# FeatherLargePrototype.net
KiCad netlist of a schematic drawn in EAGLE
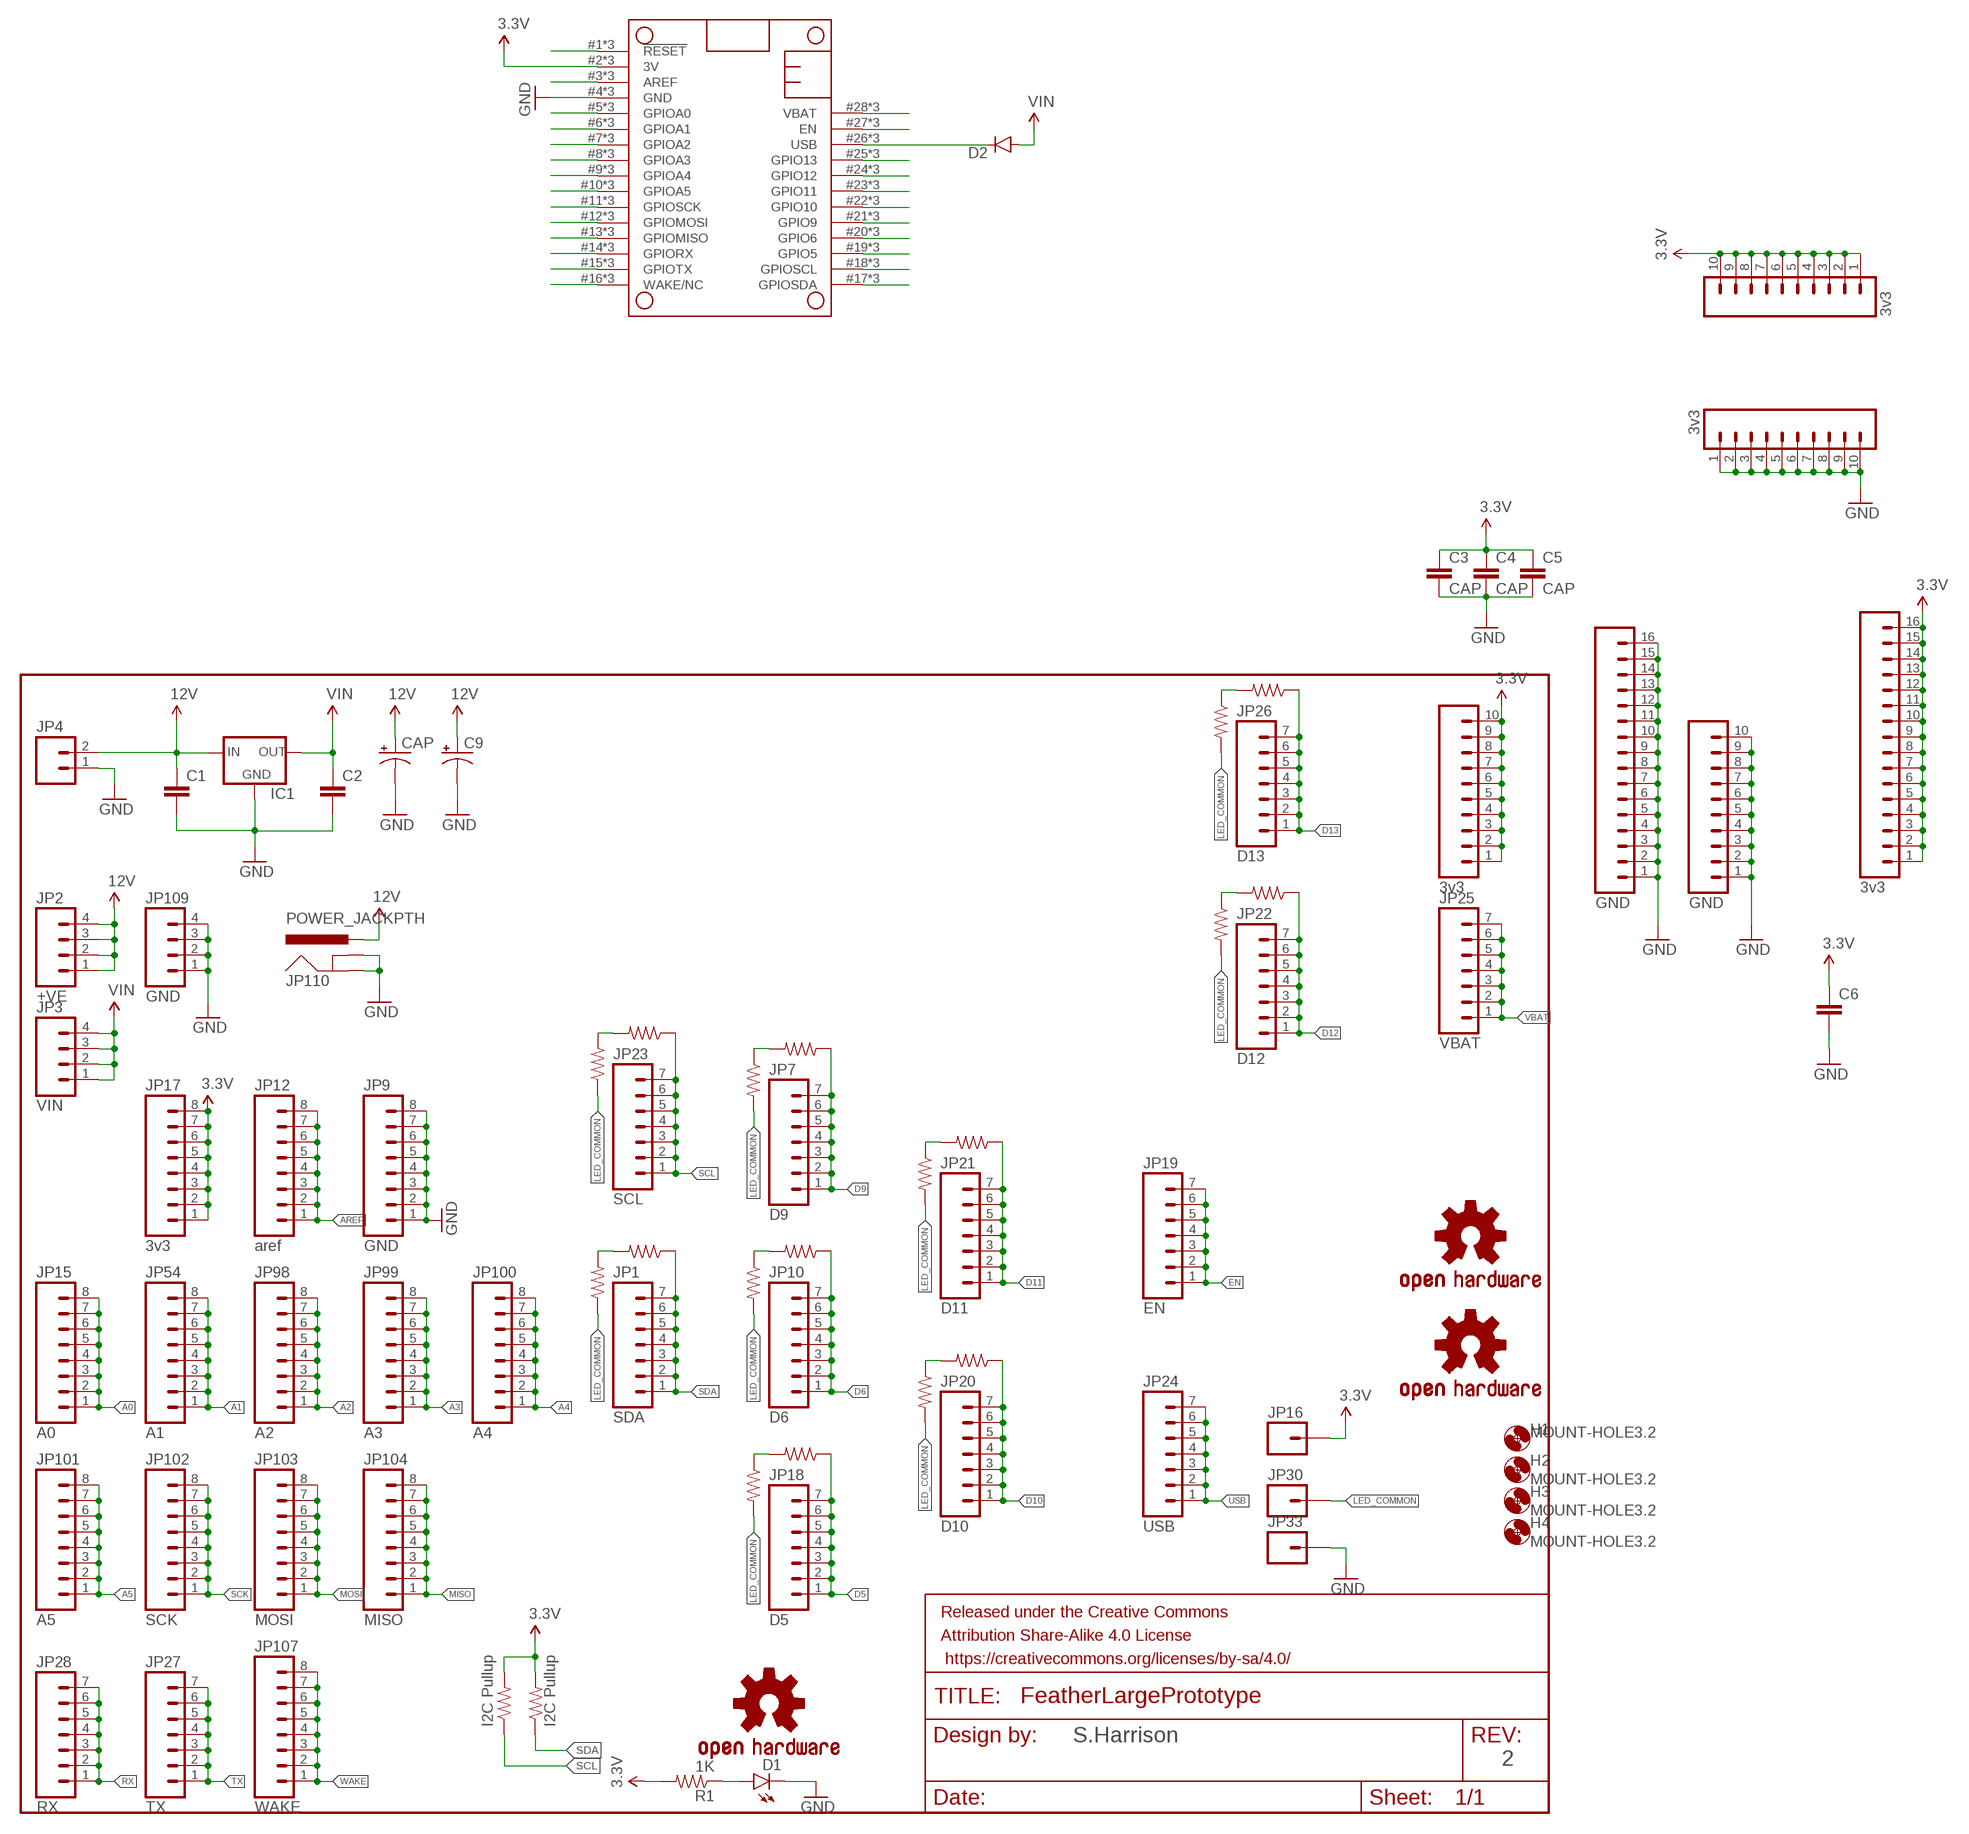
[diagram p0: schematic, sheet 1, part 1 of 2]
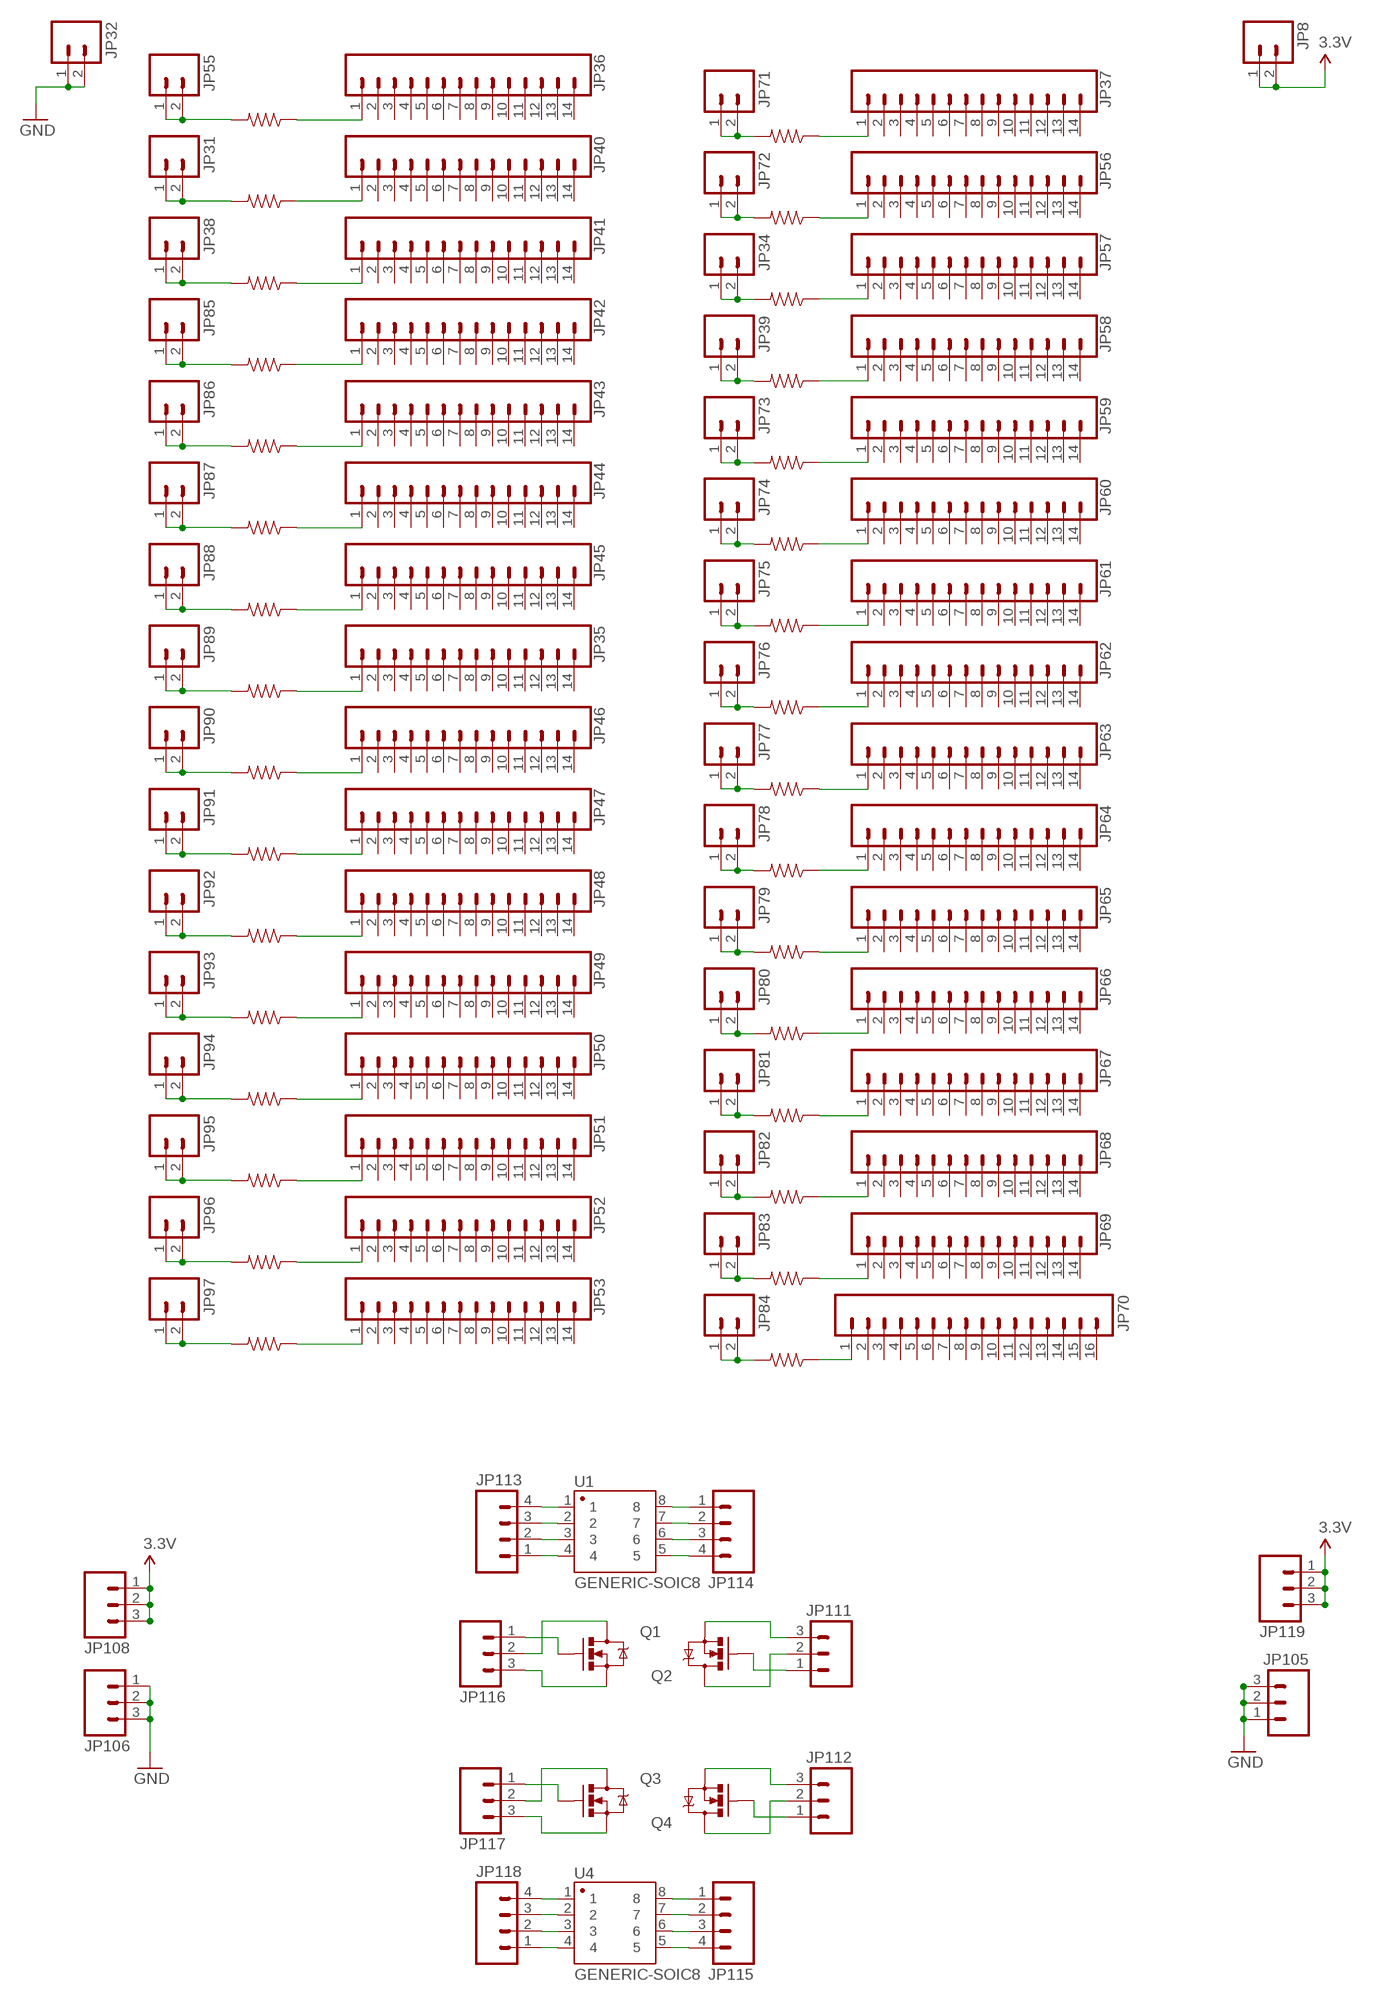
[diagram p1: schematic, sheet 1, part 2 of 2]

(export (version "E")
  (design (tool "Eeschema 10.0.6"))
  (components
    (comp (ref "C1")
      (value "CAP1206")
      (footprint "eagle-import:1206")
      (libsource (lib "eagle-import") (part "CAP1206"))
    )
    (comp (ref "C2")
      (value "CAP1206")
      (footprint "eagle-import:1206")
      (libsource (lib "eagle-import") (part "CAP1206"))
    )
    (comp (ref "C3")
      (value "CAP")
      (footprint "eagle-import:1206")
      (libsource (lib "eagle-import") (part "CAP1206"))
    )
    (comp (ref "C4")
      (value "CAP")
      (footprint "eagle-import:1206")
      (libsource (lib "eagle-import") (part "CAP1206"))
    )
    (comp (ref "C5")
      (value "CAP")
      (footprint "eagle-import:1206")
      (libsource (lib "eagle-import") (part "CAP1206"))
    )
    (comp (ref "C6")
      (value "CAP1206")
      (footprint "eagle-import:1206")
      (libsource (lib "eagle-import") (part "CAP1206"))
    )
    (comp (ref "C9")
      (value "CAP_POL7343")
      (footprint "eagle-import:EIA7343")
      (libsource (lib "eagle-import") (part "CAP_POL7343"))
    )
    (comp (ref "CAP")
      (value "CAP_POLPTH1")
      (footprint "eagle-import:CPOL-RADIAL-100UF-25V")
      (libsource (lib "eagle-import") (part "CAP_POLPTH1"))
    )
    (comp (ref "D1")
      (value "LED1206-BOTTOM")
      (footprint "eagle-import:LED-1206-BOTTOM")
      (libsource (lib "eagle-import") (part "LED1206-BOTTOM"))
    )
    (comp (ref "D2")
      (value "DIODESMA-ALT")
      (footprint "eagle-import:SMA-DIODE_ALT")
      (libsource (lib "eagle-import") (part "DIODESMA-ALT"))
    )
    (comp (ref "FRAME1")
      (value "FRAME-LETTER")
      (footprint "eagle-import:CREATIVE_COMMONS")
      (libsource (lib "eagle-import") (part "FRAME-LETTER"))
    )
    (comp (ref "H1")
      (value "MOUNT-HOLE3.2")
      (footprint "eagle-import:3,2")
      (libsource (lib "eagle-import") (part "MOUNT-HOLE3.2"))
    )
    (comp (ref "H2")
      (value "MOUNT-HOLE3.2")
      (footprint "eagle-import:3,2")
      (libsource (lib "eagle-import") (part "MOUNT-HOLE3.2"))
    )
    (comp (ref "H3")
      (value "MOUNT-HOLE3.2")
      (footprint "eagle-import:3,2")
      (libsource (lib "eagle-import") (part "MOUNT-HOLE3.2"))
    )
    (comp (ref "H4")
      (value "MOUNT-HOLE3.2")
      (footprint "eagle-import:3,2")
      (libsource (lib "eagle-import") (part "MOUNT-HOLE3.2"))
    )
    (comp (ref "IC1")
      (value "78XXS")
      (footprint "eagle-import:78XXS")
      (libsource (lib "eagle-import") (part "78XXS"))
    )
    (comp (ref "JP1")
      (value "SDA")
      (footprint "eagle-import:1X07")
      (libsource (lib "eagle-import") (part "M07"))
    )
    (comp (ref "JP2")
      (value "+VE")
      (footprint "eagle-import:1X04")
      (libsource (lib "eagle-import") (part "M04PTH"))
    )
    (comp (ref "JP3")
      (value "VIN")
      (footprint "eagle-import:1X04")
      (libsource (lib "eagle-import") (part "M04PTH"))
    )
    (comp (ref "JP4")
      (value "M025MM")
      (footprint "eagle-import:SCREWTERMINAL-5MM-2")
      (libsource (lib "eagle-import") (part "M025MM"))
    )
    (comp (ref "JP5")
      (value "3v3")
      (footprint "eagle-import:1X10")
      (libsource (lib "eagle-import") (part "M10SILK_FEMALE_PTH"))
    )
    (comp (ref "JP6")
      (value "3v3")
      (footprint "eagle-import:1X10")
      (libsource (lib "eagle-import") (part "M10SILK_FEMALE_PTH"))
    )
    (comp (ref "JP7")
      (value "D9")
      (footprint "eagle-import:1X07")
      (libsource (lib "eagle-import") (part "M07"))
    )
    (comp (ref "JP8")
      (value "M02PTH")
      (footprint "eagle-import:1X02")
      (libsource (lib "eagle-import") (part "M02PTH"))
    )
    (comp (ref "JP9")
      (value "GND")
      (footprint "eagle-import:1X08_ROUND")
      (libsource (lib "eagle-import") (part "M08"))
    )
    (comp (ref "JP10")
      (value "D6")
      (footprint "eagle-import:1X07")
      (libsource (lib "eagle-import") (part "M07"))
    )
    (comp (ref "JP11")
      (value "GND")
      (footprint "eagle-import:1X10")
      (libsource (lib "eagle-import") (part "M10SILK_FEMALE_PTH"))
    )
    (comp (ref "JP12")
      (value "aref")
      (footprint "eagle-import:1X08_ROUND")
      (libsource (lib "eagle-import") (part "M08"))
    )
    (comp (ref "JP13")
      (value "3v3")
      (footprint "eagle-import:1X16")
      (libsource (lib "eagle-import") (part "M16PTH"))
    )
    (comp (ref "JP14")
      (value "GND")
      (footprint "eagle-import:1X16")
      (libsource (lib "eagle-import") (part "M16PTH"))
    )
    (comp (ref "JP15")
      (value "A0")
      (footprint "eagle-import:1X08_ROUND")
      (libsource (lib "eagle-import") (part "M08"))
    )
    (comp (ref "JP16")
      (value "M01PTH")
      (footprint "eagle-import:1X01")
      (libsource (lib "eagle-import") (part "M01PTH"))
    )
    (comp (ref "JP17")
      (value "3v3")
      (footprint "eagle-import:1X08_ROUND")
      (libsource (lib "eagle-import") (part "M08"))
    )
    (comp (ref "JP18")
      (value "D5")
      (footprint "eagle-import:1X07")
      (libsource (lib "eagle-import") (part "M07"))
    )
    (comp (ref "JP19")
      (value "EN")
      (footprint "eagle-import:1X07")
      (libsource (lib "eagle-import") (part "M07"))
    )
    (comp (ref "JP20")
      (value "D10")
      (footprint "eagle-import:1X07")
      (libsource (lib "eagle-import") (part "M07"))
    )
    (comp (ref "JP21")
      (value "D11")
      (footprint "eagle-import:1X07")
      (libsource (lib "eagle-import") (part "M07"))
    )
    (comp (ref "JP22")
      (value "D12")
      (footprint "eagle-import:1X07")
      (libsource (lib "eagle-import") (part "M07"))
    )
    (comp (ref "JP23")
      (value "SCL")
      (footprint "eagle-import:1X07")
      (libsource (lib "eagle-import") (part "M07"))
    )
    (comp (ref "JP24")
      (value "USB")
      (footprint "eagle-import:1X07")
      (libsource (lib "eagle-import") (part "M07"))
    )
    (comp (ref "JP25")
      (value "VBAT")
      (footprint "eagle-import:1X07")
      (libsource (lib "eagle-import") (part "M07"))
    )
    (comp (ref "JP26")
      (value "D13")
      (footprint "eagle-import:1X07")
      (libsource (lib "eagle-import") (part "M07"))
    )
    (comp (ref "JP27")
      (value "TX")
      (footprint "eagle-import:1X07")
      (libsource (lib "eagle-import") (part "M07"))
    )
    (comp (ref "JP28")
      (value "RX")
      (footprint "eagle-import:1X07")
      (libsource (lib "eagle-import") (part "M07"))
    )
    (comp (ref "JP29")
      (value "3v3")
      (footprint "eagle-import:1X10")
      (libsource (lib "eagle-import") (part "M10SILK_FEMALE_PTH"))
    )
    (comp (ref "JP30")
      (value "M01PTH")
      (footprint "eagle-import:1X01")
      (libsource (lib "eagle-import") (part "M01PTH"))
    )
    (comp (ref "JP31")
      (value "M02PTH")
      (footprint "eagle-import:1X02")
      (libsource (lib "eagle-import") (part "M02PTH"))
    )
    (comp (ref "JP32")
      (value "M02PTH")
      (footprint "eagle-import:1X02")
      (libsource (lib "eagle-import") (part "M02PTH"))
    )
    (comp (ref "JP33")
      (value "M01PTH")
      (footprint "eagle-import:1X01")
      (libsource (lib "eagle-import") (part "M01PTH"))
    )
    (comp (ref "JP34")
      (value "M02PTH")
      (footprint "eagle-import:1X02")
      (libsource (lib "eagle-import") (part "M02PTH"))
    )
    (comp (ref "JP35")
      (value "CONN_14CONNECTED")
      (footprint "eagle-import:1X14_CONNECTED")
      (libsource (lib "eagle-import") (part "CONN_14CONNECTED"))
    )
    (comp (ref "JP36")
      (value "CONN_14CONNECTED")
      (footprint "eagle-import:1X14_CONNECTED")
      (libsource (lib "eagle-import") (part "CONN_14CONNECTED"))
    )
    (comp (ref "JP37")
      (value "CONN_14CONNECTED")
      (footprint "eagle-import:1X14_CONNECTED")
      (libsource (lib "eagle-import") (part "CONN_14CONNECTED"))
    )
    (comp (ref "JP38")
      (value "M02PTH")
      (footprint "eagle-import:1X02")
      (libsource (lib "eagle-import") (part "M02PTH"))
    )
    (comp (ref "JP39")
      (value "M02PTH")
      (footprint "eagle-import:1X02")
      (libsource (lib "eagle-import") (part "M02PTH"))
    )
    (comp (ref "JP40")
      (value "CONN_14CONNECTED")
      (footprint "eagle-import:1X14_CONNECTED")
      (libsource (lib "eagle-import") (part "CONN_14CONNECTED"))
    )
    (comp (ref "JP41")
      (value "CONN_14CONNECTED")
      (footprint "eagle-import:1X14_CONNECTED")
      (libsource (lib "eagle-import") (part "CONN_14CONNECTED"))
    )
    (comp (ref "JP42")
      (value "CONN_14CONNECTED")
      (footprint "eagle-import:1X14_CONNECTED")
      (libsource (lib "eagle-import") (part "CONN_14CONNECTED"))
    )
    (comp (ref "JP43")
      (value "CONN_14CONNECTED")
      (footprint "eagle-import:1X14_CONNECTED")
      (libsource (lib "eagle-import") (part "CONN_14CONNECTED"))
    )
    (comp (ref "JP44")
      (value "CONN_14CONNECTED")
      (footprint "eagle-import:1X14_CONNECTED")
      (libsource (lib "eagle-import") (part "CONN_14CONNECTED"))
    )
    (comp (ref "JP45")
      (value "CONN_14CONNECTED")
      (footprint "eagle-import:1X14_CONNECTED")
      (libsource (lib "eagle-import") (part "CONN_14CONNECTED"))
    )
    (comp (ref "JP46")
      (value "CONN_14CONNECTED")
      (footprint "eagle-import:1X14_CONNECTED")
      (libsource (lib "eagle-import") (part "CONN_14CONNECTED"))
    )
    (comp (ref "JP47")
      (value "CONN_14CONNECTED")
      (footprint "eagle-import:1X14_CONNECTED")
      (libsource (lib "eagle-import") (part "CONN_14CONNECTED"))
    )
    (comp (ref "JP48")
      (value "CONN_14CONNECTED")
      (footprint "eagle-import:1X14_CONNECTED")
      (libsource (lib "eagle-import") (part "CONN_14CONNECTED"))
    )
    (comp (ref "JP49")
      (value "CONN_14CONNECTED")
      (footprint "eagle-import:1X14_CONNECTED")
      (libsource (lib "eagle-import") (part "CONN_14CONNECTED"))
    )
    (comp (ref "JP50")
      (value "CONN_14CONNECTED")
      (footprint "eagle-import:1X14_CONNECTED")
      (libsource (lib "eagle-import") (part "CONN_14CONNECTED"))
    )
    (comp (ref "JP51")
      (value "CONN_14CONNECTED")
      (footprint "eagle-import:1X14_CONNECTED")
      (libsource (lib "eagle-import") (part "CONN_14CONNECTED"))
    )
    (comp (ref "JP52")
      (value "CONN_14CONNECTED")
      (footprint "eagle-import:1X14_CONNECTED")
      (libsource (lib "eagle-import") (part "CONN_14CONNECTED"))
    )
    (comp (ref "JP53")
      (value "CONN_14NO_SILK")
      (footprint "eagle-import:1X14_NO_SILK")
      (libsource (lib "eagle-import") (part "CONN_14NO_SILK"))
    )
    (comp (ref "JP54")
      (value "A1")
      (footprint "eagle-import:1X08_ROUND")
      (libsource (lib "eagle-import") (part "M08"))
    )
    (comp (ref "JP55")
      (value "M02PTH")
      (footprint "eagle-import:1X02")
      (libsource (lib "eagle-import") (part "M02PTH"))
    )
    (comp (ref "JP56")
      (value "CONN_14CONNECTED")
      (footprint "eagle-import:1X14_CONNECTED")
      (libsource (lib "eagle-import") (part "CONN_14CONNECTED"))
    )
    (comp (ref "JP57")
      (value "CONN_14CONNECTED")
      (footprint "eagle-import:1X14_CONNECTED")
      (libsource (lib "eagle-import") (part "CONN_14CONNECTED"))
    )
    (comp (ref "JP58")
      (value "CONN_14CONNECTED")
      (footprint "eagle-import:1X14_CONNECTED")
      (libsource (lib "eagle-import") (part "CONN_14CONNECTED"))
    )
    (comp (ref "JP59")
      (value "CONN_14CONNECTED")
      (footprint "eagle-import:1X14_CONNECTED")
      (libsource (lib "eagle-import") (part "CONN_14CONNECTED"))
    )
    (comp (ref "JP60")
      (value "CONN_14CONNECTED")
      (footprint "eagle-import:1X14_CONNECTED")
      (libsource (lib "eagle-import") (part "CONN_14CONNECTED"))
    )
    (comp (ref "JP61")
      (value "CONN_14CONNECTED")
      (footprint "eagle-import:1X14_CONNECTED")
      (libsource (lib "eagle-import") (part "CONN_14CONNECTED"))
    )
    (comp (ref "JP62")
      (value "CONN_14CONNECTED")
      (footprint "eagle-import:1X14_CONNECTED")
      (libsource (lib "eagle-import") (part "CONN_14CONNECTED"))
    )
    (comp (ref "JP63")
      (value "CONN_14CONNECTED")
      (footprint "eagle-import:1X14_CONNECTED")
      (libsource (lib "eagle-import") (part "CONN_14CONNECTED"))
    )
    (comp (ref "JP64")
      (value "CONN_14CONNECTED")
      (footprint "eagle-import:1X14_CONNECTED")
      (libsource (lib "eagle-import") (part "CONN_14CONNECTED"))
    )
    (comp (ref "JP65")
      (value "CONN_14CONNECTED")
      (footprint "eagle-import:1X14_CONNECTED")
      (libsource (lib "eagle-import") (part "CONN_14CONNECTED"))
    )
    (comp (ref "JP66")
      (value "CONN_14CONNECTED")
      (footprint "eagle-import:1X14_CONNECTED")
      (libsource (lib "eagle-import") (part "CONN_14CONNECTED"))
    )
    (comp (ref "JP67")
      (value "CONN_14CONNECTED")
      (footprint "eagle-import:1X14_CONNECTED")
      (libsource (lib "eagle-import") (part "CONN_14CONNECTED"))
    )
    (comp (ref "JP68")
      (value "CONN_14CONNECTED")
      (footprint "eagle-import:1X14_CONNECTED")
      (libsource (lib "eagle-import") (part "CONN_14CONNECTED"))
    )
    (comp (ref "JP69")
      (value "CONN_14CONNECTED")
      (footprint "eagle-import:1X14_CONNECTED")
      (libsource (lib "eagle-import") (part "CONN_14CONNECTED"))
    )
    (comp (ref "JP70")
      (value "M161X16_NO_SILK")
      (footprint "eagle-import:1X16_NO_SILK")
      (libsource (lib "eagle-import") (part "M161X16_NO_SILK"))
    )
    (comp (ref "JP71")
      (value "M02PTH")
      (footprint "eagle-import:1X02")
      (libsource (lib "eagle-import") (part "M02PTH"))
    )
    (comp (ref "JP72")
      (value "M02PTH")
      (footprint "eagle-import:1X02")
      (libsource (lib "eagle-import") (part "M02PTH"))
    )
    (comp (ref "JP73")
      (value "M02PTH")
      (footprint "eagle-import:1X02")
      (libsource (lib "eagle-import") (part "M02PTH"))
    )
    (comp (ref "JP74")
      (value "M02PTH")
      (footprint "eagle-import:1X02")
      (libsource (lib "eagle-import") (part "M02PTH"))
    )
    (comp (ref "JP75")
      (value "M02PTH")
      (footprint "eagle-import:1X02")
      (libsource (lib "eagle-import") (part "M02PTH"))
    )
    (comp (ref "JP76")
      (value "M02PTH")
      (footprint "eagle-import:1X02")
      (libsource (lib "eagle-import") (part "M02PTH"))
    )
    (comp (ref "JP77")
      (value "M02PTH")
      (footprint "eagle-import:1X02")
      (libsource (lib "eagle-import") (part "M02PTH"))
    )
    (comp (ref "JP78")
      (value "M02PTH")
      (footprint "eagle-import:1X02")
      (libsource (lib "eagle-import") (part "M02PTH"))
    )
    (comp (ref "JP79")
      (value "M02PTH")
      (footprint "eagle-import:1X02")
      (libsource (lib "eagle-import") (part "M02PTH"))
    )
    (comp (ref "JP80")
      (value "M02PTH")
      (footprint "eagle-import:1X02")
      (libsource (lib "eagle-import") (part "M02PTH"))
    )
    (comp (ref "JP81")
      (value "M02PTH")
      (footprint "eagle-import:1X02")
      (libsource (lib "eagle-import") (part "M02PTH"))
    )
    (comp (ref "JP82")
      (value "M02PTH")
      (footprint "eagle-import:1X02")
      (libsource (lib "eagle-import") (part "M02PTH"))
    )
    (comp (ref "JP83")
      (value "M02PTH")
      (footprint "eagle-import:1X02")
      (libsource (lib "eagle-import") (part "M02PTH"))
    )
    (comp (ref "JP84")
      (value "M02PTH")
      (footprint "eagle-import:1X02")
      (libsource (lib "eagle-import") (part "M02PTH"))
    )
    (comp (ref "JP85")
      (value "M02PTH")
      (footprint "eagle-import:1X02")
      (libsource (lib "eagle-import") (part "M02PTH"))
    )
    (comp (ref "JP86")
      (value "M02PTH")
      (footprint "eagle-import:1X02")
      (libsource (lib "eagle-import") (part "M02PTH"))
    )
    (comp (ref "JP87")
      (value "M02PTH")
      (footprint "eagle-import:1X02")
      (libsource (lib "eagle-import") (part "M02PTH"))
    )
    (comp (ref "JP88")
      (value "M02PTH")
      (footprint "eagle-import:1X02")
      (libsource (lib "eagle-import") (part "M02PTH"))
    )
    (comp (ref "JP89")
      (value "M02PTH")
      (footprint "eagle-import:1X02")
      (libsource (lib "eagle-import") (part "M02PTH"))
    )
    (comp (ref "JP90")
      (value "M02PTH")
      (footprint "eagle-import:1X02")
      (libsource (lib "eagle-import") (part "M02PTH"))
    )
    (comp (ref "JP91")
      (value "M02PTH")
      (footprint "eagle-import:1X02")
      (libsource (lib "eagle-import") (part "M02PTH"))
    )
    (comp (ref "JP92")
      (value "M02PTH")
      (footprint "eagle-import:1X02")
      (libsource (lib "eagle-import") (part "M02PTH"))
    )
    (comp (ref "JP93")
      (value "M02PTH")
      (footprint "eagle-import:1X02")
      (libsource (lib "eagle-import") (part "M02PTH"))
    )
    (comp (ref "JP94")
      (value "M02PTH")
      (footprint "eagle-import:1X02")
      (libsource (lib "eagle-import") (part "M02PTH"))
    )
    (comp (ref "JP95")
      (value "M02PTH")
      (footprint "eagle-import:1X02")
      (libsource (lib "eagle-import") (part "M02PTH"))
    )
    (comp (ref "JP96")
      (value "M02PTH")
      (footprint "eagle-import:1X02")
      (libsource (lib "eagle-import") (part "M02PTH"))
    )
    (comp (ref "JP97")
      (value "M02PTH")
      (footprint "eagle-import:1X02")
      (libsource (lib "eagle-import") (part "M02PTH"))
    )
    (comp (ref "JP98")
      (value "A2")
      (footprint "eagle-import:1X08_ROUND")
      (libsource (lib "eagle-import") (part "M08"))
    )
    (comp (ref "JP99")
      (value "A3")
      (footprint "eagle-import:1X08_ROUND")
      (libsource (lib "eagle-import") (part "M08"))
    )
    (comp (ref "JP100")
      (value "A4")
      (footprint "eagle-import:1X08_ROUND")
      (libsource (lib "eagle-import") (part "M08"))
    )
    (comp (ref "JP101")
      (value "A5")
      (footprint "eagle-import:1X08_ROUND")
      (libsource (lib "eagle-import") (part "M08"))
    )
    (comp (ref "JP102")
      (value "SCK")
      (footprint "eagle-import:1X08_ROUND")
      (libsource (lib "eagle-import") (part "M08"))
    )
    (comp (ref "JP103")
      (value "MOSI")
      (footprint "eagle-import:1X08_ROUND")
      (libsource (lib "eagle-import") (part "M08"))
    )
    (comp (ref "JP104")
      (value "MISO")
      (footprint "eagle-import:1X08_ROUND")
      (libsource (lib "eagle-import") (part "M08"))
    )
    (comp (ref "JP105")
      (value "M03PTH")
      (footprint "eagle-import:1X03")
      (libsource (lib "eagle-import") (part "M03PTH"))
    )
    (comp (ref "JP106")
      (value "M03PTH")
      (footprint "eagle-import:1X03")
      (libsource (lib "eagle-import") (part "M03PTH"))
    )
    (comp (ref "JP107")
      (value "WAKE")
      (footprint "eagle-import:1X08_ROUND")
      (libsource (lib "eagle-import") (part "M08"))
    )
    (comp (ref "JP108")
      (value "M03PTH")
      (footprint "eagle-import:1X03")
      (libsource (lib "eagle-import") (part "M03PTH"))
    )
    (comp (ref "JP109")
      (value "GND")
      (footprint "eagle-import:1X04")
      (libsource (lib "eagle-import") (part "M04PTH"))
    )
    (comp (ref "JP110")
      (value "POWER_JACKPTH")
      (footprint "eagle-import:POWER_JACK_PTH")
      (libsource (lib "eagle-import") (part "POWER_JACKPTH"))
    )
    (comp (ref "JP111")
      (value "M03PTH")
      (footprint "eagle-import:1X03")
      (libsource (lib "eagle-import") (part "M03PTH"))
    )
    (comp (ref "JP112")
      (value "M03PTH")
      (footprint "eagle-import:1X03")
      (libsource (lib "eagle-import") (part "M03PTH"))
    )
    (comp (ref "JP113")
      (value "M04NO_SILK_ALL_ROUND")
      (footprint "eagle-import:1X04_NO_SILK_ALL_ROUND")
      (libsource (lib "eagle-import") (part "M04NO_SILK_ALL_ROUND"))
    )
    (comp (ref "JP114")
      (value "M04NO_SILK_ALL_ROUND")
      (footprint "eagle-import:1X04_NO_SILK_ALL_ROUND")
      (libsource (lib "eagle-import") (part "M04NO_SILK_ALL_ROUND"))
    )
    (comp (ref "JP115")
      (value "M04NO_SILK_ALL_ROUND")
      (footprint "eagle-import:1X04_NO_SILK_ALL_ROUND")
      (libsource (lib "eagle-import") (part "M04NO_SILK_ALL_ROUND"))
    )
    (comp (ref "JP116")
      (value "M03PTH")
      (footprint "eagle-import:1X03")
      (libsource (lib "eagle-import") (part "M03PTH"))
    )
    (comp (ref "JP117")
      (value "M03PTH")
      (footprint "eagle-import:1X03")
      (libsource (lib "eagle-import") (part "M03PTH"))
    )
    (comp (ref "JP118")
      (value "M04NO_SILK_ALL_ROUND")
      (footprint "eagle-import:1X04_NO_SILK_ALL_ROUND")
      (libsource (lib "eagle-import") (part "M04NO_SILK_ALL_ROUND"))
    )
    (comp (ref "JP119")
      (value "M03PTH")
      (footprint "eagle-import:1X03")
      (libsource (lib "eagle-import") (part "M03PTH"))
    )
    (comp (ref "LOGO1")
      (value "OSHW-LOGOL")
      (footprint "eagle-import:OSHW-LOGO-L")
      (libsource (lib "eagle-import") (part "OSHW-LOGOL"))
    )
    (comp (ref "LOGO2")
      (value "OSHW-LOGOL")
      (footprint "eagle-import:OSHW-LOGO-L")
      (libsource (lib "eagle-import") (part "OSHW-LOGOL"))
    )
    (comp (ref "LOGO3")
      (value "OSHW-LOGOM")
      (footprint "eagle-import:OSHW-LOGO-M")
      (libsource (lib "eagle-import") (part "OSHW-LOGOM"))
    )
    (comp (ref "MS2")
      (value "FEATHERWINGFEATHEWING_BREAKOUT")
      (footprint "eagle-import:FEATHERWING_BREAKOUT")
      (libsource (lib "eagle-import") (part "FEATHERWINGFEATHEWING_BREAKOUT"))
    )
    (comp (ref "Q1")
      (value "MOSFET-NCHANNELBSS123LT1G")
      (footprint "eagle-import:SOT23-3")
      (libsource (lib "eagle-import") (part "MOSFET-NCHANNELBSS123LT1G"))
    )
    (comp (ref "Q2")
      (value "MOSFET-NCHANNELBSS123LT1G")
      (footprint "eagle-import:SOT23-3")
      (libsource (lib "eagle-import") (part "MOSFET-NCHANNELBSS123LT1G"))
    )
    (comp (ref "Q3")
      (value "MOSFET-NCHANNELBSS123LT1G")
      (footprint "eagle-import:SOT23-3")
      (libsource (lib "eagle-import") (part "MOSFET-NCHANNELBSS123LT1G"))
    )
    (comp (ref "Q4")
      (value "MOSFET-NCHANNELBSS123LT1G")
      (footprint "eagle-import:SOT23-3")
      (libsource (lib "eagle-import") (part "MOSFET-NCHANNELBSS123LT1G"))
    )
    (comp (ref "R1")
      (value "1K")
      (footprint "eagle-import:1206")
      (libsource (lib "eagle-import") (part "RESISTOR1206"))
    )
    (comp (ref "R10")
      (value "RESISTOR1206")
      (footprint "eagle-import:1206")
      (libsource (lib "eagle-import") (part "RESISTOR1206"))
    )
    (comp (ref "R11")
      (value "RESISTOR1206")
      (footprint "eagle-import:1206")
      (libsource (lib "eagle-import") (part "RESISTOR1206"))
    )
    (comp (ref "R12")
      (value "RESISTOR1206")
      (footprint "eagle-import:1206")
      (libsource (lib "eagle-import") (part "RESISTOR1206"))
    )
    (comp (ref "R13")
      (value "RESISTOR1206")
      (footprint "eagle-import:1206")
      (libsource (lib "eagle-import") (part "RESISTOR1206"))
    )
    (comp (ref "R14")
      (value "RESISTOR1206")
      (footprint "eagle-import:1206")
      (libsource (lib "eagle-import") (part "RESISTOR1206"))
    )
    (comp (ref "R15")
      (value "RESISTOR1206")
      (footprint "eagle-import:1206")
      (libsource (lib "eagle-import") (part "RESISTOR1206"))
    )
    (comp (ref "R16")
      (value "RESISTOR1206")
      (footprint "eagle-import:1206")
      (libsource (lib "eagle-import") (part "RESISTOR1206"))
    )
    (comp (ref "R17")
      (value "RESISTOR1206")
      (footprint "eagle-import:1206")
      (libsource (lib "eagle-import") (part "RESISTOR1206"))
    )
    (comp (ref "R18")
      (value "RESISTOR1206")
      (footprint "eagle-import:1206")
      (libsource (lib "eagle-import") (part "RESISTOR1206"))
    )
    (comp (ref "R19")
      (value "RESISTOR1206")
      (footprint "eagle-import:1206")
      (libsource (lib "eagle-import") (part "RESISTOR1206"))
    )
    (comp (ref "R20")
      (value "RESISTOR1206")
      (footprint "eagle-import:1206")
      (libsource (lib "eagle-import") (part "RESISTOR1206"))
    )
    (comp (ref "R21")
      (value "RESISTOR1206")
      (footprint "eagle-import:1206")
      (libsource (lib "eagle-import") (part "RESISTOR1206"))
    )
    (comp (ref "R22")
      (value "RESISTOR1206")
      (footprint "eagle-import:1206")
      (libsource (lib "eagle-import") (part "RESISTOR1206"))
    )
    (comp (ref "R23")
      (value "RESISTOR1206")
      (footprint "eagle-import:1206")
      (libsource (lib "eagle-import") (part "RESISTOR1206"))
    )
    (comp (ref "R24")
      (value "RESISTOR1206")
      (footprint "eagle-import:1206")
      (libsource (lib "eagle-import") (part "RESISTOR1206"))
    )
    (comp (ref "R25")
      (value "RESISTOR1206")
      (footprint "eagle-import:1206")
      (libsource (lib "eagle-import") (part "RESISTOR1206"))
    )
    (comp (ref "R26")
      (value "RESISTOR1206")
      (footprint "eagle-import:1206")
      (libsource (lib "eagle-import") (part "RESISTOR1206"))
    )
    (comp (ref "R27")
      (value "RESISTOR1206")
      (footprint "eagle-import:1206")
      (libsource (lib "eagle-import") (part "RESISTOR1206"))
    )
    (comp (ref "R30")
      (value "RESISTOR1206")
      (footprint "eagle-import:1206")
      (libsource (lib "eagle-import") (part "RESISTOR1206"))
    )
    (comp (ref "R31")
      (value "RESISTOR1206")
      (footprint "eagle-import:1206")
      (libsource (lib "eagle-import") (part "RESISTOR1206"))
    )
    (comp (ref "R32")
      (value "RESISTOR1206")
      (footprint "eagle-import:1206")
      (libsource (lib "eagle-import") (part "RESISTOR1206"))
    )
    (comp (ref "R33")
      (value "RESISTOR1206")
      (footprint "eagle-import:1206")
      (libsource (lib "eagle-import") (part "RESISTOR1206"))
    )
    (comp (ref "R34")
      (value "RESISTOR1206")
      (footprint "eagle-import:1206")
      (libsource (lib "eagle-import") (part "RESISTOR1206"))
    )
    (comp (ref "R35")
      (value "RESISTOR1206")
      (footprint "eagle-import:1206")
      (libsource (lib "eagle-import") (part "RESISTOR1206"))
    )
    (comp (ref "R36")
      (value "RESISTOR1206")
      (footprint "eagle-import:1206")
      (libsource (lib "eagle-import") (part "RESISTOR1206"))
    )
    (comp (ref "R37")
      (value "RESISTOR1206")
      (footprint "eagle-import:1206")
      (libsource (lib "eagle-import") (part "RESISTOR1206"))
    )
    (comp (ref "R38")
      (value "RESISTOR1206")
      (footprint "eagle-import:1206")
      (libsource (lib "eagle-import") (part "RESISTOR1206"))
    )
    (comp (ref "R39")
      (value "RESISTOR1206")
      (footprint "eagle-import:1206")
      (libsource (lib "eagle-import") (part "RESISTOR1206"))
    )
    (comp (ref "R40")
      (value "RESISTOR1206")
      (footprint "eagle-import:1206")
      (libsource (lib "eagle-import") (part "RESISTOR1206"))
    )
    (comp (ref "R41")
      (value "RESISTOR1206")
      (footprint "eagle-import:1206")
      (libsource (lib "eagle-import") (part "RESISTOR1206"))
    )
    (comp (ref "R42")
      (value "RESISTOR1206")
      (footprint "eagle-import:1206")
      (libsource (lib "eagle-import") (part "RESISTOR1206"))
    )
    (comp (ref "R43")
      (value "RESISTOR1206")
      (footprint "eagle-import:1206")
      (libsource (lib "eagle-import") (part "RESISTOR1206"))
    )
    (comp (ref "R44")
      (value "RESISTOR1206")
      (footprint "eagle-import:1206")
      (libsource (lib "eagle-import") (part "RESISTOR1206"))
    )
    (comp (ref "R45")
      (value "RESISTOR1206")
      (footprint "eagle-import:1206")
      (libsource (lib "eagle-import") (part "RESISTOR1206"))
    )
    (comp (ref "R46")
      (value "RESISTOR1206")
      (footprint "eagle-import:1206")
      (libsource (lib "eagle-import") (part "RESISTOR1206"))
    )
    (comp (ref "R47")
      (value "RESISTOR1206")
      (footprint "eagle-import:1206")
      (libsource (lib "eagle-import") (part "RESISTOR1206"))
    )
    (comp (ref "R48")
      (value "RESISTOR1206")
      (footprint "eagle-import:1206")
      (libsource (lib "eagle-import") (part "RESISTOR1206"))
    )
    (comp (ref "R49")
      (value "RESISTOR1206")
      (footprint "eagle-import:1206")
      (libsource (lib "eagle-import") (part "RESISTOR1206"))
    )
    (comp (ref "R50")
      (value "RESISTOR1206")
      (footprint "eagle-import:1206")
      (libsource (lib "eagle-import") (part "RESISTOR1206"))
    )
    (comp (ref "R51")
      (value "RESISTOR1206")
      (footprint "eagle-import:1206")
      (libsource (lib "eagle-import") (part "RESISTOR1206"))
    )
    (comp (ref "R52")
      (value "RESISTOR1206")
      (footprint "eagle-import:1206")
      (libsource (lib "eagle-import") (part "RESISTOR1206"))
    )
    (comp (ref "R53")
      (value "RESISTOR1206")
      (footprint "eagle-import:1206")
      (libsource (lib "eagle-import") (part "RESISTOR1206"))
    )
    (comp (ref "R54")
      (value "RESISTOR1206")
      (footprint "eagle-import:1206")
      (libsource (lib "eagle-import") (part "RESISTOR1206"))
    )
    (comp (ref "R55")
      (value "RESISTOR1206")
      (footprint "eagle-import:1206")
      (libsource (lib "eagle-import") (part "RESISTOR1206"))
    )
    (comp (ref "R56")
      (value "RESISTOR1206")
      (footprint "eagle-import:1206")
      (libsource (lib "eagle-import") (part "RESISTOR1206"))
    )
    (comp (ref "R57")
      (value "RESISTOR1206")
      (footprint "eagle-import:1206")
      (libsource (lib "eagle-import") (part "RESISTOR1206"))
    )
    (comp (ref "R58")
      (value "RESISTOR1206")
      (footprint "eagle-import:1206")
      (libsource (lib "eagle-import") (part "RESISTOR1206"))
    )
    (comp (ref "R59")
      (value "RESISTOR1206")
      (footprint "eagle-import:1206")
      (libsource (lib "eagle-import") (part "RESISTOR1206"))
    )
    (comp (ref "R60")
      (value "RESISTOR1206")
      (footprint "eagle-import:1206")
      (libsource (lib "eagle-import") (part "RESISTOR1206"))
    )
    (comp (ref "R61")
      (value "RESISTOR1206")
      (footprint "eagle-import:1206")
      (libsource (lib "eagle-import") (part "RESISTOR1206"))
    )
    (comp (ref "R62")
      (value "I2C Pullup")
      (footprint "eagle-import:1206")
      (libsource (lib "eagle-import") (part "RESISTOR1206"))
    )
    (comp (ref "R63")
      (value "I2C Pullup")
      (footprint "eagle-import:1206")
      (libsource (lib "eagle-import") (part "RESISTOR1206"))
    )
    (comp (ref "U1")
      (value "GENERIC-SOIC8")
      (footprint "eagle-import:SO08-UNIVERSAL")
      (libsource (lib "eagle-import") (part "GENERIC-SOIC8"))
    )
    (comp (ref "U4")
      (value "GENERIC-SOIC8")
      (footprint "eagle-import:SO08-UNIVERSAL")
      (libsource (lib "eagle-import") (part "GENERIC-SOIC8"))
    )
  )
  (nets
    (net (code "1") (name "3.3V") (class "Default")
      (node (ref "C3") (pin "1") (pinfunction "1_1") (pintype "passive"))
      (node (ref "C4") (pin "1") (pinfunction "1_1") (pintype "passive"))
      (node (ref "C5") (pin "1") (pinfunction "1_1") (pintype "passive"))
      (node (ref "C6") (pin "1") (pinfunction "1_1") (pintype "passive"))
      (node (ref "JP108") (pin "1") (pinfunction "1_1") (pintype "passive"))
      (node (ref "JP108") (pin "2") (pinfunction "2_2") (pintype "passive"))
      (node (ref "JP108") (pin "3") (pinfunction "3_3") (pintype "passive"))
      (node (ref "JP119") (pin "1") (pinfunction "1_1") (pintype "passive"))
      (node (ref "JP119") (pin "2") (pinfunction "2_2") (pintype "passive"))
      (node (ref "JP119") (pin "3") (pinfunction "3_3") (pintype "passive"))
      (node (ref "JP13") (pin "1") (pinfunction "1_1") (pintype "passive"))
      (node (ref "JP13") (pin "10") (pinfunction "10_10") (pintype "passive"))
      (node (ref "JP13") (pin "11") (pinfunction "11_11") (pintype "passive"))
      (node (ref "JP13") (pin "12") (pinfunction "12_12") (pintype "passive"))
      (node (ref "JP13") (pin "13") (pinfunction "13_13") (pintype "passive"))
      (node (ref "JP13") (pin "14") (pinfunction "14_14") (pintype "passive"))
      (node (ref "JP13") (pin "15") (pinfunction "15_15") (pintype "passive"))
      (node (ref "JP13") (pin "16") (pinfunction "16_16") (pintype "passive"))
      (node (ref "JP13") (pin "2") (pinfunction "2_2") (pintype "passive"))
      (node (ref "JP13") (pin "3") (pinfunction "3_3") (pintype "passive"))
      (node (ref "JP13") (pin "4") (pinfunction "4_4") (pintype "passive"))
      (node (ref "JP13") (pin "5") (pinfunction "5_5") (pintype "passive"))
      (node (ref "JP13") (pin "6") (pinfunction "6_6") (pintype "passive"))
      (node (ref "JP13") (pin "7") (pinfunction "7_7") (pintype "passive"))
      (node (ref "JP13") (pin "8") (pinfunction "8_8") (pintype "passive"))
      (node (ref "JP13") (pin "9") (pinfunction "9_9") (pintype "passive"))
      (node (ref "JP16") (pin "1") (pinfunction "1_1") (pintype "passive"))
      (node (ref "JP17") (pin "1") (pinfunction "1_1") (pintype "passive"))
      (node (ref "JP17") (pin "2") (pinfunction "2_2") (pintype "passive"))
      (node (ref "JP17") (pin "3") (pinfunction "3_3") (pintype "passive"))
      (node (ref "JP17") (pin "4") (pinfunction "4_4") (pintype "passive"))
      (node (ref "JP17") (pin "5") (pinfunction "5_5") (pintype "passive"))
      (node (ref "JP17") (pin "6") (pinfunction "6_6") (pintype "passive"))
      (node (ref "JP17") (pin "7") (pinfunction "7_7") (pintype "passive"))
      (node (ref "JP17") (pin "8") (pinfunction "8_8") (pintype "passive"))
      (node (ref "JP5") (pin "1") (pinfunction "1_1") (pintype "passive"))
      (node (ref "JP5") (pin "10") (pinfunction "10_10") (pintype "passive"))
      (node (ref "JP5") (pin "2") (pinfunction "2_2") (pintype "passive"))
      (node (ref "JP5") (pin "3") (pinfunction "3_3") (pintype "passive"))
      (node (ref "JP5") (pin "4") (pinfunction "4_4") (pintype "passive"))
      (node (ref "JP5") (pin "5") (pinfunction "5_5") (pintype "passive"))
      (node (ref "JP5") (pin "6") (pinfunction "6_6") (pintype "passive"))
      (node (ref "JP5") (pin "7") (pinfunction "7_7") (pintype "passive"))
      (node (ref "JP5") (pin "8") (pinfunction "8_8") (pintype "passive"))
      (node (ref "JP5") (pin "9") (pinfunction "9_9") (pintype "passive"))
      (node (ref "JP6") (pin "1") (pinfunction "1_1") (pintype "passive"))
      (node (ref "JP6") (pin "10") (pinfunction "10_10") (pintype "passive"))
      (node (ref "JP6") (pin "2") (pinfunction "2_2") (pintype "passive"))
      (node (ref "JP6") (pin "3") (pinfunction "3_3") (pintype "passive"))
      (node (ref "JP6") (pin "4") (pinfunction "4_4") (pintype "passive"))
      (node (ref "JP6") (pin "5") (pinfunction "5_5") (pintype "passive"))
      (node (ref "JP6") (pin "6") (pinfunction "6_6") (pintype "passive"))
      (node (ref "JP6") (pin "7") (pinfunction "7_7") (pintype "passive"))
      (node (ref "JP6") (pin "8") (pinfunction "8_8") (pintype "passive"))
      (node (ref "JP6") (pin "9") (pinfunction "9_9") (pintype "passive"))
      (node (ref "JP8") (pin "1") (pinfunction "1_1") (pintype "passive"))
      (node (ref "JP8") (pin "2") (pinfunction "2_2") (pintype "passive"))
      (node (ref "MS2") (pin "#2") (pinfunction "3V_#2") (pintype "power_in"))
      (node (ref "MS2") (pin "2") (pinfunction "3V_2") (pintype "power_in"))
      (node (ref "MS2") (pin "@2") (pinfunction "3V_@2") (pintype "power_in"))
      (node (ref "R1") (pin "2") (pinfunction "2_2") (pintype "passive"))
      (node (ref "R62") (pin "2") (pinfunction "2_2") (pintype "passive"))
      (node (ref "R63") (pin "2") (pinfunction "2_2") (pintype "passive"))
    )
    (net (code "2") (name "12V") (class "Default")
      (node (ref "C1") (pin "1") (pinfunction "1_1") (pintype "passive"))
      (node (ref "C9") (pin "A") (pinfunction "+_A") (pintype "passive"))
      (node (ref "CAP") (pin "1") (pinfunction "+_1") (pintype "passive"))
      (node (ref "IC1") (pin "IN") (pinfunction "IN_IN") (pintype "input"))
      (node (ref "JP110") (pin "PWR") (pinfunction "PWR_PWR") (pintype "bidirectional"))
      (node (ref "JP2") (pin "1") (pinfunction "1_1") (pintype "passive"))
      (node (ref "JP2") (pin "2") (pinfunction "2_2") (pintype "passive"))
      (node (ref "JP2") (pin "3") (pinfunction "3_3") (pintype "passive"))
      (node (ref "JP2") (pin "4") (pinfunction "4_4") (pintype "passive"))
      (node (ref "JP4") (pin "2") (pinfunction "2_2") (pintype "passive"))
    )
    (net (code "3") (name "A0") (class "Default")
      (node (ref "JP15") (pin "1") (pinfunction "1_1") (pintype "passive"))
      (node (ref "JP15") (pin "2") (pinfunction "2_2") (pintype "passive"))
      (node (ref "JP15") (pin "3") (pinfunction "3_3") (pintype "passive"))
      (node (ref "JP15") (pin "4") (pinfunction "4_4") (pintype "passive"))
      (node (ref "JP15") (pin "5") (pinfunction "5_5") (pintype "passive"))
      (node (ref "JP15") (pin "6") (pinfunction "6_6") (pintype "passive"))
      (node (ref "JP15") (pin "7") (pinfunction "7_7") (pintype "passive"))
      (node (ref "JP15") (pin "8") (pinfunction "8_8") (pintype "passive"))
      (node (ref "MS2") (pin "#5") (pinfunction "GPIOA0_#5") (pintype "bidirectional"))
      (node (ref "MS2") (pin "5") (pinfunction "GPIOA0_5") (pintype "bidirectional"))
      (node (ref "MS2") (pin "@5") (pinfunction "GPIOA0_@5") (pintype "bidirectional"))
    )
    (net (code "4") (name "A1") (class "Default")
      (node (ref "JP54") (pin "1") (pinfunction "1_1") (pintype "passive"))
      (node (ref "JP54") (pin "2") (pinfunction "2_2") (pintype "passive"))
      (node (ref "JP54") (pin "3") (pinfunction "3_3") (pintype "passive"))
      (node (ref "JP54") (pin "4") (pinfunction "4_4") (pintype "passive"))
      (node (ref "JP54") (pin "5") (pinfunction "5_5") (pintype "passive"))
      (node (ref "JP54") (pin "6") (pinfunction "6_6") (pintype "passive"))
      (node (ref "JP54") (pin "7") (pinfunction "7_7") (pintype "passive"))
      (node (ref "JP54") (pin "8") (pinfunction "8_8") (pintype "passive"))
      (node (ref "MS2") (pin "#6") (pinfunction "GPIOA1_#6") (pintype "bidirectional"))
      (node (ref "MS2") (pin "6") (pinfunction "GPIOA1_6") (pintype "bidirectional"))
      (node (ref "MS2") (pin "@6") (pinfunction "GPIOA1_@6") (pintype "bidirectional"))
    )
    (net (code "5") (name "A2") (class "Default")
      (node (ref "JP98") (pin "1") (pinfunction "1_1") (pintype "passive"))
      (node (ref "JP98") (pin "2") (pinfunction "2_2") (pintype "passive"))
      (node (ref "JP98") (pin "3") (pinfunction "3_3") (pintype "passive"))
      (node (ref "JP98") (pin "4") (pinfunction "4_4") (pintype "passive"))
      (node (ref "JP98") (pin "5") (pinfunction "5_5") (pintype "passive"))
      (node (ref "JP98") (pin "6") (pinfunction "6_6") (pintype "passive"))
      (node (ref "JP98") (pin "7") (pinfunction "7_7") (pintype "passive"))
      (node (ref "JP98") (pin "8") (pinfunction "8_8") (pintype "passive"))
      (node (ref "MS2") (pin "#7") (pinfunction "GPIOA2_#7") (pintype "bidirectional"))
      (node (ref "MS2") (pin "7") (pinfunction "GPIOA2_7") (pintype "bidirectional"))
      (node (ref "MS2") (pin "@7") (pinfunction "GPIOA2_@7") (pintype "bidirectional"))
    )
    (net (code "6") (name "A3") (class "Default")
      (node (ref "JP99") (pin "1") (pinfunction "1_1") (pintype "passive"))
      (node (ref "JP99") (pin "2") (pinfunction "2_2") (pintype "passive"))
      (node (ref "JP99") (pin "3") (pinfunction "3_3") (pintype "passive"))
      (node (ref "JP99") (pin "4") (pinfunction "4_4") (pintype "passive"))
      (node (ref "JP99") (pin "5") (pinfunction "5_5") (pintype "passive"))
      (node (ref "JP99") (pin "6") (pinfunction "6_6") (pintype "passive"))
      (node (ref "JP99") (pin "7") (pinfunction "7_7") (pintype "passive"))
      (node (ref "JP99") (pin "8") (pinfunction "8_8") (pintype "passive"))
      (node (ref "MS2") (pin "#8") (pinfunction "GPIOA3_#8") (pintype "bidirectional"))
      (node (ref "MS2") (pin "8") (pinfunction "GPIOA3_8") (pintype "bidirectional"))
      (node (ref "MS2") (pin "@8") (pinfunction "GPIOA3_@8") (pintype "bidirectional"))
    )
    (net (code "7") (name "A4") (class "Default")
      (node (ref "JP100") (pin "1") (pinfunction "1_1") (pintype "passive"))
      (node (ref "JP100") (pin "2") (pinfunction "2_2") (pintype "passive"))
      (node (ref "JP100") (pin "3") (pinfunction "3_3") (pintype "passive"))
      (node (ref "JP100") (pin "4") (pinfunction "4_4") (pintype "passive"))
      (node (ref "JP100") (pin "5") (pinfunction "5_5") (pintype "passive"))
      (node (ref "JP100") (pin "6") (pinfunction "6_6") (pintype "passive"))
      (node (ref "JP100") (pin "7") (pinfunction "7_7") (pintype "passive"))
      (node (ref "JP100") (pin "8") (pinfunction "8_8") (pintype "passive"))
      (node (ref "MS2") (pin "#9") (pinfunction "GPIOA4_#9") (pintype "bidirectional"))
      (node (ref "MS2") (pin "9") (pinfunction "GPIOA4_9") (pintype "bidirectional"))
      (node (ref "MS2") (pin "@9") (pinfunction "GPIOA4_@9") (pintype "bidirectional"))
    )
    (net (code "8") (name "A5") (class "Default")
      (node (ref "JP101") (pin "1") (pinfunction "1_1") (pintype "passive"))
      (node (ref "JP101") (pin "2") (pinfunction "2_2") (pintype "passive"))
      (node (ref "JP101") (pin "3") (pinfunction "3_3") (pintype "passive"))
      (node (ref "JP101") (pin "4") (pinfunction "4_4") (pintype "passive"))
      (node (ref "JP101") (pin "5") (pinfunction "5_5") (pintype "passive"))
      (node (ref "JP101") (pin "6") (pinfunction "6_6") (pintype "passive"))
      (node (ref "JP101") (pin "7") (pinfunction "7_7") (pintype "passive"))
      (node (ref "JP101") (pin "8") (pinfunction "8_8") (pintype "passive"))
      (node (ref "MS2") (pin "#10") (pinfunction "GPIOA5_#10") (pintype "bidirectional"))
      (node (ref "MS2") (pin "10") (pinfunction "GPIOA5_10") (pintype "bidirectional"))
      (node (ref "MS2") (pin "@10") (pinfunction "GPIOA5_@10") (pintype "bidirectional"))
    )
    (net (code "9") (name "AREF") (class "Default")
      (node (ref "JP12") (pin "1") (pinfunction "1_1") (pintype "passive"))
      (node (ref "JP12") (pin "2") (pinfunction "2_2") (pintype "passive"))
      (node (ref "JP12") (pin "3") (pinfunction "3_3") (pintype "passive"))
      (node (ref "JP12") (pin "4") (pinfunction "4_4") (pintype "passive"))
      (node (ref "JP12") (pin "5") (pinfunction "5_5") (pintype "passive"))
      (node (ref "JP12") (pin "6") (pinfunction "6_6") (pintype "passive"))
      (node (ref "JP12") (pin "7") (pinfunction "7_7") (pintype "passive"))
      (node (ref "JP12") (pin "8") (pinfunction "8_8") (pintype "passive"))
      (node (ref "MS2") (pin "#3") (pinfunction "AREF_#3") (pintype "passive"))
      (node (ref "MS2") (pin "3") (pinfunction "AREF_3") (pintype "passive"))
      (node (ref "MS2") (pin "@3") (pinfunction "AREF_@3") (pintype "passive"))
    )
    (net (code "10") (name "D5") (class "Default")
      (node (ref "JP18") (pin "1") (pinfunction "1_1") (pintype "passive"))
      (node (ref "JP18") (pin "2") (pinfunction "2_2") (pintype "passive"))
      (node (ref "JP18") (pin "3") (pinfunction "3_3") (pintype "passive"))
      (node (ref "JP18") (pin "4") (pinfunction "4_4") (pintype "passive"))
      (node (ref "JP18") (pin "5") (pinfunction "5_5") (pintype "passive"))
      (node (ref "JP18") (pin "6") (pinfunction "6_6") (pintype "passive"))
      (node (ref "JP18") (pin "7") (pinfunction "7_7") (pintype "passive"))
      (node (ref "MS2") (pin "#19") (pinfunction "GPIO5_#19") (pintype "bidirectional"))
      (node (ref "MS2") (pin "19") (pinfunction "GPIO5_19") (pintype "bidirectional"))
      (node (ref "MS2") (pin "@19") (pinfunction "GPIO5_@19") (pintype "bidirectional"))
      (node (ref "R22") (pin "1") (pinfunction "1_1") (pintype "passive"))
    )
    (net (code "11") (name "D6") (class "Default")
      (node (ref "JP10") (pin "1") (pinfunction "1_1") (pintype "passive"))
      (node (ref "JP10") (pin "2") (pinfunction "2_2") (pintype "passive"))
      (node (ref "JP10") (pin "3") (pinfunction "3_3") (pintype "passive"))
      (node (ref "JP10") (pin "4") (pinfunction "4_4") (pintype "passive"))
      (node (ref "JP10") (pin "5") (pinfunction "5_5") (pintype "passive"))
      (node (ref "JP10") (pin "6") (pinfunction "6_6") (pintype "passive"))
      (node (ref "JP10") (pin "7") (pinfunction "7_7") (pintype "passive"))
      (node (ref "MS2") (pin "#20") (pinfunction "GPIO6_#20") (pintype "bidirectional"))
      (node (ref "MS2") (pin "20") (pinfunction "GPIO6_20") (pintype "bidirectional"))
      (node (ref "MS2") (pin "@20") (pinfunction "GPIO6_@20") (pintype "bidirectional"))
      (node (ref "R20") (pin "1") (pinfunction "1_1") (pintype "passive"))
    )
    (net (code "12") (name "D9") (class "Default")
      (node (ref "JP7") (pin "1") (pinfunction "1_1") (pintype "passive"))
      (node (ref "JP7") (pin "2") (pinfunction "2_2") (pintype "passive"))
      (node (ref "JP7") (pin "3") (pinfunction "3_3") (pintype "passive"))
      (node (ref "JP7") (pin "4") (pinfunction "4_4") (pintype "passive"))
      (node (ref "JP7") (pin "5") (pinfunction "5_5") (pintype "passive"))
      (node (ref "JP7") (pin "6") (pinfunction "6_6") (pintype "passive"))
      (node (ref "JP7") (pin "7") (pinfunction "7_7") (pintype "passive"))
      (node (ref "MS2") (pin "#21") (pinfunction "GPIO9_#21") (pintype "bidirectional"))
      (node (ref "MS2") (pin "21") (pinfunction "GPIO9_21") (pintype "bidirectional"))
      (node (ref "MS2") (pin "@21") (pinfunction "GPIO9_@21") (pintype "bidirectional"))
      (node (ref "R18") (pin "1") (pinfunction "1_1") (pintype "passive"))
    )
    (net (code "13") (name "D10") (class "Default")
      (node (ref "JP20") (pin "1") (pinfunction "1_1") (pintype "passive"))
      (node (ref "JP20") (pin "2") (pinfunction "2_2") (pintype "passive"))
      (node (ref "JP20") (pin "3") (pinfunction "3_3") (pintype "passive"))
      (node (ref "JP20") (pin "4") (pinfunction "4_4") (pintype "passive"))
      (node (ref "JP20") (pin "5") (pinfunction "5_5") (pintype "passive"))
      (node (ref "JP20") (pin "6") (pinfunction "6_6") (pintype "passive"))
      (node (ref "JP20") (pin "7") (pinfunction "7_7") (pintype "passive"))
      (node (ref "MS2") (pin "#22") (pinfunction "GPIO10_#22") (pintype "bidirectional"))
      (node (ref "MS2") (pin "22") (pinfunction "GPIO10_22") (pintype "bidirectional"))
      (node (ref "MS2") (pin "@22") (pinfunction "GPIO10_@22") (pintype "bidirectional"))
      (node (ref "R16") (pin "1") (pinfunction "1_1") (pintype "passive"))
    )
    (net (code "14") (name "D11") (class "Default")
      (node (ref "JP21") (pin "1") (pinfunction "1_1") (pintype "passive"))
      (node (ref "JP21") (pin "2") (pinfunction "2_2") (pintype "passive"))
      (node (ref "JP21") (pin "3") (pinfunction "3_3") (pintype "passive"))
      (node (ref "JP21") (pin "4") (pinfunction "4_4") (pintype "passive"))
      (node (ref "JP21") (pin "5") (pinfunction "5_5") (pintype "passive"))
      (node (ref "JP21") (pin "6") (pinfunction "6_6") (pintype "passive"))
      (node (ref "JP21") (pin "7") (pinfunction "7_7") (pintype "passive"))
      (node (ref "MS2") (pin "#23") (pinfunction "GPIO11_#23") (pintype "bidirectional"))
      (node (ref "MS2") (pin "23") (pinfunction "GPIO11_23") (pintype "bidirectional"))
      (node (ref "MS2") (pin "@23") (pinfunction "GPIO11_@23") (pintype "bidirectional"))
      (node (ref "R14") (pin "1") (pinfunction "1_1") (pintype "passive"))
    )
    (net (code "15") (name "D12") (class "Default")
      (node (ref "JP22") (pin "1") (pinfunction "1_1") (pintype "passive"))
      (node (ref "JP22") (pin "2") (pinfunction "2_2") (pintype "passive"))
      (node (ref "JP22") (pin "3") (pinfunction "3_3") (pintype "passive"))
      (node (ref "JP22") (pin "4") (pinfunction "4_4") (pintype "passive"))
      (node (ref "JP22") (pin "5") (pinfunction "5_5") (pintype "passive"))
      (node (ref "JP22") (pin "6") (pinfunction "6_6") (pintype "passive"))
      (node (ref "JP22") (pin "7") (pinfunction "7_7") (pintype "passive"))
      (node (ref "MS2") (pin "#24") (pinfunction "GPIO12_#24") (pintype "bidirectional"))
      (node (ref "MS2") (pin "24") (pinfunction "GPIO12_24") (pintype "bidirectional"))
      (node (ref "MS2") (pin "@24") (pinfunction "GPIO12_@24") (pintype "bidirectional"))
      (node (ref "R12") (pin "1") (pinfunction "1_1") (pintype "passive"))
    )
    (net (code "16") (name "D13") (class "Default")
      (node (ref "JP26") (pin "1") (pinfunction "1_1") (pintype "passive"))
      (node (ref "JP26") (pin "2") (pinfunction "2_2") (pintype "passive"))
      (node (ref "JP26") (pin "3") (pinfunction "3_3") (pintype "passive"))
      (node (ref "JP26") (pin "4") (pinfunction "4_4") (pintype "passive"))
      (node (ref "JP26") (pin "5") (pinfunction "5_5") (pintype "passive"))
      (node (ref "JP26") (pin "6") (pinfunction "6_6") (pintype "passive"))
      (node (ref "JP26") (pin "7") (pinfunction "7_7") (pintype "passive"))
      (node (ref "MS2") (pin "#25") (pinfunction "GPIO13_#25") (pintype "bidirectional"))
      (node (ref "MS2") (pin "25") (pinfunction "GPIO13_25") (pintype "bidirectional"))
      (node (ref "MS2") (pin "@25") (pinfunction "GPIO13_@25") (pintype "bidirectional"))
      (node (ref "R10") (pin "1") (pinfunction "1_1") (pintype "passive"))
    )
    (net (code "17") (name "EN") (class "Default")
      (node (ref "JP19") (pin "1") (pinfunction "1_1") (pintype "passive"))
      (node (ref "JP19") (pin "2") (pinfunction "2_2") (pintype "passive"))
      (node (ref "JP19") (pin "3") (pinfunction "3_3") (pintype "passive"))
      (node (ref "JP19") (pin "4") (pinfunction "4_4") (pintype "passive"))
      (node (ref "JP19") (pin "5") (pinfunction "5_5") (pintype "passive"))
      (node (ref "JP19") (pin "6") (pinfunction "6_6") (pintype "passive"))
      (node (ref "JP19") (pin "7") (pinfunction "7_7") (pintype "passive"))
      (node (ref "MS2") (pin "#27") (pinfunction "EN_#27") (pintype "passive"))
      (node (ref "MS2") (pin "27") (pinfunction "EN_27") (pintype "passive"))
      (node (ref "MS2") (pin "@27") (pinfunction "EN_@27") (pintype "passive"))
    )
    (net (code "18") (name "GND") (class "Default")
      (node (ref "C1") (pin "2") (pinfunction "2_2") (pintype "passive"))
      (node (ref "C2") (pin "2") (pinfunction "2_2") (pintype "passive"))
      (node (ref "C3") (pin "2") (pinfunction "2_2") (pintype "passive"))
      (node (ref "C4") (pin "2") (pinfunction "2_2") (pintype "passive"))
      (node (ref "C5") (pin "2") (pinfunction "2_2") (pintype "passive"))
      (node (ref "C6") (pin "2") (pinfunction "2_2") (pintype "passive"))
      (node (ref "C9") (pin "C") (pinfunction "-_C") (pintype "passive"))
      (node (ref "CAP") (pin "2") (pinfunction "-_2") (pintype "passive"))
      (node (ref "D1") (pin "C") (pinfunction "C_C") (pintype "passive"))
      (node (ref "IC1") (pin "GND") (pinfunction "GND_GND") (pintype "input"))
      (node (ref "JP105") (pin "1") (pinfunction "1_1") (pintype "passive"))
      (node (ref "JP105") (pin "2") (pinfunction "2_2") (pintype "passive"))
      (node (ref "JP105") (pin "3") (pinfunction "3_3") (pintype "passive"))
      (node (ref "JP106") (pin "1") (pinfunction "1_1") (pintype "passive"))
      (node (ref "JP106") (pin "2") (pinfunction "2_2") (pintype "passive"))
      (node (ref "JP106") (pin "3") (pinfunction "3_3") (pintype "passive"))
      (node (ref "JP109") (pin "1") (pinfunction "1_1") (pintype "passive"))
      (node (ref "JP109") (pin "2") (pinfunction "2_2") (pintype "passive"))
      (node (ref "JP109") (pin "3") (pinfunction "3_3") (pintype "passive"))
      (node (ref "JP109") (pin "4") (pinfunction "4_4") (pintype "passive"))
      (node (ref "JP11") (pin "1") (pinfunction "1_1") (pintype "passive"))
      (node (ref "JP11") (pin "10") (pinfunction "10_10") (pintype "passive"))
      (node (ref "JP11") (pin "2") (pinfunction "2_2") (pintype "passive"))
      (node (ref "JP11") (pin "3") (pinfunction "3_3") (pintype "passive"))
      (node (ref "JP11") (pin "4") (pinfunction "4_4") (pintype "passive"))
      (node (ref "JP11") (pin "5") (pinfunction "5_5") (pintype "passive"))
      (node (ref "JP11") (pin "6") (pinfunction "6_6") (pintype "passive"))
      (node (ref "JP11") (pin "7") (pinfunction "7_7") (pintype "passive"))
      (node (ref "JP11") (pin "8") (pinfunction "8_8") (pintype "passive"))
      (node (ref "JP11") (pin "9") (pinfunction "9_9") (pintype "passive"))
      (node (ref "JP110") (pin "GND") (pinfunction "GND_GND") (pintype "bidirectional"))
      (node (ref "JP110") (pin "GNDBREAK") (pinfunction "GNDBREAK_GNDBREAK") (pintype "bidirectional"))
      (node (ref "JP14") (pin "1") (pinfunction "1_1") (pintype "passive"))
      (node (ref "JP14") (pin "10") (pinfunction "10_10") (pintype "passive"))
      (node (ref "JP14") (pin "11") (pinfunction "11_11") (pintype "passive"))
      (node (ref "JP14") (pin "12") (pinfunction "12_12") (pintype "passive"))
      (node (ref "JP14") (pin "13") (pinfunction "13_13") (pintype "passive"))
      (node (ref "JP14") (pin "14") (pinfunction "14_14") (pintype "passive"))
      (node (ref "JP14") (pin "15") (pinfunction "15_15") (pintype "passive"))
      (node (ref "JP14") (pin "16") (pinfunction "16_16") (pintype "passive"))
      (node (ref "JP14") (pin "2") (pinfunction "2_2") (pintype "passive"))
      (node (ref "JP14") (pin "3") (pinfunction "3_3") (pintype "passive"))
      (node (ref "JP14") (pin "4") (pinfunction "4_4") (pintype "passive"))
      (node (ref "JP14") (pin "5") (pinfunction "5_5") (pintype "passive"))
      (node (ref "JP14") (pin "6") (pinfunction "6_6") (pintype "passive"))
      (node (ref "JP14") (pin "7") (pinfunction "7_7") (pintype "passive"))
      (node (ref "JP14") (pin "8") (pinfunction "8_8") (pintype "passive"))
      (node (ref "JP14") (pin "9") (pinfunction "9_9") (pintype "passive"))
      (node (ref "JP29") (pin "1") (pinfunction "1_1") (pintype "passive"))
      (node (ref "JP29") (pin "10") (pinfunction "10_10") (pintype "passive"))
      (node (ref "JP29") (pin "2") (pinfunction "2_2") (pintype "passive"))
      (node (ref "JP29") (pin "3") (pinfunction "3_3") (pintype "passive"))
      (node (ref "JP29") (pin "4") (pinfunction "4_4") (pintype "passive"))
      (node (ref "JP29") (pin "5") (pinfunction "5_5") (pintype "passive"))
      (node (ref "JP29") (pin "6") (pinfunction "6_6") (pintype "passive"))
      (node (ref "JP29") (pin "7") (pinfunction "7_7") (pintype "passive"))
      (node (ref "JP29") (pin "8") (pinfunction "8_8") (pintype "passive"))
      (node (ref "JP29") (pin "9") (pinfunction "9_9") (pintype "passive"))
      (node (ref "JP32") (pin "1") (pinfunction "1_1") (pintype "passive"))
      (node (ref "JP32") (pin "2") (pinfunction "2_2") (pintype "passive"))
      (node (ref "JP33") (pin "1") (pinfunction "1_1") (pintype "passive"))
      (node (ref "JP4") (pin "1") (pinfunction "1_1") (pintype "passive"))
      (node (ref "JP9") (pin "1") (pinfunction "1_1") (pintype "passive"))
      (node (ref "JP9") (pin "2") (pinfunction "2_2") (pintype "passive"))
      (node (ref "JP9") (pin "3") (pinfunction "3_3") (pintype "passive"))
      (node (ref "JP9") (pin "4") (pinfunction "4_4") (pintype "passive"))
      (node (ref "JP9") (pin "5") (pinfunction "5_5") (pintype "passive"))
      (node (ref "JP9") (pin "6") (pinfunction "6_6") (pintype "passive"))
      (node (ref "JP9") (pin "7") (pinfunction "7_7") (pintype "passive"))
      (node (ref "JP9") (pin "8") (pinfunction "8_8") (pintype "passive"))
      (node (ref "MS2") (pin "#4") (pinfunction "GND_#4") (pintype "power_in"))
      (node (ref "MS2") (pin "4") (pinfunction "GND_4") (pintype "power_in"))
      (node (ref "MS2") (pin "@4") (pinfunction "GND_@4") (pintype "power_in"))
    )
    (net (code "19") (name "LED_COMMON") (class "Default")
      (node (ref "JP30") (pin "1") (pinfunction "1_1") (pintype "passive"))
      (node (ref "R11") (pin "2") (pinfunction "2_2") (pintype "passive"))
      (node (ref "R13") (pin "2") (pinfunction "2_2") (pintype "passive"))
      (node (ref "R15") (pin "2") (pinfunction "2_2") (pintype "passive"))
      (node (ref "R17") (pin "2") (pinfunction "2_2") (pintype "passive"))
      (node (ref "R19") (pin "2") (pinfunction "2_2") (pintype "passive"))
      (node (ref "R21") (pin "2") (pinfunction "2_2") (pintype "passive"))
      (node (ref "R23") (pin "2") (pinfunction "2_2") (pintype "passive"))
      (node (ref "R25") (pin "1") (pinfunction "1_1") (pintype "passive"))
      (node (ref "R27") (pin "1") (pinfunction "1_1") (pintype "passive"))
    )
    (net (code "20") (name "MISO") (class "Default")
      (node (ref "JP104") (pin "1") (pinfunction "1_1") (pintype "passive"))
      (node (ref "JP104") (pin "2") (pinfunction "2_2") (pintype "passive"))
      (node (ref "JP104") (pin "3") (pinfunction "3_3") (pintype "passive"))
      (node (ref "JP104") (pin "4") (pinfunction "4_4") (pintype "passive"))
      (node (ref "JP104") (pin "5") (pinfunction "5_5") (pintype "passive"))
      (node (ref "JP104") (pin "6") (pinfunction "6_6") (pintype "passive"))
      (node (ref "JP104") (pin "7") (pinfunction "7_7") (pintype "passive"))
      (node (ref "JP104") (pin "8") (pinfunction "8_8") (pintype "passive"))
      (node (ref "MS2") (pin "#13") (pinfunction "GPIOMISO_#13") (pintype "bidirectional"))
      (node (ref "MS2") (pin "13") (pinfunction "GPIOMISO_13") (pintype "bidirectional"))
      (node (ref "MS2") (pin "@13") (pinfunction "GPIOMISO_@13") (pintype "bidirectional"))
    )
    (net (code "21") (name "MOSI") (class "Default")
      (node (ref "JP103") (pin "1") (pinfunction "1_1") (pintype "passive"))
      (node (ref "JP103") (pin "2") (pinfunction "2_2") (pintype "passive"))
      (node (ref "JP103") (pin "3") (pinfunction "3_3") (pintype "passive"))
      (node (ref "JP103") (pin "4") (pinfunction "4_4") (pintype "passive"))
      (node (ref "JP103") (pin "5") (pinfunction "5_5") (pintype "passive"))
      (node (ref "JP103") (pin "6") (pinfunction "6_6") (pintype "passive"))
      (node (ref "JP103") (pin "7") (pinfunction "7_7") (pintype "passive"))
      (node (ref "JP103") (pin "8") (pinfunction "8_8") (pintype "passive"))
      (node (ref "MS2") (pin "#12") (pinfunction "GPIOMOSI_#12") (pintype "bidirectional"))
      (node (ref "MS2") (pin "12") (pinfunction "GPIOMOSI_12") (pintype "bidirectional"))
      (node (ref "MS2") (pin "@12") (pinfunction "GPIOMOSI_@12") (pintype "bidirectional"))
    )
    (net (code "22") (name "Net-(D1-PadA)") (class "Default")
      (node (ref "D1") (pin "A") (pinfunction "A_A") (pintype "passive"))
      (node (ref "R1") (pin "1") (pinfunction "1_1") (pintype "passive"))
    )
    (net (code "23") (name "Net-(JP31-Pad1)") (class "Default")
      (node (ref "JP31") (pin "1") (pinfunction "1_1") (pintype "passive"))
      (node (ref "JP31") (pin "2") (pinfunction "2_2") (pintype "passive"))
      (node (ref "R31") (pin "2") (pinfunction "2_2") (pintype "passive"))
    )
    (net (code "24") (name "Net-(JP34-Pad1)") (class "Default")
      (node (ref "JP34") (pin "1") (pinfunction "1_1") (pintype "passive"))
      (node (ref "JP34") (pin "2") (pinfunction "2_2") (pintype "passive"))
      (node (ref "R48") (pin "2") (pinfunction "2_2") (pintype "passive"))
    )
    (net (code "25") (name "Net-(JP35-Pad1)") (class "Default")
      (node (ref "JP35") (pin "1") (pinfunction "1_1") (pintype "passive"))
      (node (ref "R37") (pin "1") (pinfunction "1_1") (pintype "passive"))
    )
    (net (code "26") (name "Net-(JP36-Pad1)") (class "Default")
      (node (ref "JP36") (pin "1") (pinfunction "1_1") (pintype "passive"))
      (node (ref "R30") (pin "1") (pinfunction "1_1") (pintype "passive"))
    )
    (net (code "27") (name "Net-(JP37-Pad1)") (class "Default")
      (node (ref "JP37") (pin "1") (pinfunction "1_1") (pintype "passive"))
      (node (ref "R46") (pin "1") (pinfunction "1_1") (pintype "passive"))
    )
    (net (code "28") (name "Net-(JP38-Pad1)") (class "Default")
      (node (ref "JP38") (pin "1") (pinfunction "1_1") (pintype "passive"))
      (node (ref "JP38") (pin "2") (pinfunction "2_2") (pintype "passive"))
      (node (ref "R32") (pin "2") (pinfunction "2_2") (pintype "passive"))
    )
    (net (code "29") (name "Net-(JP39-Pad1)") (class "Default")
      (node (ref "JP39") (pin "1") (pinfunction "1_1") (pintype "passive"))
      (node (ref "JP39") (pin "2") (pinfunction "2_2") (pintype "passive"))
      (node (ref "R49") (pin "2") (pinfunction "2_2") (pintype "passive"))
    )
    (net (code "30") (name "Net-(JP40-Pad1)") (class "Default")
      (node (ref "JP40") (pin "1") (pinfunction "1_1") (pintype "passive"))
      (node (ref "R31") (pin "1") (pinfunction "1_1") (pintype "passive"))
    )
    (net (code "31") (name "Net-(JP41-Pad1)") (class "Default")
      (node (ref "JP41") (pin "1") (pinfunction "1_1") (pintype "passive"))
      (node (ref "R32") (pin "1") (pinfunction "1_1") (pintype "passive"))
    )
    (net (code "32") (name "Net-(JP42-Pad1)") (class "Default")
      (node (ref "JP42") (pin "1") (pinfunction "1_1") (pintype "passive"))
      (node (ref "R33") (pin "1") (pinfunction "1_1") (pintype "passive"))
    )
    (net (code "33") (name "Net-(JP43-Pad1)") (class "Default")
      (node (ref "JP43") (pin "1") (pinfunction "1_1") (pintype "passive"))
      (node (ref "R34") (pin "1") (pinfunction "1_1") (pintype "passive"))
    )
    (net (code "34") (name "Net-(JP44-Pad1)") (class "Default")
      (node (ref "JP44") (pin "1") (pinfunction "1_1") (pintype "passive"))
      (node (ref "R35") (pin "1") (pinfunction "1_1") (pintype "passive"))
    )
    (net (code "35") (name "Net-(JP45-Pad1)") (class "Default")
      (node (ref "JP45") (pin "1") (pinfunction "1_1") (pintype "passive"))
      (node (ref "R36") (pin "1") (pinfunction "1_1") (pintype "passive"))
    )
    (net (code "36") (name "Net-(JP46-Pad1)") (class "Default")
      (node (ref "JP46") (pin "1") (pinfunction "1_1") (pintype "passive"))
      (node (ref "R38") (pin "1") (pinfunction "1_1") (pintype "passive"))
    )
    (net (code "37") (name "Net-(JP47-Pad1)") (class "Default")
      (node (ref "JP47") (pin "1") (pinfunction "1_1") (pintype "passive"))
      (node (ref "R39") (pin "1") (pinfunction "1_1") (pintype "passive"))
    )
    (net (code "38") (name "Net-(JP48-Pad1)") (class "Default")
      (node (ref "JP48") (pin "1") (pinfunction "1_1") (pintype "passive"))
      (node (ref "R40") (pin "1") (pinfunction "1_1") (pintype "passive"))
    )
    (net (code "39") (name "Net-(JP49-Pad1)") (class "Default")
      (node (ref "JP49") (pin "1") (pinfunction "1_1") (pintype "passive"))
      (node (ref "R41") (pin "1") (pinfunction "1_1") (pintype "passive"))
    )
    (net (code "40") (name "Net-(JP50-Pad1)") (class "Default")
      (node (ref "JP50") (pin "1") (pinfunction "1_1") (pintype "passive"))
      (node (ref "R42") (pin "1") (pinfunction "1_1") (pintype "passive"))
    )
    (net (code "41") (name "Net-(JP51-Pad1)") (class "Default")
      (node (ref "JP51") (pin "1") (pinfunction "1_1") (pintype "passive"))
      (node (ref "R43") (pin "1") (pinfunction "1_1") (pintype "passive"))
    )
    (net (code "42") (name "Net-(JP52-Pad1)") (class "Default")
      (node (ref "JP52") (pin "1") (pinfunction "1_1") (pintype "passive"))
      (node (ref "R44") (pin "1") (pinfunction "1_1") (pintype "passive"))
    )
    (net (code "43") (name "Net-(JP53-Pad1)") (class "Default")
      (node (ref "JP53") (pin "1") (pinfunction "1_1") (pintype "passive"))
      (node (ref "R45") (pin "1") (pinfunction "1_1") (pintype "passive"))
    )
    (net (code "44") (name "Net-(JP55-Pad1)") (class "Default")
      (node (ref "JP55") (pin "1") (pinfunction "1_1") (pintype "passive"))
      (node (ref "JP55") (pin "2") (pinfunction "2_2") (pintype "passive"))
      (node (ref "R30") (pin "2") (pinfunction "2_2") (pintype "passive"))
    )
    (net (code "45") (name "Net-(JP56-Pad1)") (class "Default")
      (node (ref "JP56") (pin "1") (pinfunction "1_1") (pintype "passive"))
      (node (ref "R47") (pin "1") (pinfunction "1_1") (pintype "passive"))
    )
    (net (code "46") (name "Net-(JP57-Pad1)") (class "Default")
      (node (ref "JP57") (pin "1") (pinfunction "1_1") (pintype "passive"))
      (node (ref "R48") (pin "1") (pinfunction "1_1") (pintype "passive"))
    )
    (net (code "47") (name "Net-(JP58-Pad1)") (class "Default")
      (node (ref "JP58") (pin "1") (pinfunction "1_1") (pintype "passive"))
      (node (ref "R49") (pin "1") (pinfunction "1_1") (pintype "passive"))
    )
    (net (code "48") (name "Net-(JP59-Pad1)") (class "Default")
      (node (ref "JP59") (pin "1") (pinfunction "1_1") (pintype "passive"))
      (node (ref "R50") (pin "1") (pinfunction "1_1") (pintype "passive"))
    )
    (net (code "49") (name "Net-(JP60-Pad1)") (class "Default")
      (node (ref "JP60") (pin "1") (pinfunction "1_1") (pintype "passive"))
      (node (ref "R51") (pin "1") (pinfunction "1_1") (pintype "passive"))
    )
    (net (code "50") (name "Net-(JP61-Pad1)") (class "Default")
      (node (ref "JP61") (pin "1") (pinfunction "1_1") (pintype "passive"))
      (node (ref "R52") (pin "1") (pinfunction "1_1") (pintype "passive"))
    )
    (net (code "51") (name "Net-(JP62-Pad1)") (class "Default")
      (node (ref "JP62") (pin "1") (pinfunction "1_1") (pintype "passive"))
      (node (ref "R53") (pin "1") (pinfunction "1_1") (pintype "passive"))
    )
    (net (code "52") (name "Net-(JP63-Pad1)") (class "Default")
      (node (ref "JP63") (pin "1") (pinfunction "1_1") (pintype "passive"))
      (node (ref "R54") (pin "1") (pinfunction "1_1") (pintype "passive"))
    )
    (net (code "53") (name "Net-(JP64-Pad1)") (class "Default")
      (node (ref "JP64") (pin "1") (pinfunction "1_1") (pintype "passive"))
      (node (ref "R55") (pin "1") (pinfunction "1_1") (pintype "passive"))
    )
    (net (code "54") (name "Net-(JP65-Pad1)") (class "Default")
      (node (ref "JP65") (pin "1") (pinfunction "1_1") (pintype "passive"))
      (node (ref "R56") (pin "1") (pinfunction "1_1") (pintype "passive"))
    )
    (net (code "55") (name "Net-(JP66-Pad1)") (class "Default")
      (node (ref "JP66") (pin "1") (pinfunction "1_1") (pintype "passive"))
      (node (ref "R57") (pin "1") (pinfunction "1_1") (pintype "passive"))
    )
    (net (code "56") (name "Net-(JP67-Pad1)") (class "Default")
      (node (ref "JP67") (pin "1") (pinfunction "1_1") (pintype "passive"))
      (node (ref "R58") (pin "1") (pinfunction "1_1") (pintype "passive"))
    )
    (net (code "57") (name "Net-(JP68-Pad1)") (class "Default")
      (node (ref "JP68") (pin "1") (pinfunction "1_1") (pintype "passive"))
      (node (ref "R59") (pin "1") (pinfunction "1_1") (pintype "passive"))
    )
    (net (code "58") (name "Net-(JP69-Pad1)") (class "Default")
      (node (ref "JP69") (pin "1") (pinfunction "1_1") (pintype "passive"))
      (node (ref "R60") (pin "1") (pinfunction "1_1") (pintype "passive"))
    )
    (net (code "59") (name "Net-(JP70-Pad1)") (class "Default")
      (node (ref "JP70") (pin "1") (pinfunction "1_1") (pintype "passive"))
      (node (ref "R61") (pin "1") (pinfunction "1_1") (pintype "passive"))
    )
    (net (code "60") (name "Net-(JP71-Pad1)") (class "Default")
      (node (ref "JP71") (pin "1") (pinfunction "1_1") (pintype "passive"))
      (node (ref "JP71") (pin "2") (pinfunction "2_2") (pintype "passive"))
      (node (ref "R46") (pin "2") (pinfunction "2_2") (pintype "passive"))
    )
    (net (code "61") (name "Net-(JP72-Pad1)") (class "Default")
      (node (ref "JP72") (pin "1") (pinfunction "1_1") (pintype "passive"))
      (node (ref "JP72") (pin "2") (pinfunction "2_2") (pintype "passive"))
      (node (ref "R47") (pin "2") (pinfunction "2_2") (pintype "passive"))
    )
    (net (code "62") (name "Net-(JP73-Pad1)") (class "Default")
      (node (ref "JP73") (pin "1") (pinfunction "1_1") (pintype "passive"))
      (node (ref "JP73") (pin "2") (pinfunction "2_2") (pintype "passive"))
      (node (ref "R50") (pin "2") (pinfunction "2_2") (pintype "passive"))
    )
    (net (code "63") (name "Net-(JP74-Pad1)") (class "Default")
      (node (ref "JP74") (pin "1") (pinfunction "1_1") (pintype "passive"))
      (node (ref "JP74") (pin "2") (pinfunction "2_2") (pintype "passive"))
      (node (ref "R51") (pin "2") (pinfunction "2_2") (pintype "passive"))
    )
    (net (code "64") (name "Net-(JP75-Pad1)") (class "Default")
      (node (ref "JP75") (pin "1") (pinfunction "1_1") (pintype "passive"))
      (node (ref "JP75") (pin "2") (pinfunction "2_2") (pintype "passive"))
      (node (ref "R52") (pin "2") (pinfunction "2_2") (pintype "passive"))
    )
    (net (code "65") (name "Net-(JP76-Pad1)") (class "Default")
      (node (ref "JP76") (pin "1") (pinfunction "1_1") (pintype "passive"))
      (node (ref "JP76") (pin "2") (pinfunction "2_2") (pintype "passive"))
      (node (ref "R53") (pin "2") (pinfunction "2_2") (pintype "passive"))
    )
    (net (code "66") (name "Net-(JP77-Pad1)") (class "Default")
      (node (ref "JP77") (pin "1") (pinfunction "1_1") (pintype "passive"))
      (node (ref "JP77") (pin "2") (pinfunction "2_2") (pintype "passive"))
      (node (ref "R54") (pin "2") (pinfunction "2_2") (pintype "passive"))
    )
    (net (code "67") (name "Net-(JP78-Pad1)") (class "Default")
      (node (ref "JP78") (pin "1") (pinfunction "1_1") (pintype "passive"))
      (node (ref "JP78") (pin "2") (pinfunction "2_2") (pintype "passive"))
      (node (ref "R55") (pin "2") (pinfunction "2_2") (pintype "passive"))
    )
    (net (code "68") (name "Net-(JP79-Pad1)") (class "Default")
      (node (ref "JP79") (pin "1") (pinfunction "1_1") (pintype "passive"))
      (node (ref "JP79") (pin "2") (pinfunction "2_2") (pintype "passive"))
      (node (ref "R56") (pin "2") (pinfunction "2_2") (pintype "passive"))
    )
    (net (code "69") (name "Net-(JP80-Pad1)") (class "Default")
      (node (ref "JP80") (pin "1") (pinfunction "1_1") (pintype "passive"))
      (node (ref "JP80") (pin "2") (pinfunction "2_2") (pintype "passive"))
      (node (ref "R57") (pin "2") (pinfunction "2_2") (pintype "passive"))
    )
    (net (code "70") (name "Net-(JP81-Pad1)") (class "Default")
      (node (ref "JP81") (pin "1") (pinfunction "1_1") (pintype "passive"))
      (node (ref "JP81") (pin "2") (pinfunction "2_2") (pintype "passive"))
      (node (ref "R58") (pin "2") (pinfunction "2_2") (pintype "passive"))
    )
    (net (code "71") (name "Net-(JP82-Pad1)") (class "Default")
      (node (ref "JP82") (pin "1") (pinfunction "1_1") (pintype "passive"))
      (node (ref "JP82") (pin "2") (pinfunction "2_2") (pintype "passive"))
      (node (ref "R59") (pin "2") (pinfunction "2_2") (pintype "passive"))
    )
    (net (code "72") (name "Net-(JP83-Pad1)") (class "Default")
      (node (ref "JP83") (pin "1") (pinfunction "1_1") (pintype "passive"))
      (node (ref "JP83") (pin "2") (pinfunction "2_2") (pintype "passive"))
      (node (ref "R60") (pin "2") (pinfunction "2_2") (pintype "passive"))
    )
    (net (code "73") (name "Net-(JP84-Pad1)") (class "Default")
      (node (ref "JP84") (pin "1") (pinfunction "1_1") (pintype "passive"))
      (node (ref "JP84") (pin "2") (pinfunction "2_2") (pintype "passive"))
      (node (ref "R61") (pin "2") (pinfunction "2_2") (pintype "passive"))
    )
    (net (code "74") (name "Net-(JP85-Pad1)") (class "Default")
      (node (ref "JP85") (pin "1") (pinfunction "1_1") (pintype "passive"))
      (node (ref "JP85") (pin "2") (pinfunction "2_2") (pintype "passive"))
      (node (ref "R33") (pin "2") (pinfunction "2_2") (pintype "passive"))
    )
    (net (code "75") (name "Net-(JP86-Pad1)") (class "Default")
      (node (ref "JP86") (pin "1") (pinfunction "1_1") (pintype "passive"))
      (node (ref "JP86") (pin "2") (pinfunction "2_2") (pintype "passive"))
      (node (ref "R34") (pin "2") (pinfunction "2_2") (pintype "passive"))
    )
    (net (code "76") (name "Net-(JP87-Pad1)") (class "Default")
      (node (ref "JP87") (pin "1") (pinfunction "1_1") (pintype "passive"))
      (node (ref "JP87") (pin "2") (pinfunction "2_2") (pintype "passive"))
      (node (ref "R35") (pin "2") (pinfunction "2_2") (pintype "passive"))
    )
    (net (code "77") (name "Net-(JP88-Pad1)") (class "Default")
      (node (ref "JP88") (pin "1") (pinfunction "1_1") (pintype "passive"))
      (node (ref "JP88") (pin "2") (pinfunction "2_2") (pintype "passive"))
      (node (ref "R36") (pin "2") (pinfunction "2_2") (pintype "passive"))
    )
    (net (code "78") (name "Net-(JP89-Pad1)") (class "Default")
      (node (ref "JP89") (pin "1") (pinfunction "1_1") (pintype "passive"))
      (node (ref "JP89") (pin "2") (pinfunction "2_2") (pintype "passive"))
      (node (ref "R37") (pin "2") (pinfunction "2_2") (pintype "passive"))
    )
    (net (code "79") (name "Net-(JP90-Pad1)") (class "Default")
      (node (ref "JP90") (pin "1") (pinfunction "1_1") (pintype "passive"))
      (node (ref "JP90") (pin "2") (pinfunction "2_2") (pintype "passive"))
      (node (ref "R38") (pin "2") (pinfunction "2_2") (pintype "passive"))
    )
    (net (code "80") (name "Net-(JP91-Pad1)") (class "Default")
      (node (ref "JP91") (pin "1") (pinfunction "1_1") (pintype "passive"))
      (node (ref "JP91") (pin "2") (pinfunction "2_2") (pintype "passive"))
      (node (ref "R39") (pin "2") (pinfunction "2_2") (pintype "passive"))
    )
    (net (code "81") (name "Net-(JP92-Pad1)") (class "Default")
      (node (ref "JP92") (pin "1") (pinfunction "1_1") (pintype "passive"))
      (node (ref "JP92") (pin "2") (pinfunction "2_2") (pintype "passive"))
      (node (ref "R40") (pin "2") (pinfunction "2_2") (pintype "passive"))
    )
    (net (code "82") (name "Net-(JP93-Pad1)") (class "Default")
      (node (ref "JP93") (pin "1") (pinfunction "1_1") (pintype "passive"))
      (node (ref "JP93") (pin "2") (pinfunction "2_2") (pintype "passive"))
      (node (ref "R41") (pin "2") (pinfunction "2_2") (pintype "passive"))
    )
    (net (code "83") (name "Net-(JP94-Pad1)") (class "Default")
      (node (ref "JP94") (pin "1") (pinfunction "1_1") (pintype "passive"))
      (node (ref "JP94") (pin "2") (pinfunction "2_2") (pintype "passive"))
      (node (ref "R42") (pin "2") (pinfunction "2_2") (pintype "passive"))
    )
    (net (code "84") (name "Net-(JP95-Pad1)") (class "Default")
      (node (ref "JP95") (pin "1") (pinfunction "1_1") (pintype "passive"))
      (node (ref "JP95") (pin "2") (pinfunction "2_2") (pintype "passive"))
      (node (ref "R43") (pin "2") (pinfunction "2_2") (pintype "passive"))
    )
    (net (code "85") (name "Net-(JP96-Pad1)") (class "Default")
      (node (ref "JP96") (pin "1") (pinfunction "1_1") (pintype "passive"))
      (node (ref "JP96") (pin "2") (pinfunction "2_2") (pintype "passive"))
      (node (ref "R44") (pin "2") (pinfunction "2_2") (pintype "passive"))
    )
    (net (code "86") (name "Net-(JP97-Pad1)") (class "Default")
      (node (ref "JP97") (pin "1") (pinfunction "1_1") (pintype "passive"))
      (node (ref "JP97") (pin "2") (pinfunction "2_2") (pintype "passive"))
      (node (ref "R45") (pin "2") (pinfunction "2_2") (pintype "passive"))
    )
    (net (code "87") (name "Net-(JP113-Pad1)") (class "Default")
      (node (ref "JP113") (pin "1") (pinfunction "1_1") (pintype "passive"))
      (node (ref "U1") (pin "4") (pinfunction "4_4") (pintype "bidirectional"))
    )
    (net (code "88") (name "Net-(JP113-Pad2)") (class "Default")
      (node (ref "JP113") (pin "2") (pinfunction "2_2") (pintype "passive"))
      (node (ref "U1") (pin "3") (pinfunction "3_3") (pintype "bidirectional"))
    )
    (net (code "89") (name "Net-(JP113-Pad3)") (class "Default")
      (node (ref "JP113") (pin "3") (pinfunction "3_3") (pintype "passive"))
      (node (ref "U1") (pin "2") (pinfunction "2_2") (pintype "bidirectional"))
    )
    (net (code "90") (name "Net-(JP113-Pad4)") (class "Default")
      (node (ref "JP113") (pin "4") (pinfunction "4_4") (pintype "passive"))
      (node (ref "U1") (pin "1") (pinfunction "1_1") (pintype "bidirectional"))
    )
    (net (code "91") (name "Net-(JP114-Pad1)") (class "Default")
      (node (ref "JP114") (pin "1") (pinfunction "1_1") (pintype "passive"))
      (node (ref "U1") (pin "8") (pinfunction "8_8") (pintype "bidirectional"))
    )
    (net (code "92") (name "Net-(JP114-Pad2)") (class "Default")
      (node (ref "JP114") (pin "2") (pinfunction "2_2") (pintype "passive"))
      (node (ref "U1") (pin "7") (pinfunction "7_7") (pintype "bidirectional"))
    )
    (net (code "93") (name "Net-(JP114-Pad3)") (class "Default")
      (node (ref "JP114") (pin "3") (pinfunction "3_3") (pintype "passive"))
      (node (ref "U1") (pin "6") (pinfunction "6_6") (pintype "bidirectional"))
    )
    (net (code "94") (name "Net-(JP114-Pad4)") (class "Default")
      (node (ref "JP114") (pin "4") (pinfunction "4_4") (pintype "passive"))
      (node (ref "U1") (pin "5") (pinfunction "5_5") (pintype "bidirectional"))
    )
    (net (code "95") (name "Net-(JP115-Pad1)") (class "Default")
      (node (ref "JP115") (pin "1") (pinfunction "1_1") (pintype "passive"))
      (node (ref "U4") (pin "8") (pinfunction "8_8") (pintype "bidirectional"))
    )
    (net (code "96") (name "Net-(JP115-Pad2)") (class "Default")
      (node (ref "JP115") (pin "2") (pinfunction "2_2") (pintype "passive"))
      (node (ref "U4") (pin "7") (pinfunction "7_7") (pintype "bidirectional"))
    )
    (net (code "97") (name "Net-(JP115-Pad3)") (class "Default")
      (node (ref "JP115") (pin "3") (pinfunction "3_3") (pintype "passive"))
      (node (ref "U4") (pin "6") (pinfunction "6_6") (pintype "bidirectional"))
    )
    (net (code "98") (name "Net-(JP115-Pad4)") (class "Default")
      (node (ref "JP115") (pin "4") (pinfunction "4_4") (pintype "passive"))
      (node (ref "U4") (pin "5") (pinfunction "5_5") (pintype "bidirectional"))
    )
    (net (code "99") (name "Net-(JP118-Pad1)") (class "Default")
      (node (ref "JP118") (pin "1") (pinfunction "1_1") (pintype "passive"))
      (node (ref "U4") (pin "4") (pinfunction "4_4") (pintype "bidirectional"))
    )
    (net (code "100") (name "Net-(JP118-Pad2)") (class "Default")
      (node (ref "JP118") (pin "2") (pinfunction "2_2") (pintype "passive"))
      (node (ref "U4") (pin "3") (pinfunction "3_3") (pintype "bidirectional"))
    )
    (net (code "101") (name "Net-(JP118-Pad3)") (class "Default")
      (node (ref "JP118") (pin "3") (pinfunction "3_3") (pintype "passive"))
      (node (ref "U4") (pin "2") (pinfunction "2_2") (pintype "bidirectional"))
    )
    (net (code "102") (name "Net-(JP118-Pad4)") (class "Default")
      (node (ref "JP118") (pin "4") (pinfunction "4_4") (pintype "passive"))
      (node (ref "U4") (pin "1") (pinfunction "1_1") (pintype "bidirectional"))
    )
    (net (code "103") (name "Net-(MS2-~{RESET}-Pad#1)") (class "Default")
      (node (ref "MS2") (pin "#1") (pinfunction "~{RESET}_#1") (pintype "input"))
      (node (ref "MS2") (pin "1") (pinfunction "~{RESET}_1") (pintype "input"))
      (node (ref "MS2") (pin "@1") (pinfunction "~{RESET}_@1") (pintype "input"))
    )
    (net (code "104") (name "Net-(Q1-D)") (class "Default")
      (node (ref "JP116") (pin "2") (pinfunction "2_2") (pintype "passive"))
      (node (ref "Q1") (pin "3") (pinfunction "D_3") (pintype "passive"))
    )
    (net (code "105") (name "Net-(Q1-G)") (class "Default")
      (node (ref "JP116") (pin "1") (pinfunction "1_1") (pintype "passive"))
      (node (ref "Q1") (pin "1") (pinfunction "G_1") (pintype "passive"))
    )
    (net (code "106") (name "Net-(Q1-S)") (class "Default")
      (node (ref "JP116") (pin "3") (pinfunction "3_3") (pintype "passive"))
      (node (ref "Q1") (pin "2") (pinfunction "S_2") (pintype "passive"))
    )
    (net (code "107") (name "Net-(Q2-D)") (class "Default")
      (node (ref "JP111") (pin "2") (pinfunction "2_2") (pintype "passive"))
      (node (ref "Q2") (pin "3") (pinfunction "D_3") (pintype "passive"))
    )
    (net (code "108") (name "Net-(Q2-G)") (class "Default")
      (node (ref "JP111") (pin "1") (pinfunction "1_1") (pintype "passive"))
      (node (ref "Q2") (pin "1") (pinfunction "G_1") (pintype "passive"))
    )
    (net (code "109") (name "Net-(Q2-S)") (class "Default")
      (node (ref "JP111") (pin "3") (pinfunction "3_3") (pintype "passive"))
      (node (ref "Q2") (pin "2") (pinfunction "S_2") (pintype "passive"))
    )
    (net (code "110") (name "Net-(Q3-D)") (class "Default")
      (node (ref "JP117") (pin "2") (pinfunction "2_2") (pintype "passive"))
      (node (ref "Q3") (pin "3") (pinfunction "D_3") (pintype "passive"))
    )
    (net (code "111") (name "Net-(Q3-G)") (class "Default")
      (node (ref "JP117") (pin "1") (pinfunction "1_1") (pintype "passive"))
      (node (ref "Q3") (pin "1") (pinfunction "G_1") (pintype "passive"))
    )
    (net (code "112") (name "Net-(Q3-S)") (class "Default")
      (node (ref "JP117") (pin "3") (pinfunction "3_3") (pintype "passive"))
      (node (ref "Q3") (pin "2") (pinfunction "S_2") (pintype "passive"))
    )
    (net (code "113") (name "Net-(Q4-D)") (class "Default")
      (node (ref "JP112") (pin "2") (pinfunction "2_2") (pintype "passive"))
      (node (ref "Q4") (pin "3") (pinfunction "D_3") (pintype "passive"))
    )
    (net (code "114") (name "Net-(Q4-G)") (class "Default")
      (node (ref "JP112") (pin "1") (pinfunction "1_1") (pintype "passive"))
      (node (ref "Q4") (pin "1") (pinfunction "G_1") (pintype "passive"))
    )
    (net (code "115") (name "Net-(Q4-S)") (class "Default")
      (node (ref "JP112") (pin "3") (pinfunction "3_3") (pintype "passive"))
      (node (ref "Q4") (pin "2") (pinfunction "S_2") (pintype "passive"))
    )
    (net (code "116") (name "Net-(R10-Pad2)") (class "Default")
      (node (ref "R10") (pin "2") (pinfunction "2_2") (pintype "passive"))
      (node (ref "R11") (pin "1") (pinfunction "1_1") (pintype "passive"))
    )
    (net (code "117") (name "Net-(R12-Pad2)") (class "Default")
      (node (ref "R12") (pin "2") (pinfunction "2_2") (pintype "passive"))
      (node (ref "R13") (pin "1") (pinfunction "1_1") (pintype "passive"))
    )
    (net (code "118") (name "Net-(R14-Pad2)") (class "Default")
      (node (ref "R14") (pin "2") (pinfunction "2_2") (pintype "passive"))
      (node (ref "R15") (pin "1") (pinfunction "1_1") (pintype "passive"))
    )
    (net (code "119") (name "Net-(R16-Pad2)") (class "Default")
      (node (ref "R16") (pin "2") (pinfunction "2_2") (pintype "passive"))
      (node (ref "R17") (pin "1") (pinfunction "1_1") (pintype "passive"))
    )
    (net (code "120") (name "Net-(R18-Pad2)") (class "Default")
      (node (ref "R18") (pin "2") (pinfunction "2_2") (pintype "passive"))
      (node (ref "R19") (pin "1") (pinfunction "1_1") (pintype "passive"))
    )
    (net (code "121") (name "Net-(R20-Pad2)") (class "Default")
      (node (ref "R20") (pin "2") (pinfunction "2_2") (pintype "passive"))
      (node (ref "R21") (pin "1") (pinfunction "1_1") (pintype "passive"))
    )
    (net (code "122") (name "Net-(R22-Pad2)") (class "Default")
      (node (ref "R22") (pin "2") (pinfunction "2_2") (pintype "passive"))
      (node (ref "R23") (pin "1") (pinfunction "1_1") (pintype "passive"))
    )
    (net (code "123") (name "Net-(R24-Pad2)") (class "Default")
      (node (ref "R24") (pin "2") (pinfunction "2_2") (pintype "passive"))
      (node (ref "R25") (pin "2") (pinfunction "2_2") (pintype "passive"))
    )
    (net (code "124") (name "Net-(R26-Pad2)") (class "Default")
      (node (ref "R26") (pin "2") (pinfunction "2_2") (pintype "passive"))
      (node (ref "R27") (pin "2") (pinfunction "2_2") (pintype "passive"))
    )
    (net (code "125") (name "RX") (class "Default")
      (node (ref "JP28") (pin "1") (pinfunction "1_1") (pintype "passive"))
      (node (ref "JP28") (pin "2") (pinfunction "2_2") (pintype "passive"))
      (node (ref "JP28") (pin "3") (pinfunction "3_3") (pintype "passive"))
      (node (ref "JP28") (pin "4") (pinfunction "4_4") (pintype "passive"))
      (node (ref "JP28") (pin "5") (pinfunction "5_5") (pintype "passive"))
      (node (ref "JP28") (pin "6") (pinfunction "6_6") (pintype "passive"))
      (node (ref "JP28") (pin "7") (pinfunction "7_7") (pintype "passive"))
      (node (ref "MS2") (pin "#14") (pinfunction "GPIORX_#14") (pintype "bidirectional"))
      (node (ref "MS2") (pin "14") (pinfunction "GPIORX_14") (pintype "bidirectional"))
      (node (ref "MS2") (pin "@14") (pinfunction "GPIORX_@14") (pintype "bidirectional"))
    )
    (net (code "126") (name "SCK") (class "Default")
      (node (ref "JP102") (pin "1") (pinfunction "1_1") (pintype "passive"))
      (node (ref "JP102") (pin "2") (pinfunction "2_2") (pintype "passive"))
      (node (ref "JP102") (pin "3") (pinfunction "3_3") (pintype "passive"))
      (node (ref "JP102") (pin "4") (pinfunction "4_4") (pintype "passive"))
      (node (ref "JP102") (pin "5") (pinfunction "5_5") (pintype "passive"))
      (node (ref "JP102") (pin "6") (pinfunction "6_6") (pintype "passive"))
      (node (ref "JP102") (pin "7") (pinfunction "7_7") (pintype "passive"))
      (node (ref "JP102") (pin "8") (pinfunction "8_8") (pintype "passive"))
      (node (ref "MS2") (pin "#11") (pinfunction "GPIOSCK_#11") (pintype "bidirectional"))
      (node (ref "MS2") (pin "11") (pinfunction "GPIOSCK_11") (pintype "bidirectional"))
      (node (ref "MS2") (pin "@11") (pinfunction "GPIOSCK_@11") (pintype "bidirectional"))
    )
    (net (code "127") (name "SCL") (class "Default")
      (node (ref "JP23") (pin "1") (pinfunction "1_1") (pintype "passive"))
      (node (ref "JP23") (pin "2") (pinfunction "2_2") (pintype "passive"))
      (node (ref "JP23") (pin "3") (pinfunction "3_3") (pintype "passive"))
      (node (ref "JP23") (pin "4") (pinfunction "4_4") (pintype "passive"))
      (node (ref "JP23") (pin "5") (pinfunction "5_5") (pintype "passive"))
      (node (ref "JP23") (pin "6") (pinfunction "6_6") (pintype "passive"))
      (node (ref "JP23") (pin "7") (pinfunction "7_7") (pintype "passive"))
      (node (ref "MS2") (pin "#18") (pinfunction "GPIOSCL_#18") (pintype "bidirectional"))
      (node (ref "MS2") (pin "18") (pinfunction "GPIOSCL_18") (pintype "bidirectional"))
      (node (ref "MS2") (pin "@!8") (pinfunction "GPIOSCL_@!8") (pintype "bidirectional"))
      (node (ref "R24") (pin "1") (pinfunction "1_1") (pintype "passive"))
      (node (ref "R62") (pin "1") (pinfunction "1_1") (pintype "passive"))
    )
    (net (code "128") (name "SDA") (class "Default")
      (node (ref "JP1") (pin "1") (pinfunction "1_1") (pintype "passive"))
      (node (ref "JP1") (pin "2") (pinfunction "2_2") (pintype "passive"))
      (node (ref "JP1") (pin "3") (pinfunction "3_3") (pintype "passive"))
      (node (ref "JP1") (pin "4") (pinfunction "4_4") (pintype "passive"))
      (node (ref "JP1") (pin "5") (pinfunction "5_5") (pintype "passive"))
      (node (ref "JP1") (pin "6") (pinfunction "6_6") (pintype "passive"))
      (node (ref "JP1") (pin "7") (pinfunction "7_7") (pintype "passive"))
      (node (ref "MS2") (pin "#17") (pinfunction "GPIOSDA_#17") (pintype "bidirectional"))
      (node (ref "MS2") (pin "17") (pinfunction "GPIOSDA_17") (pintype "bidirectional"))
      (node (ref "MS2") (pin "@17") (pinfunction "GPIOSDA_@17") (pintype "bidirectional"))
      (node (ref "R26") (pin "1") (pinfunction "1_1") (pintype "passive"))
      (node (ref "R63") (pin "1") (pinfunction "1_1") (pintype "passive"))
    )
    (net (code "129") (name "TX") (class "Default")
      (node (ref "JP27") (pin "1") (pinfunction "1_1") (pintype "passive"))
      (node (ref "JP27") (pin "2") (pinfunction "2_2") (pintype "passive"))
      (node (ref "JP27") (pin "3") (pinfunction "3_3") (pintype "passive"))
      (node (ref "JP27") (pin "4") (pinfunction "4_4") (pintype "passive"))
      (node (ref "JP27") (pin "5") (pinfunction "5_5") (pintype "passive"))
      (node (ref "JP27") (pin "6") (pinfunction "6_6") (pintype "passive"))
      (node (ref "JP27") (pin "7") (pinfunction "7_7") (pintype "passive"))
      (node (ref "MS2") (pin "#15") (pinfunction "GPIOTX_#15") (pintype "bidirectional"))
      (node (ref "MS2") (pin "15") (pinfunction "GPIOTX_15") (pintype "bidirectional"))
      (node (ref "MS2") (pin "@15") (pinfunction "GPIOTX_@15") (pintype "bidirectional"))
    )
    (net (code "130") (name "USB") (class "Default")
      (node (ref "D2") (pin "C") (pinfunction "C_C") (pintype "passive"))
      (node (ref "JP24") (pin "1") (pinfunction "1_1") (pintype "passive"))
      (node (ref "JP24") (pin "2") (pinfunction "2_2") (pintype "passive"))
      (node (ref "JP24") (pin "3") (pinfunction "3_3") (pintype "passive"))
      (node (ref "JP24") (pin "4") (pinfunction "4_4") (pintype "passive"))
      (node (ref "JP24") (pin "5") (pinfunction "5_5") (pintype "passive"))
      (node (ref "JP24") (pin "6") (pinfunction "6_6") (pintype "passive"))
      (node (ref "JP24") (pin "7") (pinfunction "7_7") (pintype "passive"))
      (node (ref "MS2") (pin "#26") (pinfunction "USB_#26") (pintype "power_in"))
      (node (ref "MS2") (pin "26") (pinfunction "USB_26") (pintype "power_in"))
      (node (ref "MS2") (pin "@26") (pinfunction "USB_@26") (pintype "power_in"))
    )
    (net (code "131") (name "VBAT") (class "Default")
      (node (ref "JP25") (pin "1") (pinfunction "1_1") (pintype "passive"))
      (node (ref "JP25") (pin "2") (pinfunction "2_2") (pintype "passive"))
      (node (ref "JP25") (pin "3") (pinfunction "3_3") (pintype "passive"))
      (node (ref "JP25") (pin "4") (pinfunction "4_4") (pintype "passive"))
      (node (ref "JP25") (pin "5") (pinfunction "5_5") (pintype "passive"))
      (node (ref "JP25") (pin "6") (pinfunction "6_6") (pintype "passive"))
      (node (ref "JP25") (pin "7") (pinfunction "7_7") (pintype "passive"))
      (node (ref "MS2") (pin "#28") (pinfunction "VBAT_#28") (pintype "power_in"))
      (node (ref "MS2") (pin "28") (pinfunction "VBAT_28") (pintype "power_in"))
      (node (ref "MS2") (pin "@28") (pinfunction "VBAT_@28") (pintype "power_in"))
    )
    (net (code "132") (name "VIN") (class "Default")
      (node (ref "C2") (pin "1") (pinfunction "1_1") (pintype "passive"))
      (node (ref "D2") (pin "A") (pinfunction "A_A") (pintype "passive"))
      (node (ref "IC1") (pin "OUT") (pinfunction "OUT_OUT") (pintype "passive"))
      (node (ref "JP3") (pin "1") (pinfunction "1_1") (pintype "passive"))
      (node (ref "JP3") (pin "2") (pinfunction "2_2") (pintype "passive"))
      (node (ref "JP3") (pin "3") (pinfunction "3_3") (pintype "passive"))
      (node (ref "JP3") (pin "4") (pinfunction "4_4") (pintype "passive"))
    )
    (net (code "133") (name "WAKE") (class "Default")
      (node (ref "JP107") (pin "1") (pinfunction "1_1") (pintype "passive"))
      (node (ref "JP107") (pin "2") (pinfunction "2_2") (pintype "passive"))
      (node (ref "JP107") (pin "3") (pinfunction "3_3") (pintype "passive"))
      (node (ref "JP107") (pin "4") (pinfunction "4_4") (pintype "passive"))
      (node (ref "JP107") (pin "5") (pinfunction "5_5") (pintype "passive"))
      (node (ref "JP107") (pin "6") (pinfunction "6_6") (pintype "passive"))
      (node (ref "JP107") (pin "7") (pinfunction "7_7") (pintype "passive"))
      (node (ref "JP107") (pin "8") (pinfunction "8_8") (pintype "passive"))
      (node (ref "MS2") (pin "#16") (pinfunction "WAKE/NC_#16") (pintype "passive"))
      (node (ref "MS2") (pin "16") (pinfunction "WAKE/NC_16") (pintype "passive"))
      (node (ref "MS2") (pin "@16") (pinfunction "WAKE/NC_@16") (pintype "passive"))
    )
    (net (code "134") (name "unconnected-(JP35-Pad2)") (class "Default")
      (node (ref "JP35") (pin "2") (pinfunction "2_2") (pintype "passive"))
    )
    (net (code "135") (name "unconnected-(JP35-Pad3)") (class "Default")
      (node (ref "JP35") (pin "3") (pinfunction "3_3") (pintype "passive"))
    )
    (net (code "136") (name "unconnected-(JP35-Pad4)") (class "Default")
      (node (ref "JP35") (pin "4") (pinfunction "4_4") (pintype "passive"))
    )
    (net (code "137") (name "unconnected-(JP35-Pad5)") (class "Default")
      (node (ref "JP35") (pin "5") (pinfunction "5_5") (pintype "passive"))
    )
    (net (code "138") (name "unconnected-(JP35-Pad6)") (class "Default")
      (node (ref "JP35") (pin "6") (pinfunction "6_6") (pintype "passive"))
    )
    (net (code "139") (name "unconnected-(JP35-Pad7)") (class "Default")
      (node (ref "JP35") (pin "7") (pinfunction "7_7") (pintype "passive"))
    )
    (net (code "140") (name "unconnected-(JP35-Pad8)") (class "Default")
      (node (ref "JP35") (pin "8") (pinfunction "8_8") (pintype "passive"))
    )
    (net (code "141") (name "unconnected-(JP35-Pad9)") (class "Default")
      (node (ref "JP35") (pin "9") (pinfunction "9_9") (pintype "passive"))
    )
    (net (code "142") (name "unconnected-(JP35-Pad10)") (class "Default")
      (node (ref "JP35") (pin "10") (pinfunction "10_10") (pintype "passive"))
    )
    (net (code "143") (name "unconnected-(JP35-Pad11)") (class "Default")
      (node (ref "JP35") (pin "11") (pinfunction "11_11") (pintype "passive"))
    )
    (net (code "144") (name "unconnected-(JP35-Pad12)") (class "Default")
      (node (ref "JP35") (pin "12") (pinfunction "12_12") (pintype "passive"))
    )
    (net (code "145") (name "unconnected-(JP35-Pad13)") (class "Default")
      (node (ref "JP35") (pin "13") (pinfunction "13_13") (pintype "passive"))
    )
    (net (code "146") (name "unconnected-(JP35-Pad14)") (class "Default")
      (node (ref "JP35") (pin "14") (pinfunction "14_14") (pintype "passive"))
    )
    (net (code "147") (name "unconnected-(JP36-Pad2)") (class "Default")
      (node (ref "JP36") (pin "2") (pinfunction "2_2") (pintype "passive"))
    )
    (net (code "148") (name "unconnected-(JP36-Pad3)") (class "Default")
      (node (ref "JP36") (pin "3") (pinfunction "3_3") (pintype "passive"))
    )
    (net (code "149") (name "unconnected-(JP36-Pad4)") (class "Default")
      (node (ref "JP36") (pin "4") (pinfunction "4_4") (pintype "passive"))
    )
    (net (code "150") (name "unconnected-(JP36-Pad5)") (class "Default")
      (node (ref "JP36") (pin "5") (pinfunction "5_5") (pintype "passive"))
    )
    (net (code "151") (name "unconnected-(JP36-Pad6)") (class "Default")
      (node (ref "JP36") (pin "6") (pinfunction "6_6") (pintype "passive"))
    )
    (net (code "152") (name "unconnected-(JP36-Pad7)") (class "Default")
      (node (ref "JP36") (pin "7") (pinfunction "7_7") (pintype "passive"))
    )
    (net (code "153") (name "unconnected-(JP36-Pad8)") (class "Default")
      (node (ref "JP36") (pin "8") (pinfunction "8_8") (pintype "passive"))
    )
    (net (code "154") (name "unconnected-(JP36-Pad9)") (class "Default")
      (node (ref "JP36") (pin "9") (pinfunction "9_9") (pintype "passive"))
    )
    (net (code "155") (name "unconnected-(JP36-Pad10)") (class "Default")
      (node (ref "JP36") (pin "10") (pinfunction "10_10") (pintype "passive"))
    )
    (net (code "156") (name "unconnected-(JP36-Pad11)") (class "Default")
      (node (ref "JP36") (pin "11") (pinfunction "11_11") (pintype "passive"))
    )
    (net (code "157") (name "unconnected-(JP36-Pad12)") (class "Default")
      (node (ref "JP36") (pin "12") (pinfunction "12_12") (pintype "passive"))
    )
    (net (code "158") (name "unconnected-(JP36-Pad13)") (class "Default")
      (node (ref "JP36") (pin "13") (pinfunction "13_13") (pintype "passive"))
    )
    (net (code "159") (name "unconnected-(JP36-Pad14)") (class "Default")
      (node (ref "JP36") (pin "14") (pinfunction "14_14") (pintype "passive"))
    )
    (net (code "160") (name "unconnected-(JP37-Pad2)") (class "Default")
      (node (ref "JP37") (pin "2") (pinfunction "2_2") (pintype "passive"))
    )
    (net (code "161") (name "unconnected-(JP37-Pad3)") (class "Default")
      (node (ref "JP37") (pin "3") (pinfunction "3_3") (pintype "passive"))
    )
    (net (code "162") (name "unconnected-(JP37-Pad4)") (class "Default")
      (node (ref "JP37") (pin "4") (pinfunction "4_4") (pintype "passive"))
    )
    (net (code "163") (name "unconnected-(JP37-Pad5)") (class "Default")
      (node (ref "JP37") (pin "5") (pinfunction "5_5") (pintype "passive"))
    )
    (net (code "164") (name "unconnected-(JP37-Pad6)") (class "Default")
      (node (ref "JP37") (pin "6") (pinfunction "6_6") (pintype "passive"))
    )
    (net (code "165") (name "unconnected-(JP37-Pad7)") (class "Default")
      (node (ref "JP37") (pin "7") (pinfunction "7_7") (pintype "passive"))
    )
    (net (code "166") (name "unconnected-(JP37-Pad8)") (class "Default")
      (node (ref "JP37") (pin "8") (pinfunction "8_8") (pintype "passive"))
    )
    (net (code "167") (name "unconnected-(JP37-Pad9)") (class "Default")
      (node (ref "JP37") (pin "9") (pinfunction "9_9") (pintype "passive"))
    )
    (net (code "168") (name "unconnected-(JP37-Pad10)") (class "Default")
      (node (ref "JP37") (pin "10") (pinfunction "10_10") (pintype "passive"))
    )
    (net (code "169") (name "unconnected-(JP37-Pad11)") (class "Default")
      (node (ref "JP37") (pin "11") (pinfunction "11_11") (pintype "passive"))
    )
    (net (code "170") (name "unconnected-(JP37-Pad12)") (class "Default")
      (node (ref "JP37") (pin "12") (pinfunction "12_12") (pintype "passive"))
    )
    (net (code "171") (name "unconnected-(JP37-Pad13)") (class "Default")
      (node (ref "JP37") (pin "13") (pinfunction "13_13") (pintype "passive"))
    )
    (net (code "172") (name "unconnected-(JP37-Pad14)") (class "Default")
      (node (ref "JP37") (pin "14") (pinfunction "14_14") (pintype "passive"))
    )
    (net (code "173") (name "unconnected-(JP40-Pad2)") (class "Default")
      (node (ref "JP40") (pin "2") (pinfunction "2_2") (pintype "passive"))
    )
    (net (code "174") (name "unconnected-(JP40-Pad3)") (class "Default")
      (node (ref "JP40") (pin "3") (pinfunction "3_3") (pintype "passive"))
    )
    (net (code "175") (name "unconnected-(JP40-Pad4)") (class "Default")
      (node (ref "JP40") (pin "4") (pinfunction "4_4") (pintype "passive"))
    )
    (net (code "176") (name "unconnected-(JP40-Pad5)") (class "Default")
      (node (ref "JP40") (pin "5") (pinfunction "5_5") (pintype "passive"))
    )
    (net (code "177") (name "unconnected-(JP40-Pad6)") (class "Default")
      (node (ref "JP40") (pin "6") (pinfunction "6_6") (pintype "passive"))
    )
    (net (code "178") (name "unconnected-(JP40-Pad7)") (class "Default")
      (node (ref "JP40") (pin "7") (pinfunction "7_7") (pintype "passive"))
    )
    (net (code "179") (name "unconnected-(JP40-Pad8)") (class "Default")
      (node (ref "JP40") (pin "8") (pinfunction "8_8") (pintype "passive"))
    )
    (net (code "180") (name "unconnected-(JP40-Pad9)") (class "Default")
      (node (ref "JP40") (pin "9") (pinfunction "9_9") (pintype "passive"))
    )
    (net (code "181") (name "unconnected-(JP40-Pad10)") (class "Default")
      (node (ref "JP40") (pin "10") (pinfunction "10_10") (pintype "passive"))
    )
    (net (code "182") (name "unconnected-(JP40-Pad11)") (class "Default")
      (node (ref "JP40") (pin "11") (pinfunction "11_11") (pintype "passive"))
    )
    (net (code "183") (name "unconnected-(JP40-Pad12)") (class "Default")
      (node (ref "JP40") (pin "12") (pinfunction "12_12") (pintype "passive"))
    )
    (net (code "184") (name "unconnected-(JP40-Pad13)") (class "Default")
      (node (ref "JP40") (pin "13") (pinfunction "13_13") (pintype "passive"))
    )
    (net (code "185") (name "unconnected-(JP40-Pad14)") (class "Default")
      (node (ref "JP40") (pin "14") (pinfunction "14_14") (pintype "passive"))
    )
    (net (code "186") (name "unconnected-(JP41-Pad2)") (class "Default")
      (node (ref "JP41") (pin "2") (pinfunction "2_2") (pintype "passive"))
    )
    (net (code "187") (name "unconnected-(JP41-Pad3)") (class "Default")
      (node (ref "JP41") (pin "3") (pinfunction "3_3") (pintype "passive"))
    )
    (net (code "188") (name "unconnected-(JP41-Pad4)") (class "Default")
      (node (ref "JP41") (pin "4") (pinfunction "4_4") (pintype "passive"))
    )
    (net (code "189") (name "unconnected-(JP41-Pad5)") (class "Default")
      (node (ref "JP41") (pin "5") (pinfunction "5_5") (pintype "passive"))
    )
    (net (code "190") (name "unconnected-(JP41-Pad6)") (class "Default")
      (node (ref "JP41") (pin "6") (pinfunction "6_6") (pintype "passive"))
    )
    (net (code "191") (name "unconnected-(JP41-Pad7)") (class "Default")
      (node (ref "JP41") (pin "7") (pinfunction "7_7") (pintype "passive"))
    )
    (net (code "192") (name "unconnected-(JP41-Pad8)") (class "Default")
      (node (ref "JP41") (pin "8") (pinfunction "8_8") (pintype "passive"))
    )
    (net (code "193") (name "unconnected-(JP41-Pad9)") (class "Default")
      (node (ref "JP41") (pin "9") (pinfunction "9_9") (pintype "passive"))
    )
    (net (code "194") (name "unconnected-(JP41-Pad10)") (class "Default")
      (node (ref "JP41") (pin "10") (pinfunction "10_10") (pintype "passive"))
    )
    (net (code "195") (name "unconnected-(JP41-Pad11)") (class "Default")
      (node (ref "JP41") (pin "11") (pinfunction "11_11") (pintype "passive"))
    )
    (net (code "196") (name "unconnected-(JP41-Pad12)") (class "Default")
      (node (ref "JP41") (pin "12") (pinfunction "12_12") (pintype "passive"))
    )
    (net (code "197") (name "unconnected-(JP41-Pad13)") (class "Default")
      (node (ref "JP41") (pin "13") (pinfunction "13_13") (pintype "passive"))
    )
    (net (code "198") (name "unconnected-(JP41-Pad14)") (class "Default")
      (node (ref "JP41") (pin "14") (pinfunction "14_14") (pintype "passive"))
    )
    (net (code "199") (name "unconnected-(JP42-Pad2)") (class "Default")
      (node (ref "JP42") (pin "2") (pinfunction "2_2") (pintype "passive"))
    )
    (net (code "200") (name "unconnected-(JP42-Pad3)") (class "Default")
      (node (ref "JP42") (pin "3") (pinfunction "3_3") (pintype "passive"))
    )
    (net (code "201") (name "unconnected-(JP42-Pad4)") (class "Default")
      (node (ref "JP42") (pin "4") (pinfunction "4_4") (pintype "passive"))
    )
    (net (code "202") (name "unconnected-(JP42-Pad5)") (class "Default")
      (node (ref "JP42") (pin "5") (pinfunction "5_5") (pintype "passive"))
    )
    (net (code "203") (name "unconnected-(JP42-Pad6)") (class "Default")
      (node (ref "JP42") (pin "6") (pinfunction "6_6") (pintype "passive"))
    )
    (net (code "204") (name "unconnected-(JP42-Pad7)") (class "Default")
      (node (ref "JP42") (pin "7") (pinfunction "7_7") (pintype "passive"))
    )
    (net (code "205") (name "unconnected-(JP42-Pad8)") (class "Default")
      (node (ref "JP42") (pin "8") (pinfunction "8_8") (pintype "passive"))
    )
    (net (code "206") (name "unconnected-(JP42-Pad9)") (class "Default")
      (node (ref "JP42") (pin "9") (pinfunction "9_9") (pintype "passive"))
    )
    (net (code "207") (name "unconnected-(JP42-Pad10)") (class "Default")
      (node (ref "JP42") (pin "10") (pinfunction "10_10") (pintype "passive"))
    )
    (net (code "208") (name "unconnected-(JP42-Pad11)") (class "Default")
      (node (ref "JP42") (pin "11") (pinfunction "11_11") (pintype "passive"))
    )
    (net (code "209") (name "unconnected-(JP42-Pad12)") (class "Default")
      (node (ref "JP42") (pin "12") (pinfunction "12_12") (pintype "passive"))
    )
    (net (code "210") (name "unconnected-(JP42-Pad13)") (class "Default")
      (node (ref "JP42") (pin "13") (pinfunction "13_13") (pintype "passive"))
    )
    (net (code "211") (name "unconnected-(JP42-Pad14)") (class "Default")
      (node (ref "JP42") (pin "14") (pinfunction "14_14") (pintype "passive"))
    )
    (net (code "212") (name "unconnected-(JP43-Pad2)") (class "Default")
      (node (ref "JP43") (pin "2") (pinfunction "2_2") (pintype "passive"))
    )
    (net (code "213") (name "unconnected-(JP43-Pad3)") (class "Default")
      (node (ref "JP43") (pin "3") (pinfunction "3_3") (pintype "passive"))
    )
    (net (code "214") (name "unconnected-(JP43-Pad4)") (class "Default")
      (node (ref "JP43") (pin "4") (pinfunction "4_4") (pintype "passive"))
    )
    (net (code "215") (name "unconnected-(JP43-Pad5)") (class "Default")
      (node (ref "JP43") (pin "5") (pinfunction "5_5") (pintype "passive"))
    )
    (net (code "216") (name "unconnected-(JP43-Pad6)") (class "Default")
      (node (ref "JP43") (pin "6") (pinfunction "6_6") (pintype "passive"))
    )
    (net (code "217") (name "unconnected-(JP43-Pad7)") (class "Default")
      (node (ref "JP43") (pin "7") (pinfunction "7_7") (pintype "passive"))
    )
    (net (code "218") (name "unconnected-(JP43-Pad8)") (class "Default")
      (node (ref "JP43") (pin "8") (pinfunction "8_8") (pintype "passive"))
    )
    (net (code "219") (name "unconnected-(JP43-Pad9)") (class "Default")
      (node (ref "JP43") (pin "9") (pinfunction "9_9") (pintype "passive"))
    )
    (net (code "220") (name "unconnected-(JP43-Pad10)") (class "Default")
      (node (ref "JP43") (pin "10") (pinfunction "10_10") (pintype "passive"))
    )
    (net (code "221") (name "unconnected-(JP43-Pad11)") (class "Default")
      (node (ref "JP43") (pin "11") (pinfunction "11_11") (pintype "passive"))
    )
    (net (code "222") (name "unconnected-(JP43-Pad12)") (class "Default")
      (node (ref "JP43") (pin "12") (pinfunction "12_12") (pintype "passive"))
    )
    (net (code "223") (name "unconnected-(JP43-Pad13)") (class "Default")
      (node (ref "JP43") (pin "13") (pinfunction "13_13") (pintype "passive"))
    )
    (net (code "224") (name "unconnected-(JP43-Pad14)") (class "Default")
      (node (ref "JP43") (pin "14") (pinfunction "14_14") (pintype "passive"))
    )
    (net (code "225") (name "unconnected-(JP44-Pad2)") (class "Default")
      (node (ref "JP44") (pin "2") (pinfunction "2_2") (pintype "passive"))
    )
    (net (code "226") (name "unconnected-(JP44-Pad3)") (class "Default")
      (node (ref "JP44") (pin "3") (pinfunction "3_3") (pintype "passive"))
    )
    (net (code "227") (name "unconnected-(JP44-Pad4)") (class "Default")
      (node (ref "JP44") (pin "4") (pinfunction "4_4") (pintype "passive"))
    )
    (net (code "228") (name "unconnected-(JP44-Pad5)") (class "Default")
      (node (ref "JP44") (pin "5") (pinfunction "5_5") (pintype "passive"))
    )
    (net (code "229") (name "unconnected-(JP44-Pad6)") (class "Default")
      (node (ref "JP44") (pin "6") (pinfunction "6_6") (pintype "passive"))
    )
    (net (code "230") (name "unconnected-(JP44-Pad7)") (class "Default")
      (node (ref "JP44") (pin "7") (pinfunction "7_7") (pintype "passive"))
    )
    (net (code "231") (name "unconnected-(JP44-Pad8)") (class "Default")
      (node (ref "JP44") (pin "8") (pinfunction "8_8") (pintype "passive"))
    )
    (net (code "232") (name "unconnected-(JP44-Pad9)") (class "Default")
      (node (ref "JP44") (pin "9") (pinfunction "9_9") (pintype "passive"))
    )
    (net (code "233") (name "unconnected-(JP44-Pad10)") (class "Default")
      (node (ref "JP44") (pin "10") (pinfunction "10_10") (pintype "passive"))
    )
    (net (code "234") (name "unconnected-(JP44-Pad11)") (class "Default")
      (node (ref "JP44") (pin "11") (pinfunction "11_11") (pintype "passive"))
    )
    (net (code "235") (name "unconnected-(JP44-Pad12)") (class "Default")
      (node (ref "JP44") (pin "12") (pinfunction "12_12") (pintype "passive"))
    )
    (net (code "236") (name "unconnected-(JP44-Pad13)") (class "Default")
      (node (ref "JP44") (pin "13") (pinfunction "13_13") (pintype "passive"))
    )
    (net (code "237") (name "unconnected-(JP44-Pad14)") (class "Default")
      (node (ref "JP44") (pin "14") (pinfunction "14_14") (pintype "passive"))
    )
    (net (code "238") (name "unconnected-(JP45-Pad2)") (class "Default")
      (node (ref "JP45") (pin "2") (pinfunction "2_2") (pintype "passive"))
    )
    (net (code "239") (name "unconnected-(JP45-Pad3)") (class "Default")
      (node (ref "JP45") (pin "3") (pinfunction "3_3") (pintype "passive"))
    )
    (net (code "240") (name "unconnected-(JP45-Pad4)") (class "Default")
      (node (ref "JP45") (pin "4") (pinfunction "4_4") (pintype "passive"))
    )
    (net (code "241") (name "unconnected-(JP45-Pad5)") (class "Default")
      (node (ref "JP45") (pin "5") (pinfunction "5_5") (pintype "passive"))
    )
    (net (code "242") (name "unconnected-(JP45-Pad6)") (class "Default")
      (node (ref "JP45") (pin "6") (pinfunction "6_6") (pintype "passive"))
    )
    (net (code "243") (name "unconnected-(JP45-Pad7)") (class "Default")
      (node (ref "JP45") (pin "7") (pinfunction "7_7") (pintype "passive"))
    )
    (net (code "244") (name "unconnected-(JP45-Pad8)") (class "Default")
      (node (ref "JP45") (pin "8") (pinfunction "8_8") (pintype "passive"))
    )
    (net (code "245") (name "unconnected-(JP45-Pad9)") (class "Default")
      (node (ref "JP45") (pin "9") (pinfunction "9_9") (pintype "passive"))
    )
    (net (code "246") (name "unconnected-(JP45-Pad10)") (class "Default")
      (node (ref "JP45") (pin "10") (pinfunction "10_10") (pintype "passive"))
    )
    (net (code "247") (name "unconnected-(JP45-Pad11)") (class "Default")
      (node (ref "JP45") (pin "11") (pinfunction "11_11") (pintype "passive"))
    )
    (net (code "248") (name "unconnected-(JP45-Pad12)") (class "Default")
      (node (ref "JP45") (pin "12") (pinfunction "12_12") (pintype "passive"))
    )
    (net (code "249") (name "unconnected-(JP45-Pad13)") (class "Default")
      (node (ref "JP45") (pin "13") (pinfunction "13_13") (pintype "passive"))
    )
    (net (code "250") (name "unconnected-(JP45-Pad14)") (class "Default")
      (node (ref "JP45") (pin "14") (pinfunction "14_14") (pintype "passive"))
    )
    (net (code "251") (name "unconnected-(JP46-Pad2)") (class "Default")
      (node (ref "JP46") (pin "2") (pinfunction "2_2") (pintype "passive"))
    )
    (net (code "252") (name "unconnected-(JP46-Pad3)") (class "Default")
      (node (ref "JP46") (pin "3") (pinfunction "3_3") (pintype "passive"))
    )
    (net (code "253") (name "unconnected-(JP46-Pad4)") (class "Default")
      (node (ref "JP46") (pin "4") (pinfunction "4_4") (pintype "passive"))
    )
    (net (code "254") (name "unconnected-(JP46-Pad5)") (class "Default")
      (node (ref "JP46") (pin "5") (pinfunction "5_5") (pintype "passive"))
    )
    (net (code "255") (name "unconnected-(JP46-Pad6)") (class "Default")
      (node (ref "JP46") (pin "6") (pinfunction "6_6") (pintype "passive"))
    )
    (net (code "256") (name "unconnected-(JP46-Pad7)") (class "Default")
      (node (ref "JP46") (pin "7") (pinfunction "7_7") (pintype "passive"))
    )
    (net (code "257") (name "unconnected-(JP46-Pad8)") (class "Default")
      (node (ref "JP46") (pin "8") (pinfunction "8_8") (pintype "passive"))
    )
    (net (code "258") (name "unconnected-(JP46-Pad9)") (class "Default")
      (node (ref "JP46") (pin "9") (pinfunction "9_9") (pintype "passive"))
    )
    (net (code "259") (name "unconnected-(JP46-Pad10)") (class "Default")
      (node (ref "JP46") (pin "10") (pinfunction "10_10") (pintype "passive"))
    )
    (net (code "260") (name "unconnected-(JP46-Pad11)") (class "Default")
      (node (ref "JP46") (pin "11") (pinfunction "11_11") (pintype "passive"))
    )
    (net (code "261") (name "unconnected-(JP46-Pad12)") (class "Default")
      (node (ref "JP46") (pin "12") (pinfunction "12_12") (pintype "passive"))
    )
    (net (code "262") (name "unconnected-(JP46-Pad13)") (class "Default")
      (node (ref "JP46") (pin "13") (pinfunction "13_13") (pintype "passive"))
    )
    (net (code "263") (name "unconnected-(JP46-Pad14)") (class "Default")
      (node (ref "JP46") (pin "14") (pinfunction "14_14") (pintype "passive"))
    )
    (net (code "264") (name "unconnected-(JP47-Pad2)") (class "Default")
      (node (ref "JP47") (pin "2") (pinfunction "2_2") (pintype "passive"))
    )
    (net (code "265") (name "unconnected-(JP47-Pad3)") (class "Default")
      (node (ref "JP47") (pin "3") (pinfunction "3_3") (pintype "passive"))
    )
    (net (code "266") (name "unconnected-(JP47-Pad4)") (class "Default")
      (node (ref "JP47") (pin "4") (pinfunction "4_4") (pintype "passive"))
    )
    (net (code "267") (name "unconnected-(JP47-Pad5)") (class "Default")
      (node (ref "JP47") (pin "5") (pinfunction "5_5") (pintype "passive"))
    )
    (net (code "268") (name "unconnected-(JP47-Pad6)") (class "Default")
      (node (ref "JP47") (pin "6") (pinfunction "6_6") (pintype "passive"))
    )
    (net (code "269") (name "unconnected-(JP47-Pad7)") (class "Default")
      (node (ref "JP47") (pin "7") (pinfunction "7_7") (pintype "passive"))
    )
    (net (code "270") (name "unconnected-(JP47-Pad8)") (class "Default")
      (node (ref "JP47") (pin "8") (pinfunction "8_8") (pintype "passive"))
    )
    (net (code "271") (name "unconnected-(JP47-Pad9)") (class "Default")
      (node (ref "JP47") (pin "9") (pinfunction "9_9") (pintype "passive"))
    )
    (net (code "272") (name "unconnected-(JP47-Pad10)") (class "Default")
      (node (ref "JP47") (pin "10") (pinfunction "10_10") (pintype "passive"))
    )
    (net (code "273") (name "unconnected-(JP47-Pad11)") (class "Default")
      (node (ref "JP47") (pin "11") (pinfunction "11_11") (pintype "passive"))
    )
    (net (code "274") (name "unconnected-(JP47-Pad12)") (class "Default")
      (node (ref "JP47") (pin "12") (pinfunction "12_12") (pintype "passive"))
    )
    (net (code "275") (name "unconnected-(JP47-Pad13)") (class "Default")
      (node (ref "JP47") (pin "13") (pinfunction "13_13") (pintype "passive"))
    )
    (net (code "276") (name "unconnected-(JP47-Pad14)") (class "Default")
      (node (ref "JP47") (pin "14") (pinfunction "14_14") (pintype "passive"))
    )
    (net (code "277") (name "unconnected-(JP48-Pad2)") (class "Default")
      (node (ref "JP48") (pin "2") (pinfunction "2_2") (pintype "passive"))
    )
    (net (code "278") (name "unconnected-(JP48-Pad3)") (class "Default")
      (node (ref "JP48") (pin "3") (pinfunction "3_3") (pintype "passive"))
    )
    (net (code "279") (name "unconnected-(JP48-Pad4)") (class "Default")
      (node (ref "JP48") (pin "4") (pinfunction "4_4") (pintype "passive"))
    )
    (net (code "280") (name "unconnected-(JP48-Pad5)") (class "Default")
      (node (ref "JP48") (pin "5") (pinfunction "5_5") (pintype "passive"))
    )
    (net (code "281") (name "unconnected-(JP48-Pad6)") (class "Default")
      (node (ref "JP48") (pin "6") (pinfunction "6_6") (pintype "passive"))
    )
    (net (code "282") (name "unconnected-(JP48-Pad7)") (class "Default")
      (node (ref "JP48") (pin "7") (pinfunction "7_7") (pintype "passive"))
    )
    (net (code "283") (name "unconnected-(JP48-Pad8)") (class "Default")
      (node (ref "JP48") (pin "8") (pinfunction "8_8") (pintype "passive"))
    )
    (net (code "284") (name "unconnected-(JP48-Pad9)") (class "Default")
      (node (ref "JP48") (pin "9") (pinfunction "9_9") (pintype "passive"))
    )
    (net (code "285") (name "unconnected-(JP48-Pad10)") (class "Default")
      (node (ref "JP48") (pin "10") (pinfunction "10_10") (pintype "passive"))
    )
    (net (code "286") (name "unconnected-(JP48-Pad11)") (class "Default")
      (node (ref "JP48") (pin "11") (pinfunction "11_11") (pintype "passive"))
    )
    (net (code "287") (name "unconnected-(JP48-Pad12)") (class "Default")
      (node (ref "JP48") (pin "12") (pinfunction "12_12") (pintype "passive"))
    )
    (net (code "288") (name "unconnected-(JP48-Pad13)") (class "Default")
      (node (ref "JP48") (pin "13") (pinfunction "13_13") (pintype "passive"))
    )
    (net (code "289") (name "unconnected-(JP48-Pad14)") (class "Default")
      (node (ref "JP48") (pin "14") (pinfunction "14_14") (pintype "passive"))
    )
    (net (code "290") (name "unconnected-(JP49-Pad2)") (class "Default")
      (node (ref "JP49") (pin "2") (pinfunction "2_2") (pintype "passive"))
    )
    (net (code "291") (name "unconnected-(JP49-Pad3)") (class "Default")
      (node (ref "JP49") (pin "3") (pinfunction "3_3") (pintype "passive"))
    )
    (net (code "292") (name "unconnected-(JP49-Pad4)") (class "Default")
      (node (ref "JP49") (pin "4") (pinfunction "4_4") (pintype "passive"))
    )
    (net (code "293") (name "unconnected-(JP49-Pad5)") (class "Default")
      (node (ref "JP49") (pin "5") (pinfunction "5_5") (pintype "passive"))
    )
    (net (code "294") (name "unconnected-(JP49-Pad6)") (class "Default")
      (node (ref "JP49") (pin "6") (pinfunction "6_6") (pintype "passive"))
    )
    (net (code "295") (name "unconnected-(JP49-Pad7)") (class "Default")
      (node (ref "JP49") (pin "7") (pinfunction "7_7") (pintype "passive"))
    )
    (net (code "296") (name "unconnected-(JP49-Pad8)") (class "Default")
      (node (ref "JP49") (pin "8") (pinfunction "8_8") (pintype "passive"))
    )
    (net (code "297") (name "unconnected-(JP49-Pad9)") (class "Default")
      (node (ref "JP49") (pin "9") (pinfunction "9_9") (pintype "passive"))
    )
    (net (code "298") (name "unconnected-(JP49-Pad10)") (class "Default")
      (node (ref "JP49") (pin "10") (pinfunction "10_10") (pintype "passive"))
    )
    (net (code "299") (name "unconnected-(JP49-Pad11)") (class "Default")
      (node (ref "JP49") (pin "11") (pinfunction "11_11") (pintype "passive"))
    )
    (net (code "300") (name "unconnected-(JP49-Pad12)") (class "Default")
      (node (ref "JP49") (pin "12") (pinfunction "12_12") (pintype "passive"))
    )
    (net (code "301") (name "unconnected-(JP49-Pad13)") (class "Default")
      (node (ref "JP49") (pin "13") (pinfunction "13_13") (pintype "passive"))
    )
    (net (code "302") (name "unconnected-(JP49-Pad14)") (class "Default")
      (node (ref "JP49") (pin "14") (pinfunction "14_14") (pintype "passive"))
    )
    (net (code "303") (name "unconnected-(JP50-Pad2)") (class "Default")
      (node (ref "JP50") (pin "2") (pinfunction "2_2") (pintype "passive"))
    )
    (net (code "304") (name "unconnected-(JP50-Pad3)") (class "Default")
      (node (ref "JP50") (pin "3") (pinfunction "3_3") (pintype "passive"))
    )
    (net (code "305") (name "unconnected-(JP50-Pad4)") (class "Default")
      (node (ref "JP50") (pin "4") (pinfunction "4_4") (pintype "passive"))
    )
    (net (code "306") (name "unconnected-(JP50-Pad5)") (class "Default")
      (node (ref "JP50") (pin "5") (pinfunction "5_5") (pintype "passive"))
    )
    (net (code "307") (name "unconnected-(JP50-Pad6)") (class "Default")
      (node (ref "JP50") (pin "6") (pinfunction "6_6") (pintype "passive"))
    )
    (net (code "308") (name "unconnected-(JP50-Pad7)") (class "Default")
      (node (ref "JP50") (pin "7") (pinfunction "7_7") (pintype "passive"))
    )
    (net (code "309") (name "unconnected-(JP50-Pad8)") (class "Default")
      (node (ref "JP50") (pin "8") (pinfunction "8_8") (pintype "passive"))
    )
    (net (code "310") (name "unconnected-(JP50-Pad9)") (class "Default")
      (node (ref "JP50") (pin "9") (pinfunction "9_9") (pintype "passive"))
    )
    (net (code "311") (name "unconnected-(JP50-Pad10)") (class "Default")
      (node (ref "JP50") (pin "10") (pinfunction "10_10") (pintype "passive"))
    )
    (net (code "312") (name "unconnected-(JP50-Pad11)") (class "Default")
      (node (ref "JP50") (pin "11") (pinfunction "11_11") (pintype "passive"))
    )
    (net (code "313") (name "unconnected-(JP50-Pad12)") (class "Default")
      (node (ref "JP50") (pin "12") (pinfunction "12_12") (pintype "passive"))
    )
    (net (code "314") (name "unconnected-(JP50-Pad13)") (class "Default")
      (node (ref "JP50") (pin "13") (pinfunction "13_13") (pintype "passive"))
    )
    (net (code "315") (name "unconnected-(JP50-Pad14)") (class "Default")
      (node (ref "JP50") (pin "14") (pinfunction "14_14") (pintype "passive"))
    )
    (net (code "316") (name "unconnected-(JP51-Pad2)") (class "Default")
      (node (ref "JP51") (pin "2") (pinfunction "2_2") (pintype "passive"))
    )
    (net (code "317") (name "unconnected-(JP51-Pad3)") (class "Default")
      (node (ref "JP51") (pin "3") (pinfunction "3_3") (pintype "passive"))
    )
    (net (code "318") (name "unconnected-(JP51-Pad4)") (class "Default")
      (node (ref "JP51") (pin "4") (pinfunction "4_4") (pintype "passive"))
    )
    (net (code "319") (name "unconnected-(JP51-Pad5)") (class "Default")
      (node (ref "JP51") (pin "5") (pinfunction "5_5") (pintype "passive"))
    )
    (net (code "320") (name "unconnected-(JP51-Pad6)") (class "Default")
      (node (ref "JP51") (pin "6") (pinfunction "6_6") (pintype "passive"))
    )
    (net (code "321") (name "unconnected-(JP51-Pad7)") (class "Default")
      (node (ref "JP51") (pin "7") (pinfunction "7_7") (pintype "passive"))
    )
    (net (code "322") (name "unconnected-(JP51-Pad8)") (class "Default")
      (node (ref "JP51") (pin "8") (pinfunction "8_8") (pintype "passive"))
    )
    (net (code "323") (name "unconnected-(JP51-Pad9)") (class "Default")
      (node (ref "JP51") (pin "9") (pinfunction "9_9") (pintype "passive"))
    )
    (net (code "324") (name "unconnected-(JP51-Pad10)") (class "Default")
      (node (ref "JP51") (pin "10") (pinfunction "10_10") (pintype "passive"))
    )
    (net (code "325") (name "unconnected-(JP51-Pad11)") (class "Default")
      (node (ref "JP51") (pin "11") (pinfunction "11_11") (pintype "passive"))
    )
    (net (code "326") (name "unconnected-(JP51-Pad12)") (class "Default")
      (node (ref "JP51") (pin "12") (pinfunction "12_12") (pintype "passive"))
    )
    (net (code "327") (name "unconnected-(JP51-Pad13)") (class "Default")
      (node (ref "JP51") (pin "13") (pinfunction "13_13") (pintype "passive"))
    )
    (net (code "328") (name "unconnected-(JP51-Pad14)") (class "Default")
      (node (ref "JP51") (pin "14") (pinfunction "14_14") (pintype "passive"))
    )
    (net (code "329") (name "unconnected-(JP52-Pad2)") (class "Default")
      (node (ref "JP52") (pin "2") (pinfunction "2_2") (pintype "passive"))
    )
    (net (code "330") (name "unconnected-(JP52-Pad3)") (class "Default")
      (node (ref "JP52") (pin "3") (pinfunction "3_3") (pintype "passive"))
    )
    (net (code "331") (name "unconnected-(JP52-Pad4)") (class "Default")
      (node (ref "JP52") (pin "4") (pinfunction "4_4") (pintype "passive"))
    )
    (net (code "332") (name "unconnected-(JP52-Pad5)") (class "Default")
      (node (ref "JP52") (pin "5") (pinfunction "5_5") (pintype "passive"))
    )
    (net (code "333") (name "unconnected-(JP52-Pad6)") (class "Default")
      (node (ref "JP52") (pin "6") (pinfunction "6_6") (pintype "passive"))
    )
    (net (code "334") (name "unconnected-(JP52-Pad7)") (class "Default")
      (node (ref "JP52") (pin "7") (pinfunction "7_7") (pintype "passive"))
    )
    (net (code "335") (name "unconnected-(JP52-Pad8)") (class "Default")
      (node (ref "JP52") (pin "8") (pinfunction "8_8") (pintype "passive"))
    )
    (net (code "336") (name "unconnected-(JP52-Pad9)") (class "Default")
      (node (ref "JP52") (pin "9") (pinfunction "9_9") (pintype "passive"))
    )
    (net (code "337") (name "unconnected-(JP52-Pad10)") (class "Default")
      (node (ref "JP52") (pin "10") (pinfunction "10_10") (pintype "passive"))
    )
    (net (code "338") (name "unconnected-(JP52-Pad11)") (class "Default")
      (node (ref "JP52") (pin "11") (pinfunction "11_11") (pintype "passive"))
    )
    (net (code "339") (name "unconnected-(JP52-Pad12)") (class "Default")
      (node (ref "JP52") (pin "12") (pinfunction "12_12") (pintype "passive"))
    )
    (net (code "340") (name "unconnected-(JP52-Pad13)") (class "Default")
      (node (ref "JP52") (pin "13") (pinfunction "13_13") (pintype "passive"))
    )
    (net (code "341") (name "unconnected-(JP52-Pad14)") (class "Default")
      (node (ref "JP52") (pin "14") (pinfunction "14_14") (pintype "passive"))
    )
    (net (code "342") (name "unconnected-(JP53-Pad2)") (class "Default")
      (node (ref "JP53") (pin "2") (pinfunction "2_2") (pintype "passive"))
    )
    (net (code "343") (name "unconnected-(JP53-Pad3)") (class "Default")
      (node (ref "JP53") (pin "3") (pinfunction "3_3") (pintype "passive"))
    )
    (net (code "344") (name "unconnected-(JP53-Pad4)") (class "Default")
      (node (ref "JP53") (pin "4") (pinfunction "4_4") (pintype "passive"))
    )
    (net (code "345") (name "unconnected-(JP53-Pad5)") (class "Default")
      (node (ref "JP53") (pin "5") (pinfunction "5_5") (pintype "passive"))
    )
    (net (code "346") (name "unconnected-(JP53-Pad6)") (class "Default")
      (node (ref "JP53") (pin "6") (pinfunction "6_6") (pintype "passive"))
    )
    (net (code "347") (name "unconnected-(JP53-Pad7)") (class "Default")
      (node (ref "JP53") (pin "7") (pinfunction "7_7") (pintype "passive"))
    )
    (net (code "348") (name "unconnected-(JP53-Pad8)") (class "Default")
      (node (ref "JP53") (pin "8") (pinfunction "8_8") (pintype "passive"))
    )
    (net (code "349") (name "unconnected-(JP53-Pad9)") (class "Default")
      (node (ref "JP53") (pin "9") (pinfunction "9_9") (pintype "passive"))
    )
    (net (code "350") (name "unconnected-(JP53-Pad10)") (class "Default")
      (node (ref "JP53") (pin "10") (pinfunction "10_10") (pintype "passive"))
    )
    (net (code "351") (name "unconnected-(JP53-Pad11)") (class "Default")
      (node (ref "JP53") (pin "11") (pinfunction "11_11") (pintype "passive"))
    )
    (net (code "352") (name "unconnected-(JP53-Pad12)") (class "Default")
      (node (ref "JP53") (pin "12") (pinfunction "12_12") (pintype "passive"))
    )
    (net (code "353") (name "unconnected-(JP53-Pad13)") (class "Default")
      (node (ref "JP53") (pin "13") (pinfunction "13_13") (pintype "passive"))
    )
    (net (code "354") (name "unconnected-(JP53-Pad14)") (class "Default")
      (node (ref "JP53") (pin "14") (pinfunction "14_14") (pintype "passive"))
    )
    (net (code "355") (name "unconnected-(JP56-Pad2)") (class "Default")
      (node (ref "JP56") (pin "2") (pinfunction "2_2") (pintype "passive"))
    )
    (net (code "356") (name "unconnected-(JP56-Pad3)") (class "Default")
      (node (ref "JP56") (pin "3") (pinfunction "3_3") (pintype "passive"))
    )
    (net (code "357") (name "unconnected-(JP56-Pad4)") (class "Default")
      (node (ref "JP56") (pin "4") (pinfunction "4_4") (pintype "passive"))
    )
    (net (code "358") (name "unconnected-(JP56-Pad5)") (class "Default")
      (node (ref "JP56") (pin "5") (pinfunction "5_5") (pintype "passive"))
    )
    (net (code "359") (name "unconnected-(JP56-Pad6)") (class "Default")
      (node (ref "JP56") (pin "6") (pinfunction "6_6") (pintype "passive"))
    )
    (net (code "360") (name "unconnected-(JP56-Pad7)") (class "Default")
      (node (ref "JP56") (pin "7") (pinfunction "7_7") (pintype "passive"))
    )
    (net (code "361") (name "unconnected-(JP56-Pad8)") (class "Default")
      (node (ref "JP56") (pin "8") (pinfunction "8_8") (pintype "passive"))
    )
    (net (code "362") (name "unconnected-(JP56-Pad9)") (class "Default")
      (node (ref "JP56") (pin "9") (pinfunction "9_9") (pintype "passive"))
    )
    (net (code "363") (name "unconnected-(JP56-Pad10)") (class "Default")
      (node (ref "JP56") (pin "10") (pinfunction "10_10") (pintype "passive"))
    )
    (net (code "364") (name "unconnected-(JP56-Pad11)") (class "Default")
      (node (ref "JP56") (pin "11") (pinfunction "11_11") (pintype "passive"))
    )
    (net (code "365") (name "unconnected-(JP56-Pad12)") (class "Default")
      (node (ref "JP56") (pin "12") (pinfunction "12_12") (pintype "passive"))
    )
    (net (code "366") (name "unconnected-(JP56-Pad13)") (class "Default")
      (node (ref "JP56") (pin "13") (pinfunction "13_13") (pintype "passive"))
    )
    (net (code "367") (name "unconnected-(JP56-Pad14)") (class "Default")
      (node (ref "JP56") (pin "14") (pinfunction "14_14") (pintype "passive"))
    )
    (net (code "368") (name "unconnected-(JP57-Pad2)") (class "Default")
      (node (ref "JP57") (pin "2") (pinfunction "2_2") (pintype "passive"))
    )
    (net (code "369") (name "unconnected-(JP57-Pad3)") (class "Default")
      (node (ref "JP57") (pin "3") (pinfunction "3_3") (pintype "passive"))
    )
    (net (code "370") (name "unconnected-(JP57-Pad4)") (class "Default")
      (node (ref "JP57") (pin "4") (pinfunction "4_4") (pintype "passive"))
    )
    (net (code "371") (name "unconnected-(JP57-Pad5)") (class "Default")
      (node (ref "JP57") (pin "5") (pinfunction "5_5") (pintype "passive"))
    )
    (net (code "372") (name "unconnected-(JP57-Pad6)") (class "Default")
      (node (ref "JP57") (pin "6") (pinfunction "6_6") (pintype "passive"))
    )
    (net (code "373") (name "unconnected-(JP57-Pad7)") (class "Default")
      (node (ref "JP57") (pin "7") (pinfunction "7_7") (pintype "passive"))
    )
    (net (code "374") (name "unconnected-(JP57-Pad8)") (class "Default")
      (node (ref "JP57") (pin "8") (pinfunction "8_8") (pintype "passive"))
    )
    (net (code "375") (name "unconnected-(JP57-Pad9)") (class "Default")
      (node (ref "JP57") (pin "9") (pinfunction "9_9") (pintype "passive"))
    )
    (net (code "376") (name "unconnected-(JP57-Pad10)") (class "Default")
      (node (ref "JP57") (pin "10") (pinfunction "10_10") (pintype "passive"))
    )
    (net (code "377") (name "unconnected-(JP57-Pad11)") (class "Default")
      (node (ref "JP57") (pin "11") (pinfunction "11_11") (pintype "passive"))
    )
    (net (code "378") (name "unconnected-(JP57-Pad12)") (class "Default")
      (node (ref "JP57") (pin "12") (pinfunction "12_12") (pintype "passive"))
    )
    (net (code "379") (name "unconnected-(JP57-Pad13)") (class "Default")
      (node (ref "JP57") (pin "13") (pinfunction "13_13") (pintype "passive"))
    )
    (net (code "380") (name "unconnected-(JP57-Pad14)") (class "Default")
      (node (ref "JP57") (pin "14") (pinfunction "14_14") (pintype "passive"))
    )
    (net (code "381") (name "unconnected-(JP58-Pad2)") (class "Default")
      (node (ref "JP58") (pin "2") (pinfunction "2_2") (pintype "passive"))
    )
    (net (code "382") (name "unconnected-(JP58-Pad3)") (class "Default")
      (node (ref "JP58") (pin "3") (pinfunction "3_3") (pintype "passive"))
    )
    (net (code "383") (name "unconnected-(JP58-Pad4)") (class "Default")
      (node (ref "JP58") (pin "4") (pinfunction "4_4") (pintype "passive"))
    )
    (net (code "384") (name "unconnected-(JP58-Pad5)") (class "Default")
      (node (ref "JP58") (pin "5") (pinfunction "5_5") (pintype "passive"))
    )
    (net (code "385") (name "unconnected-(JP58-Pad6)") (class "Default")
      (node (ref "JP58") (pin "6") (pinfunction "6_6") (pintype "passive"))
    )
    (net (code "386") (name "unconnected-(JP58-Pad7)") (class "Default")
      (node (ref "JP58") (pin "7") (pinfunction "7_7") (pintype "passive"))
    )
    (net (code "387") (name "unconnected-(JP58-Pad8)") (class "Default")
      (node (ref "JP58") (pin "8") (pinfunction "8_8") (pintype "passive"))
    )
    (net (code "388") (name "unconnected-(JP58-Pad9)") (class "Default")
      (node (ref "JP58") (pin "9") (pinfunction "9_9") (pintype "passive"))
    )
    (net (code "389") (name "unconnected-(JP58-Pad10)") (class "Default")
      (node (ref "JP58") (pin "10") (pinfunction "10_10") (pintype "passive"))
    )
    (net (code "390") (name "unconnected-(JP58-Pad11)") (class "Default")
      (node (ref "JP58") (pin "11") (pinfunction "11_11") (pintype "passive"))
    )
    (net (code "391") (name "unconnected-(JP58-Pad12)") (class "Default")
      (node (ref "JP58") (pin "12") (pinfunction "12_12") (pintype "passive"))
    )
    (net (code "392") (name "unconnected-(JP58-Pad13)") (class "Default")
      (node (ref "JP58") (pin "13") (pinfunction "13_13") (pintype "passive"))
    )
    (net (code "393") (name "unconnected-(JP58-Pad14)") (class "Default")
      (node (ref "JP58") (pin "14") (pinfunction "14_14") (pintype "passive"))
    )
    (net (code "394") (name "unconnected-(JP59-Pad2)") (class "Default")
      (node (ref "JP59") (pin "2") (pinfunction "2_2") (pintype "passive"))
    )
    (net (code "395") (name "unconnected-(JP59-Pad3)") (class "Default")
      (node (ref "JP59") (pin "3") (pinfunction "3_3") (pintype "passive"))
    )
    (net (code "396") (name "unconnected-(JP59-Pad4)") (class "Default")
      (node (ref "JP59") (pin "4") (pinfunction "4_4") (pintype "passive"))
    )
    (net (code "397") (name "unconnected-(JP59-Pad5)") (class "Default")
      (node (ref "JP59") (pin "5") (pinfunction "5_5") (pintype "passive"))
    )
    (net (code "398") (name "unconnected-(JP59-Pad6)") (class "Default")
      (node (ref "JP59") (pin "6") (pinfunction "6_6") (pintype "passive"))
    )
    (net (code "399") (name "unconnected-(JP59-Pad7)") (class "Default")
      (node (ref "JP59") (pin "7") (pinfunction "7_7") (pintype "passive"))
    )
    (net (code "400") (name "unconnected-(JP59-Pad8)") (class "Default")
      (node (ref "JP59") (pin "8") (pinfunction "8_8") (pintype "passive"))
    )
    (net (code "401") (name "unconnected-(JP59-Pad9)") (class "Default")
      (node (ref "JP59") (pin "9") (pinfunction "9_9") (pintype "passive"))
    )
    (net (code "402") (name "unconnected-(JP59-Pad10)") (class "Default")
      (node (ref "JP59") (pin "10") (pinfunction "10_10") (pintype "passive"))
    )
    (net (code "403") (name "unconnected-(JP59-Pad11)") (class "Default")
      (node (ref "JP59") (pin "11") (pinfunction "11_11") (pintype "passive"))
    )
    (net (code "404") (name "unconnected-(JP59-Pad12)") (class "Default")
      (node (ref "JP59") (pin "12") (pinfunction "12_12") (pintype "passive"))
    )
    (net (code "405") (name "unconnected-(JP59-Pad13)") (class "Default")
      (node (ref "JP59") (pin "13") (pinfunction "13_13") (pintype "passive"))
    )
    (net (code "406") (name "unconnected-(JP59-Pad14)") (class "Default")
      (node (ref "JP59") (pin "14") (pinfunction "14_14") (pintype "passive"))
    )
    (net (code "407") (name "unconnected-(JP60-Pad2)") (class "Default")
      (node (ref "JP60") (pin "2") (pinfunction "2_2") (pintype "passive"))
    )
    (net (code "408") (name "unconnected-(JP60-Pad3)") (class "Default")
      (node (ref "JP60") (pin "3") (pinfunction "3_3") (pintype "passive"))
    )
    (net (code "409") (name "unconnected-(JP60-Pad4)") (class "Default")
      (node (ref "JP60") (pin "4") (pinfunction "4_4") (pintype "passive"))
    )
    (net (code "410") (name "unconnected-(JP60-Pad5)") (class "Default")
      (node (ref "JP60") (pin "5") (pinfunction "5_5") (pintype "passive"))
    )
    (net (code "411") (name "unconnected-(JP60-Pad6)") (class "Default")
      (node (ref "JP60") (pin "6") (pinfunction "6_6") (pintype "passive"))
    )
    (net (code "412") (name "unconnected-(JP60-Pad7)") (class "Default")
      (node (ref "JP60") (pin "7") (pinfunction "7_7") (pintype "passive"))
    )
    (net (code "413") (name "unconnected-(JP60-Pad8)") (class "Default")
      (node (ref "JP60") (pin "8") (pinfunction "8_8") (pintype "passive"))
    )
    (net (code "414") (name "unconnected-(JP60-Pad9)") (class "Default")
      (node (ref "JP60") (pin "9") (pinfunction "9_9") (pintype "passive"))
    )
    (net (code "415") (name "unconnected-(JP60-Pad10)") (class "Default")
      (node (ref "JP60") (pin "10") (pinfunction "10_10") (pintype "passive"))
    )
    (net (code "416") (name "unconnected-(JP60-Pad11)") (class "Default")
      (node (ref "JP60") (pin "11") (pinfunction "11_11") (pintype "passive"))
    )
    (net (code "417") (name "unconnected-(JP60-Pad12)") (class "Default")
      (node (ref "JP60") (pin "12") (pinfunction "12_12") (pintype "passive"))
    )
    (net (code "418") (name "unconnected-(JP60-Pad13)") (class "Default")
      (node (ref "JP60") (pin "13") (pinfunction "13_13") (pintype "passive"))
    )
    (net (code "419") (name "unconnected-(JP60-Pad14)") (class "Default")
      (node (ref "JP60") (pin "14") (pinfunction "14_14") (pintype "passive"))
    )
    (net (code "420") (name "unconnected-(JP61-Pad2)") (class "Default")
      (node (ref "JP61") (pin "2") (pinfunction "2_2") (pintype "passive"))
    )
    (net (code "421") (name "unconnected-(JP61-Pad3)") (class "Default")
      (node (ref "JP61") (pin "3") (pinfunction "3_3") (pintype "passive"))
    )
    (net (code "422") (name "unconnected-(JP61-Pad4)") (class "Default")
      (node (ref "JP61") (pin "4") (pinfunction "4_4") (pintype "passive"))
    )
    (net (code "423") (name "unconnected-(JP61-Pad5)") (class "Default")
      (node (ref "JP61") (pin "5") (pinfunction "5_5") (pintype "passive"))
    )
    (net (code "424") (name "unconnected-(JP61-Pad6)") (class "Default")
      (node (ref "JP61") (pin "6") (pinfunction "6_6") (pintype "passive"))
    )
    (net (code "425") (name "unconnected-(JP61-Pad7)") (class "Default")
      (node (ref "JP61") (pin "7") (pinfunction "7_7") (pintype "passive"))
    )
    (net (code "426") (name "unconnected-(JP61-Pad8)") (class "Default")
      (node (ref "JP61") (pin "8") (pinfunction "8_8") (pintype "passive"))
    )
    (net (code "427") (name "unconnected-(JP61-Pad9)") (class "Default")
      (node (ref "JP61") (pin "9") (pinfunction "9_9") (pintype "passive"))
    )
    (net (code "428") (name "unconnected-(JP61-Pad10)") (class "Default")
      (node (ref "JP61") (pin "10") (pinfunction "10_10") (pintype "passive"))
    )
    (net (code "429") (name "unconnected-(JP61-Pad11)") (class "Default")
      (node (ref "JP61") (pin "11") (pinfunction "11_11") (pintype "passive"))
    )
    (net (code "430") (name "unconnected-(JP61-Pad12)") (class "Default")
      (node (ref "JP61") (pin "12") (pinfunction "12_12") (pintype "passive"))
    )
    (net (code "431") (name "unconnected-(JP61-Pad13)") (class "Default")
      (node (ref "JP61") (pin "13") (pinfunction "13_13") (pintype "passive"))
    )
    (net (code "432") (name "unconnected-(JP61-Pad14)") (class "Default")
      (node (ref "JP61") (pin "14") (pinfunction "14_14") (pintype "passive"))
    )
    (net (code "433") (name "unconnected-(JP62-Pad2)") (class "Default")
      (node (ref "JP62") (pin "2") (pinfunction "2_2") (pintype "passive"))
    )
    (net (code "434") (name "unconnected-(JP62-Pad3)") (class "Default")
      (node (ref "JP62") (pin "3") (pinfunction "3_3") (pintype "passive"))
    )
    (net (code "435") (name "unconnected-(JP62-Pad4)") (class "Default")
      (node (ref "JP62") (pin "4") (pinfunction "4_4") (pintype "passive"))
    )
    (net (code "436") (name "unconnected-(JP62-Pad5)") (class "Default")
      (node (ref "JP62") (pin "5") (pinfunction "5_5") (pintype "passive"))
    )
    (net (code "437") (name "unconnected-(JP62-Pad6)") (class "Default")
      (node (ref "JP62") (pin "6") (pinfunction "6_6") (pintype "passive"))
    )
    (net (code "438") (name "unconnected-(JP62-Pad7)") (class "Default")
      (node (ref "JP62") (pin "7") (pinfunction "7_7") (pintype "passive"))
    )
    (net (code "439") (name "unconnected-(JP62-Pad8)") (class "Default")
      (node (ref "JP62") (pin "8") (pinfunction "8_8") (pintype "passive"))
    )
    (net (code "440") (name "unconnected-(JP62-Pad9)") (class "Default")
      (node (ref "JP62") (pin "9") (pinfunction "9_9") (pintype "passive"))
    )
    (net (code "441") (name "unconnected-(JP62-Pad10)") (class "Default")
      (node (ref "JP62") (pin "10") (pinfunction "10_10") (pintype "passive"))
    )
    (net (code "442") (name "unconnected-(JP62-Pad11)") (class "Default")
      (node (ref "JP62") (pin "11") (pinfunction "11_11") (pintype "passive"))
    )
    (net (code "443") (name "unconnected-(JP62-Pad12)") (class "Default")
      (node (ref "JP62") (pin "12") (pinfunction "12_12") (pintype "passive"))
    )
    (net (code "444") (name "unconnected-(JP62-Pad13)") (class "Default")
      (node (ref "JP62") (pin "13") (pinfunction "13_13") (pintype "passive"))
    )
    (net (code "445") (name "unconnected-(JP62-Pad14)") (class "Default")
      (node (ref "JP62") (pin "14") (pinfunction "14_14") (pintype "passive"))
    )
    (net (code "446") (name "unconnected-(JP63-Pad2)") (class "Default")
      (node (ref "JP63") (pin "2") (pinfunction "2_2") (pintype "passive"))
    )
    (net (code "447") (name "unconnected-(JP63-Pad3)") (class "Default")
      (node (ref "JP63") (pin "3") (pinfunction "3_3") (pintype "passive"))
    )
    (net (code "448") (name "unconnected-(JP63-Pad4)") (class "Default")
      (node (ref "JP63") (pin "4") (pinfunction "4_4") (pintype "passive"))
    )
    (net (code "449") (name "unconnected-(JP63-Pad5)") (class "Default")
      (node (ref "JP63") (pin "5") (pinfunction "5_5") (pintype "passive"))
    )
    (net (code "450") (name "unconnected-(JP63-Pad6)") (class "Default")
      (node (ref "JP63") (pin "6") (pinfunction "6_6") (pintype "passive"))
    )
    (net (code "451") (name "unconnected-(JP63-Pad7)") (class "Default")
      (node (ref "JP63") (pin "7") (pinfunction "7_7") (pintype "passive"))
    )
    (net (code "452") (name "unconnected-(JP63-Pad8)") (class "Default")
      (node (ref "JP63") (pin "8") (pinfunction "8_8") (pintype "passive"))
    )
    (net (code "453") (name "unconnected-(JP63-Pad9)") (class "Default")
      (node (ref "JP63") (pin "9") (pinfunction "9_9") (pintype "passive"))
    )
    (net (code "454") (name "unconnected-(JP63-Pad10)") (class "Default")
      (node (ref "JP63") (pin "10") (pinfunction "10_10") (pintype "passive"))
    )
    (net (code "455") (name "unconnected-(JP63-Pad11)") (class "Default")
      (node (ref "JP63") (pin "11") (pinfunction "11_11") (pintype "passive"))
    )
    (net (code "456") (name "unconnected-(JP63-Pad12)") (class "Default")
      (node (ref "JP63") (pin "12") (pinfunction "12_12") (pintype "passive"))
    )
    (net (code "457") (name "unconnected-(JP63-Pad13)") (class "Default")
      (node (ref "JP63") (pin "13") (pinfunction "13_13") (pintype "passive"))
    )
    (net (code "458") (name "unconnected-(JP63-Pad14)") (class "Default")
      (node (ref "JP63") (pin "14") (pinfunction "14_14") (pintype "passive"))
    )
    (net (code "459") (name "unconnected-(JP64-Pad2)") (class "Default")
      (node (ref "JP64") (pin "2") (pinfunction "2_2") (pintype "passive"))
    )
    (net (code "460") (name "unconnected-(JP64-Pad3)") (class "Default")
      (node (ref "JP64") (pin "3") (pinfunction "3_3") (pintype "passive"))
    )
    (net (code "461") (name "unconnected-(JP64-Pad4)") (class "Default")
      (node (ref "JP64") (pin "4") (pinfunction "4_4") (pintype "passive"))
    )
    (net (code "462") (name "unconnected-(JP64-Pad5)") (class "Default")
      (node (ref "JP64") (pin "5") (pinfunction "5_5") (pintype "passive"))
    )
    (net (code "463") (name "unconnected-(JP64-Pad6)") (class "Default")
      (node (ref "JP64") (pin "6") (pinfunction "6_6") (pintype "passive"))
    )
    (net (code "464") (name "unconnected-(JP64-Pad7)") (class "Default")
      (node (ref "JP64") (pin "7") (pinfunction "7_7") (pintype "passive"))
    )
    (net (code "465") (name "unconnected-(JP64-Pad8)") (class "Default")
      (node (ref "JP64") (pin "8") (pinfunction "8_8") (pintype "passive"))
    )
    (net (code "466") (name "unconnected-(JP64-Pad9)") (class "Default")
      (node (ref "JP64") (pin "9") (pinfunction "9_9") (pintype "passive"))
    )
    (net (code "467") (name "unconnected-(JP64-Pad10)") (class "Default")
      (node (ref "JP64") (pin "10") (pinfunction "10_10") (pintype "passive"))
    )
    (net (code "468") (name "unconnected-(JP64-Pad11)") (class "Default")
      (node (ref "JP64") (pin "11") (pinfunction "11_11") (pintype "passive"))
    )
    (net (code "469") (name "unconnected-(JP64-Pad12)") (class "Default")
      (node (ref "JP64") (pin "12") (pinfunction "12_12") (pintype "passive"))
    )
    (net (code "470") (name "unconnected-(JP64-Pad13)") (class "Default")
      (node (ref "JP64") (pin "13") (pinfunction "13_13") (pintype "passive"))
    )
    (net (code "471") (name "unconnected-(JP64-Pad14)") (class "Default")
      (node (ref "JP64") (pin "14") (pinfunction "14_14") (pintype "passive"))
    )
    (net (code "472") (name "unconnected-(JP65-Pad2)") (class "Default")
      (node (ref "JP65") (pin "2") (pinfunction "2_2") (pintype "passive"))
    )
    (net (code "473") (name "unconnected-(JP65-Pad3)") (class "Default")
      (node (ref "JP65") (pin "3") (pinfunction "3_3") (pintype "passive"))
    )
    (net (code "474") (name "unconnected-(JP65-Pad4)") (class "Default")
      (node (ref "JP65") (pin "4") (pinfunction "4_4") (pintype "passive"))
    )
    (net (code "475") (name "unconnected-(JP65-Pad5)") (class "Default")
      (node (ref "JP65") (pin "5") (pinfunction "5_5") (pintype "passive"))
    )
    (net (code "476") (name "unconnected-(JP65-Pad6)") (class "Default")
      (node (ref "JP65") (pin "6") (pinfunction "6_6") (pintype "passive"))
    )
    (net (code "477") (name "unconnected-(JP65-Pad7)") (class "Default")
      (node (ref "JP65") (pin "7") (pinfunction "7_7") (pintype "passive"))
    )
    (net (code "478") (name "unconnected-(JP65-Pad8)") (class "Default")
      (node (ref "JP65") (pin "8") (pinfunction "8_8") (pintype "passive"))
    )
    (net (code "479") (name "unconnected-(JP65-Pad9)") (class "Default")
      (node (ref "JP65") (pin "9") (pinfunction "9_9") (pintype "passive"))
    )
    (net (code "480") (name "unconnected-(JP65-Pad10)") (class "Default")
      (node (ref "JP65") (pin "10") (pinfunction "10_10") (pintype "passive"))
    )
    (net (code "481") (name "unconnected-(JP65-Pad11)") (class "Default")
      (node (ref "JP65") (pin "11") (pinfunction "11_11") (pintype "passive"))
    )
    (net (code "482") (name "unconnected-(JP65-Pad12)") (class "Default")
      (node (ref "JP65") (pin "12") (pinfunction "12_12") (pintype "passive"))
    )
    (net (code "483") (name "unconnected-(JP65-Pad13)") (class "Default")
      (node (ref "JP65") (pin "13") (pinfunction "13_13") (pintype "passive"))
    )
    (net (code "484") (name "unconnected-(JP65-Pad14)") (class "Default")
      (node (ref "JP65") (pin "14") (pinfunction "14_14") (pintype "passive"))
    )
    (net (code "485") (name "unconnected-(JP66-Pad2)") (class "Default")
      (node (ref "JP66") (pin "2") (pinfunction "2_2") (pintype "passive"))
    )
    (net (code "486") (name "unconnected-(JP66-Pad3)") (class "Default")
      (node (ref "JP66") (pin "3") (pinfunction "3_3") (pintype "passive"))
    )
    (net (code "487") (name "unconnected-(JP66-Pad4)") (class "Default")
      (node (ref "JP66") (pin "4") (pinfunction "4_4") (pintype "passive"))
    )
    (net (code "488") (name "unconnected-(JP66-Pad5)") (class "Default")
      (node (ref "JP66") (pin "5") (pinfunction "5_5") (pintype "passive"))
    )
    (net (code "489") (name "unconnected-(JP66-Pad6)") (class "Default")
      (node (ref "JP66") (pin "6") (pinfunction "6_6") (pintype "passive"))
    )
    (net (code "490") (name "unconnected-(JP66-Pad7)") (class "Default")
      (node (ref "JP66") (pin "7") (pinfunction "7_7") (pintype "passive"))
    )
    (net (code "491") (name "unconnected-(JP66-Pad8)") (class "Default")
      (node (ref "JP66") (pin "8") (pinfunction "8_8") (pintype "passive"))
    )
    (net (code "492") (name "unconnected-(JP66-Pad9)") (class "Default")
      (node (ref "JP66") (pin "9") (pinfunction "9_9") (pintype "passive"))
    )
    (net (code "493") (name "unconnected-(JP66-Pad10)") (class "Default")
      (node (ref "JP66") (pin "10") (pinfunction "10_10") (pintype "passive"))
    )
    (net (code "494") (name "unconnected-(JP66-Pad11)") (class "Default")
      (node (ref "JP66") (pin "11") (pinfunction "11_11") (pintype "passive"))
    )
    (net (code "495") (name "unconnected-(JP66-Pad12)") (class "Default")
      (node (ref "JP66") (pin "12") (pinfunction "12_12") (pintype "passive"))
    )
    (net (code "496") (name "unconnected-(JP66-Pad13)") (class "Default")
      (node (ref "JP66") (pin "13") (pinfunction "13_13") (pintype "passive"))
    )
    (net (code "497") (name "unconnected-(JP66-Pad14)") (class "Default")
      (node (ref "JP66") (pin "14") (pinfunction "14_14") (pintype "passive"))
    )
    (net (code "498") (name "unconnected-(JP67-Pad2)") (class "Default")
      (node (ref "JP67") (pin "2") (pinfunction "2_2") (pintype "passive"))
    )
    (net (code "499") (name "unconnected-(JP67-Pad3)") (class "Default")
      (node (ref "JP67") (pin "3") (pinfunction "3_3") (pintype "passive"))
    )
    (net (code "500") (name "unconnected-(JP67-Pad4)") (class "Default")
      (node (ref "JP67") (pin "4") (pinfunction "4_4") (pintype "passive"))
    )
    (net (code "501") (name "unconnected-(JP67-Pad5)") (class "Default")
      (node (ref "JP67") (pin "5") (pinfunction "5_5") (pintype "passive"))
    )
    (net (code "502") (name "unconnected-(JP67-Pad6)") (class "Default")
      (node (ref "JP67") (pin "6") (pinfunction "6_6") (pintype "passive"))
    )
    (net (code "503") (name "unconnected-(JP67-Pad7)") (class "Default")
      (node (ref "JP67") (pin "7") (pinfunction "7_7") (pintype "passive"))
    )
    (net (code "504") (name "unconnected-(JP67-Pad8)") (class "Default")
      (node (ref "JP67") (pin "8") (pinfunction "8_8") (pintype "passive"))
    )
    (net (code "505") (name "unconnected-(JP67-Pad9)") (class "Default")
      (node (ref "JP67") (pin "9") (pinfunction "9_9") (pintype "passive"))
    )
    (net (code "506") (name "unconnected-(JP67-Pad10)") (class "Default")
      (node (ref "JP67") (pin "10") (pinfunction "10_10") (pintype "passive"))
    )
    (net (code "507") (name "unconnected-(JP67-Pad11)") (class "Default")
      (node (ref "JP67") (pin "11") (pinfunction "11_11") (pintype "passive"))
    )
    (net (code "508") (name "unconnected-(JP67-Pad12)") (class "Default")
      (node (ref "JP67") (pin "12") (pinfunction "12_12") (pintype "passive"))
    )
    (net (code "509") (name "unconnected-(JP67-Pad13)") (class "Default")
      (node (ref "JP67") (pin "13") (pinfunction "13_13") (pintype "passive"))
    )
    (net (code "510") (name "unconnected-(JP67-Pad14)") (class "Default")
      (node (ref "JP67") (pin "14") (pinfunction "14_14") (pintype "passive"))
    )
    (net (code "511") (name "unconnected-(JP68-Pad2)") (class "Default")
      (node (ref "JP68") (pin "2") (pinfunction "2_2") (pintype "passive"))
    )
    (net (code "512") (name "unconnected-(JP68-Pad3)") (class "Default")
      (node (ref "JP68") (pin "3") (pinfunction "3_3") (pintype "passive"))
    )
    (net (code "513") (name "unconnected-(JP68-Pad4)") (class "Default")
      (node (ref "JP68") (pin "4") (pinfunction "4_4") (pintype "passive"))
    )
    (net (code "514") (name "unconnected-(JP68-Pad5)") (class "Default")
      (node (ref "JP68") (pin "5") (pinfunction "5_5") (pintype "passive"))
    )
    (net (code "515") (name "unconnected-(JP68-Pad6)") (class "Default")
      (node (ref "JP68") (pin "6") (pinfunction "6_6") (pintype "passive"))
    )
    (net (code "516") (name "unconnected-(JP68-Pad7)") (class "Default")
      (node (ref "JP68") (pin "7") (pinfunction "7_7") (pintype "passive"))
    )
    (net (code "517") (name "unconnected-(JP68-Pad8)") (class "Default")
      (node (ref "JP68") (pin "8") (pinfunction "8_8") (pintype "passive"))
    )
    (net (code "518") (name "unconnected-(JP68-Pad9)") (class "Default")
      (node (ref "JP68") (pin "9") (pinfunction "9_9") (pintype "passive"))
    )
    (net (code "519") (name "unconnected-(JP68-Pad10)") (class "Default")
      (node (ref "JP68") (pin "10") (pinfunction "10_10") (pintype "passive"))
    )
    (net (code "520") (name "unconnected-(JP68-Pad11)") (class "Default")
      (node (ref "JP68") (pin "11") (pinfunction "11_11") (pintype "passive"))
    )
    (net (code "521") (name "unconnected-(JP68-Pad12)") (class "Default")
      (node (ref "JP68") (pin "12") (pinfunction "12_12") (pintype "passive"))
    )
    (net (code "522") (name "unconnected-(JP68-Pad13)") (class "Default")
      (node (ref "JP68") (pin "13") (pinfunction "13_13") (pintype "passive"))
    )
    (net (code "523") (name "unconnected-(JP68-Pad14)") (class "Default")
      (node (ref "JP68") (pin "14") (pinfunction "14_14") (pintype "passive"))
    )
    (net (code "524") (name "unconnected-(JP69-Pad2)") (class "Default")
      (node (ref "JP69") (pin "2") (pinfunction "2_2") (pintype "passive"))
    )
    (net (code "525") (name "unconnected-(JP69-Pad3)") (class "Default")
      (node (ref "JP69") (pin "3") (pinfunction "3_3") (pintype "passive"))
    )
    (net (code "526") (name "unconnected-(JP69-Pad4)") (class "Default")
      (node (ref "JP69") (pin "4") (pinfunction "4_4") (pintype "passive"))
    )
    (net (code "527") (name "unconnected-(JP69-Pad5)") (class "Default")
      (node (ref "JP69") (pin "5") (pinfunction "5_5") (pintype "passive"))
    )
    (net (code "528") (name "unconnected-(JP69-Pad6)") (class "Default")
      (node (ref "JP69") (pin "6") (pinfunction "6_6") (pintype "passive"))
    )
    (net (code "529") (name "unconnected-(JP69-Pad7)") (class "Default")
      (node (ref "JP69") (pin "7") (pinfunction "7_7") (pintype "passive"))
    )
    (net (code "530") (name "unconnected-(JP69-Pad8)") (class "Default")
      (node (ref "JP69") (pin "8") (pinfunction "8_8") (pintype "passive"))
    )
    (net (code "531") (name "unconnected-(JP69-Pad9)") (class "Default")
      (node (ref "JP69") (pin "9") (pinfunction "9_9") (pintype "passive"))
    )
    (net (code "532") (name "unconnected-(JP69-Pad10)") (class "Default")
      (node (ref "JP69") (pin "10") (pinfunction "10_10") (pintype "passive"))
    )
    (net (code "533") (name "unconnected-(JP69-Pad11)") (class "Default")
      (node (ref "JP69") (pin "11") (pinfunction "11_11") (pintype "passive"))
    )
    (net (code "534") (name "unconnected-(JP69-Pad12)") (class "Default")
      (node (ref "JP69") (pin "12") (pinfunction "12_12") (pintype "passive"))
    )
    (net (code "535") (name "unconnected-(JP69-Pad13)") (class "Default")
      (node (ref "JP69") (pin "13") (pinfunction "13_13") (pintype "passive"))
    )
    (net (code "536") (name "unconnected-(JP69-Pad14)") (class "Default")
      (node (ref "JP69") (pin "14") (pinfunction "14_14") (pintype "passive"))
    )
    (net (code "537") (name "unconnected-(JP70-Pad2)") (class "Default")
      (node (ref "JP70") (pin "2") (pinfunction "2_2") (pintype "passive"))
    )
    (net (code "538") (name "unconnected-(JP70-Pad3)") (class "Default")
      (node (ref "JP70") (pin "3") (pinfunction "3_3") (pintype "passive"))
    )
    (net (code "539") (name "unconnected-(JP70-Pad4)") (class "Default")
      (node (ref "JP70") (pin "4") (pinfunction "4_4") (pintype "passive"))
    )
    (net (code "540") (name "unconnected-(JP70-Pad5)") (class "Default")
      (node (ref "JP70") (pin "5") (pinfunction "5_5") (pintype "passive"))
    )
    (net (code "541") (name "unconnected-(JP70-Pad6)") (class "Default")
      (node (ref "JP70") (pin "6") (pinfunction "6_6") (pintype "passive"))
    )
    (net (code "542") (name "unconnected-(JP70-Pad7)") (class "Default")
      (node (ref "JP70") (pin "7") (pinfunction "7_7") (pintype "passive"))
    )
    (net (code "543") (name "unconnected-(JP70-Pad8)") (class "Default")
      (node (ref "JP70") (pin "8") (pinfunction "8_8") (pintype "passive"))
    )
    (net (code "544") (name "unconnected-(JP70-Pad9)") (class "Default")
      (node (ref "JP70") (pin "9") (pinfunction "9_9") (pintype "passive"))
    )
    (net (code "545") (name "unconnected-(JP70-Pad10)") (class "Default")
      (node (ref "JP70") (pin "10") (pinfunction "10_10") (pintype "passive"))
    )
    (net (code "546") (name "unconnected-(JP70-Pad11)") (class "Default")
      (node (ref "JP70") (pin "11") (pinfunction "11_11") (pintype "passive"))
    )
    (net (code "547") (name "unconnected-(JP70-Pad12)") (class "Default")
      (node (ref "JP70") (pin "12") (pinfunction "12_12") (pintype "passive"))
    )
    (net (code "548") (name "unconnected-(JP70-Pad13)") (class "Default")
      (node (ref "JP70") (pin "13") (pinfunction "13_13") (pintype "passive"))
    )
    (net (code "549") (name "unconnected-(JP70-Pad14)") (class "Default")
      (node (ref "JP70") (pin "14") (pinfunction "14_14") (pintype "passive"))
    )
    (net (code "550") (name "unconnected-(JP70-Pad15)") (class "Default")
      (node (ref "JP70") (pin "15") (pinfunction "15_15") (pintype "passive"))
    )
    (net (code "551") (name "unconnected-(JP70-Pad16)") (class "Default")
      (node (ref "JP70") (pin "16") (pinfunction "16_16") (pintype "passive"))
    )
  )
)
